# working_ACB_Jr_4.net
KiCad netlist of a schematic drawn in EAGLE
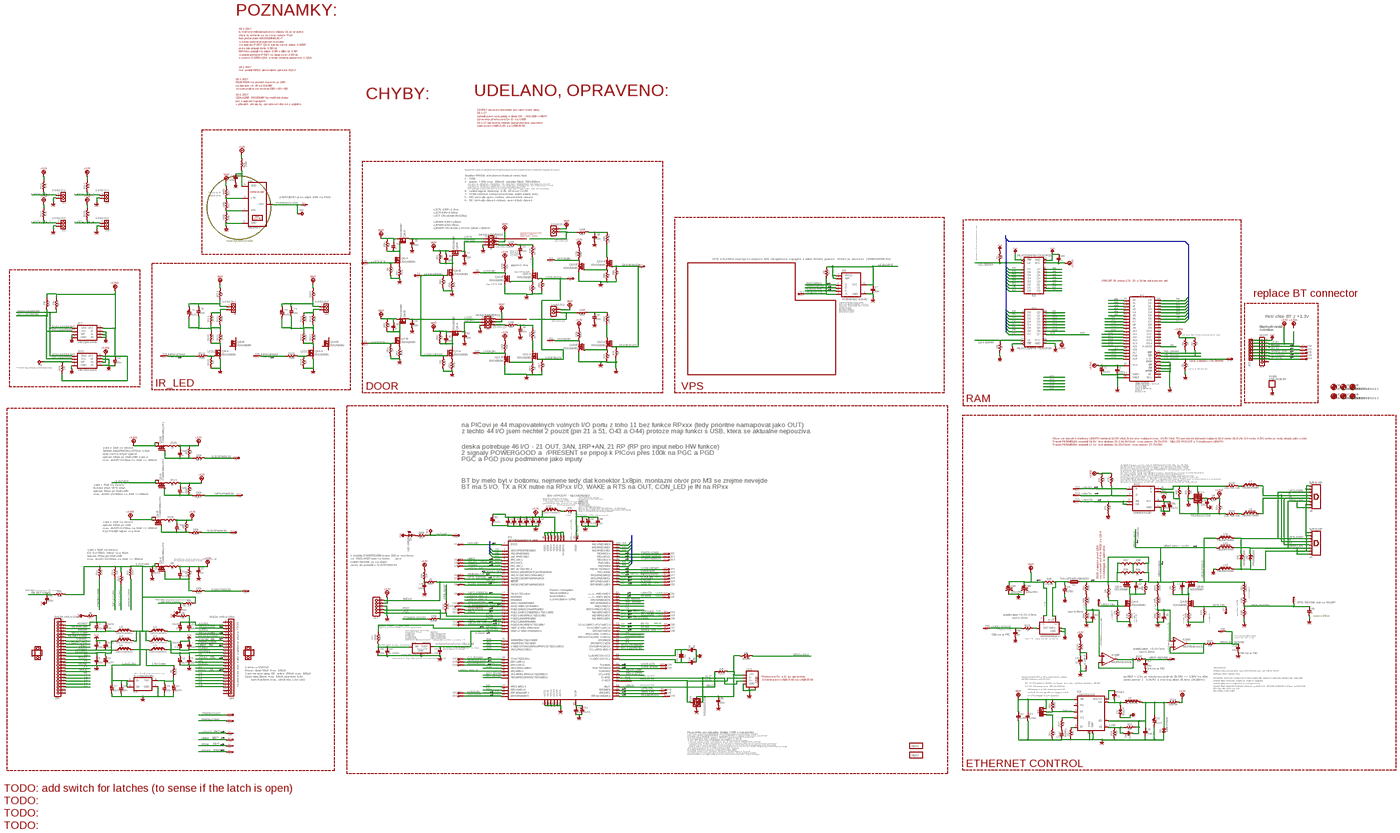
[diagram p0: schematic, sheet 1, overview]
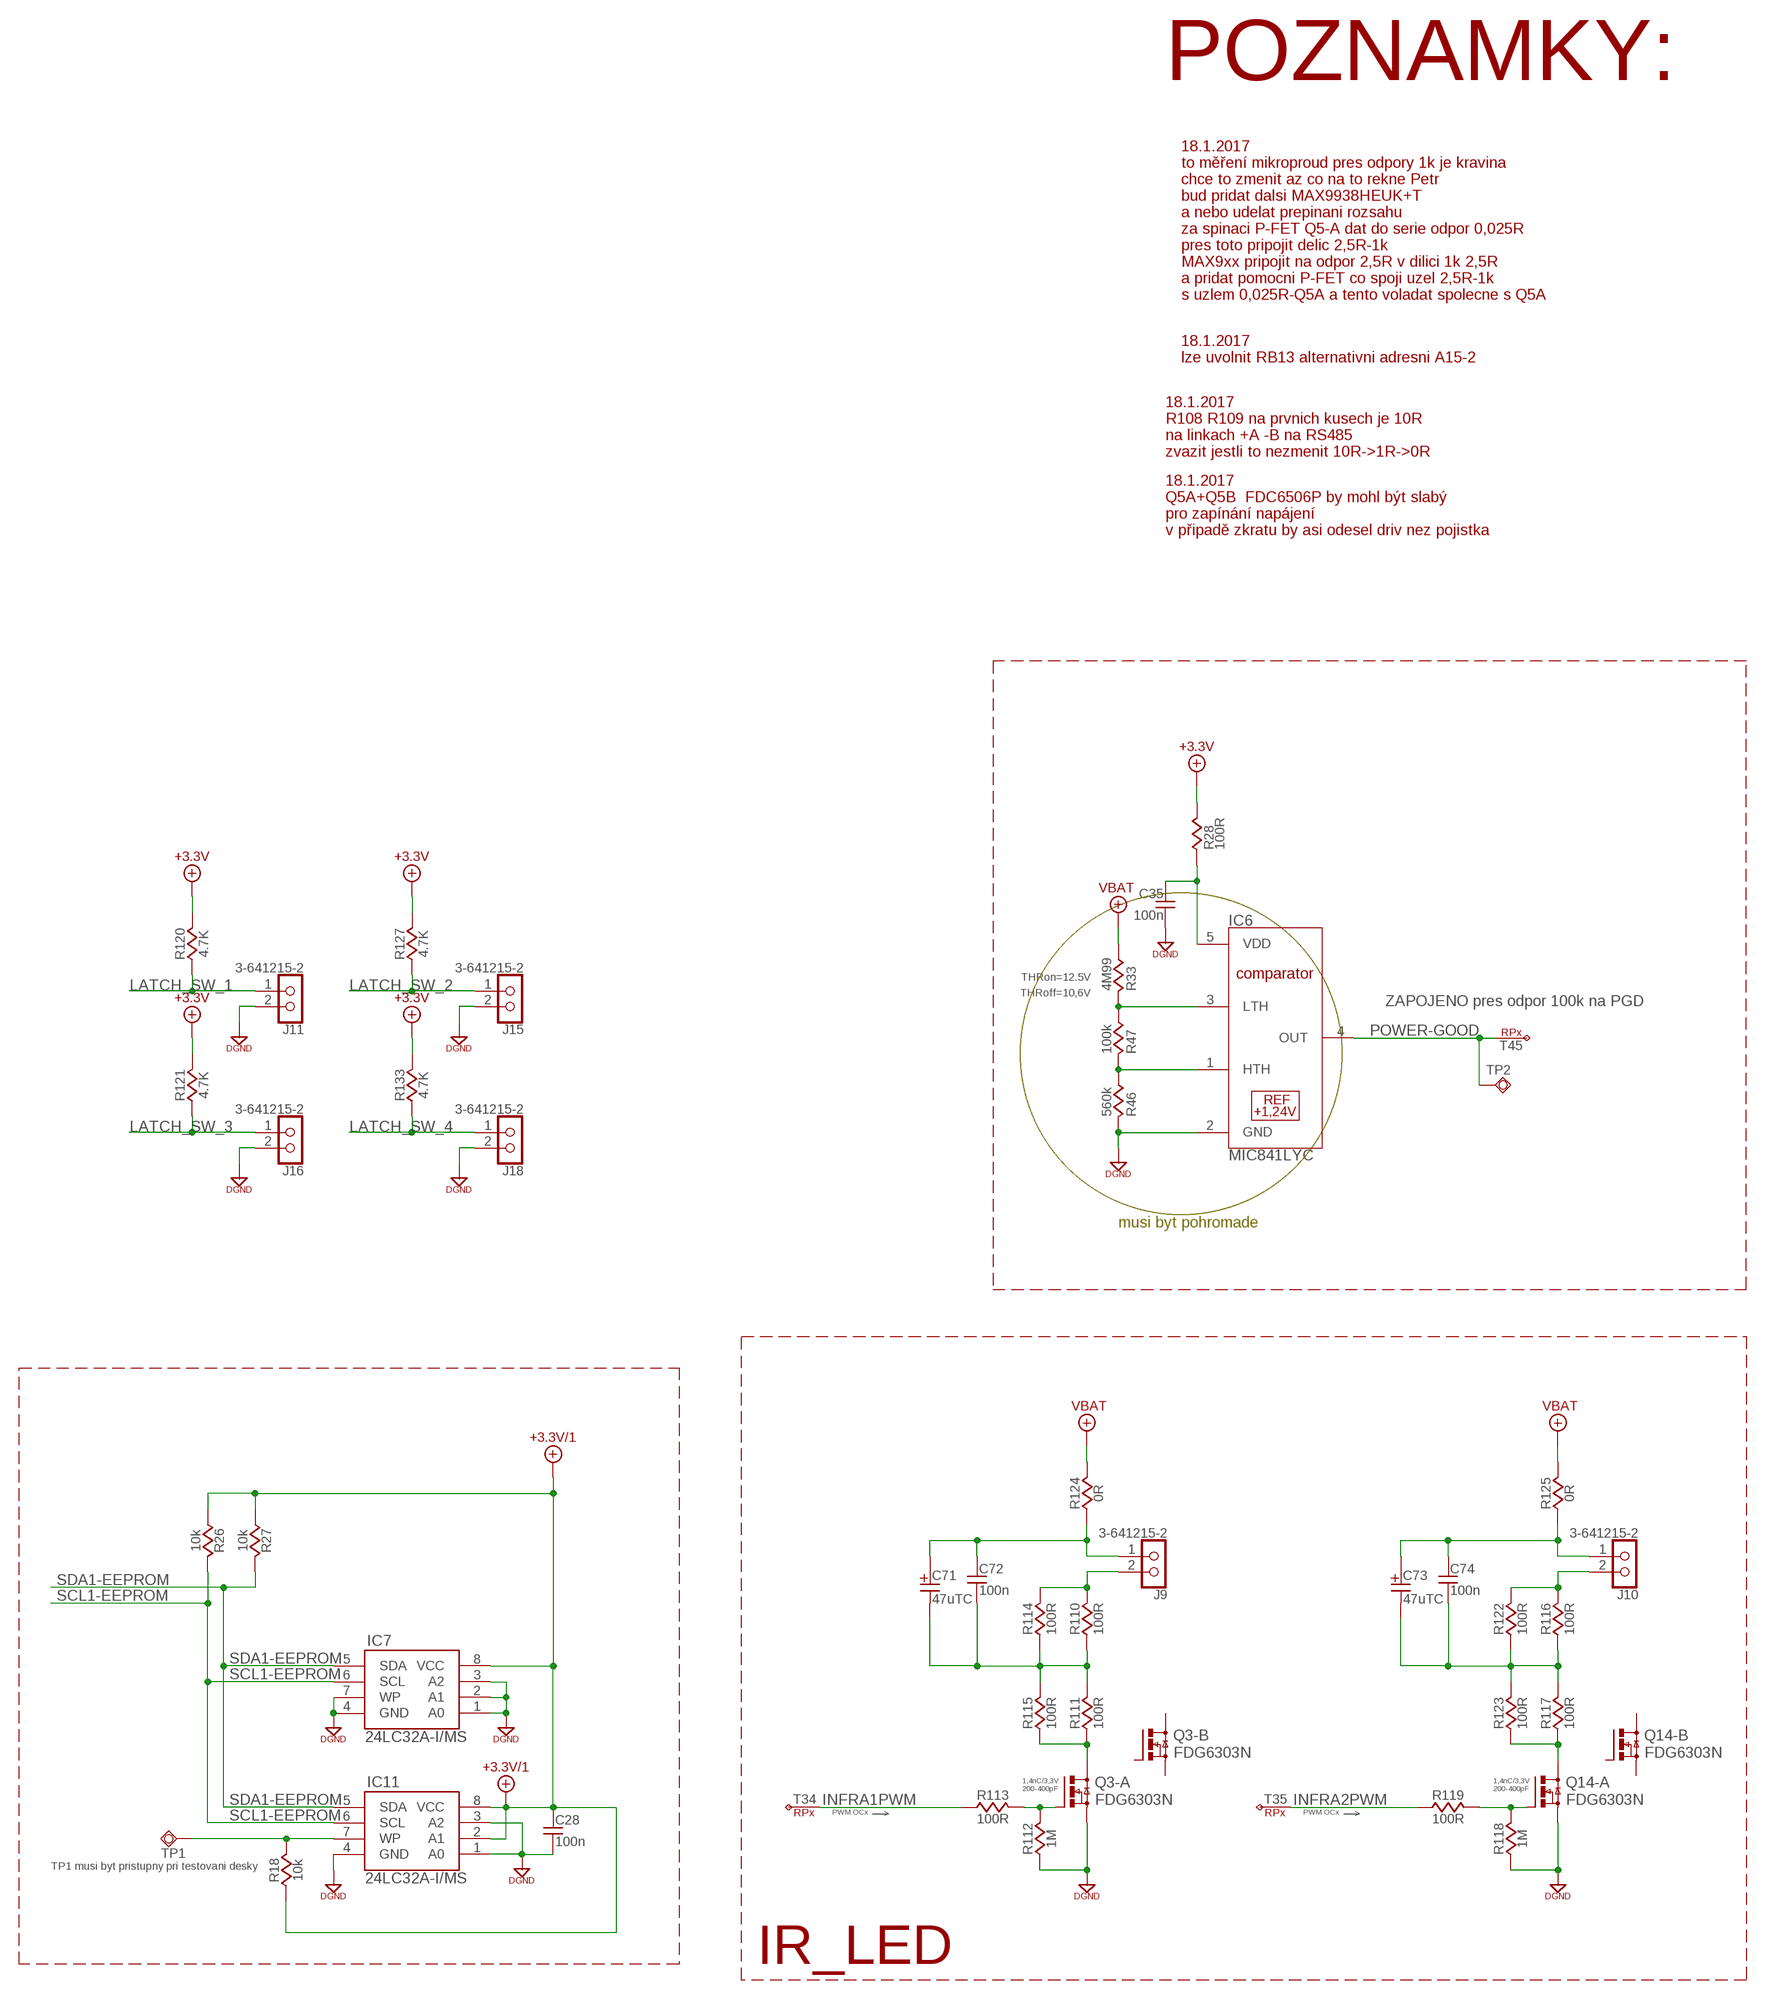
[diagram p1: schematic, sheet 1, part 1 of 5]
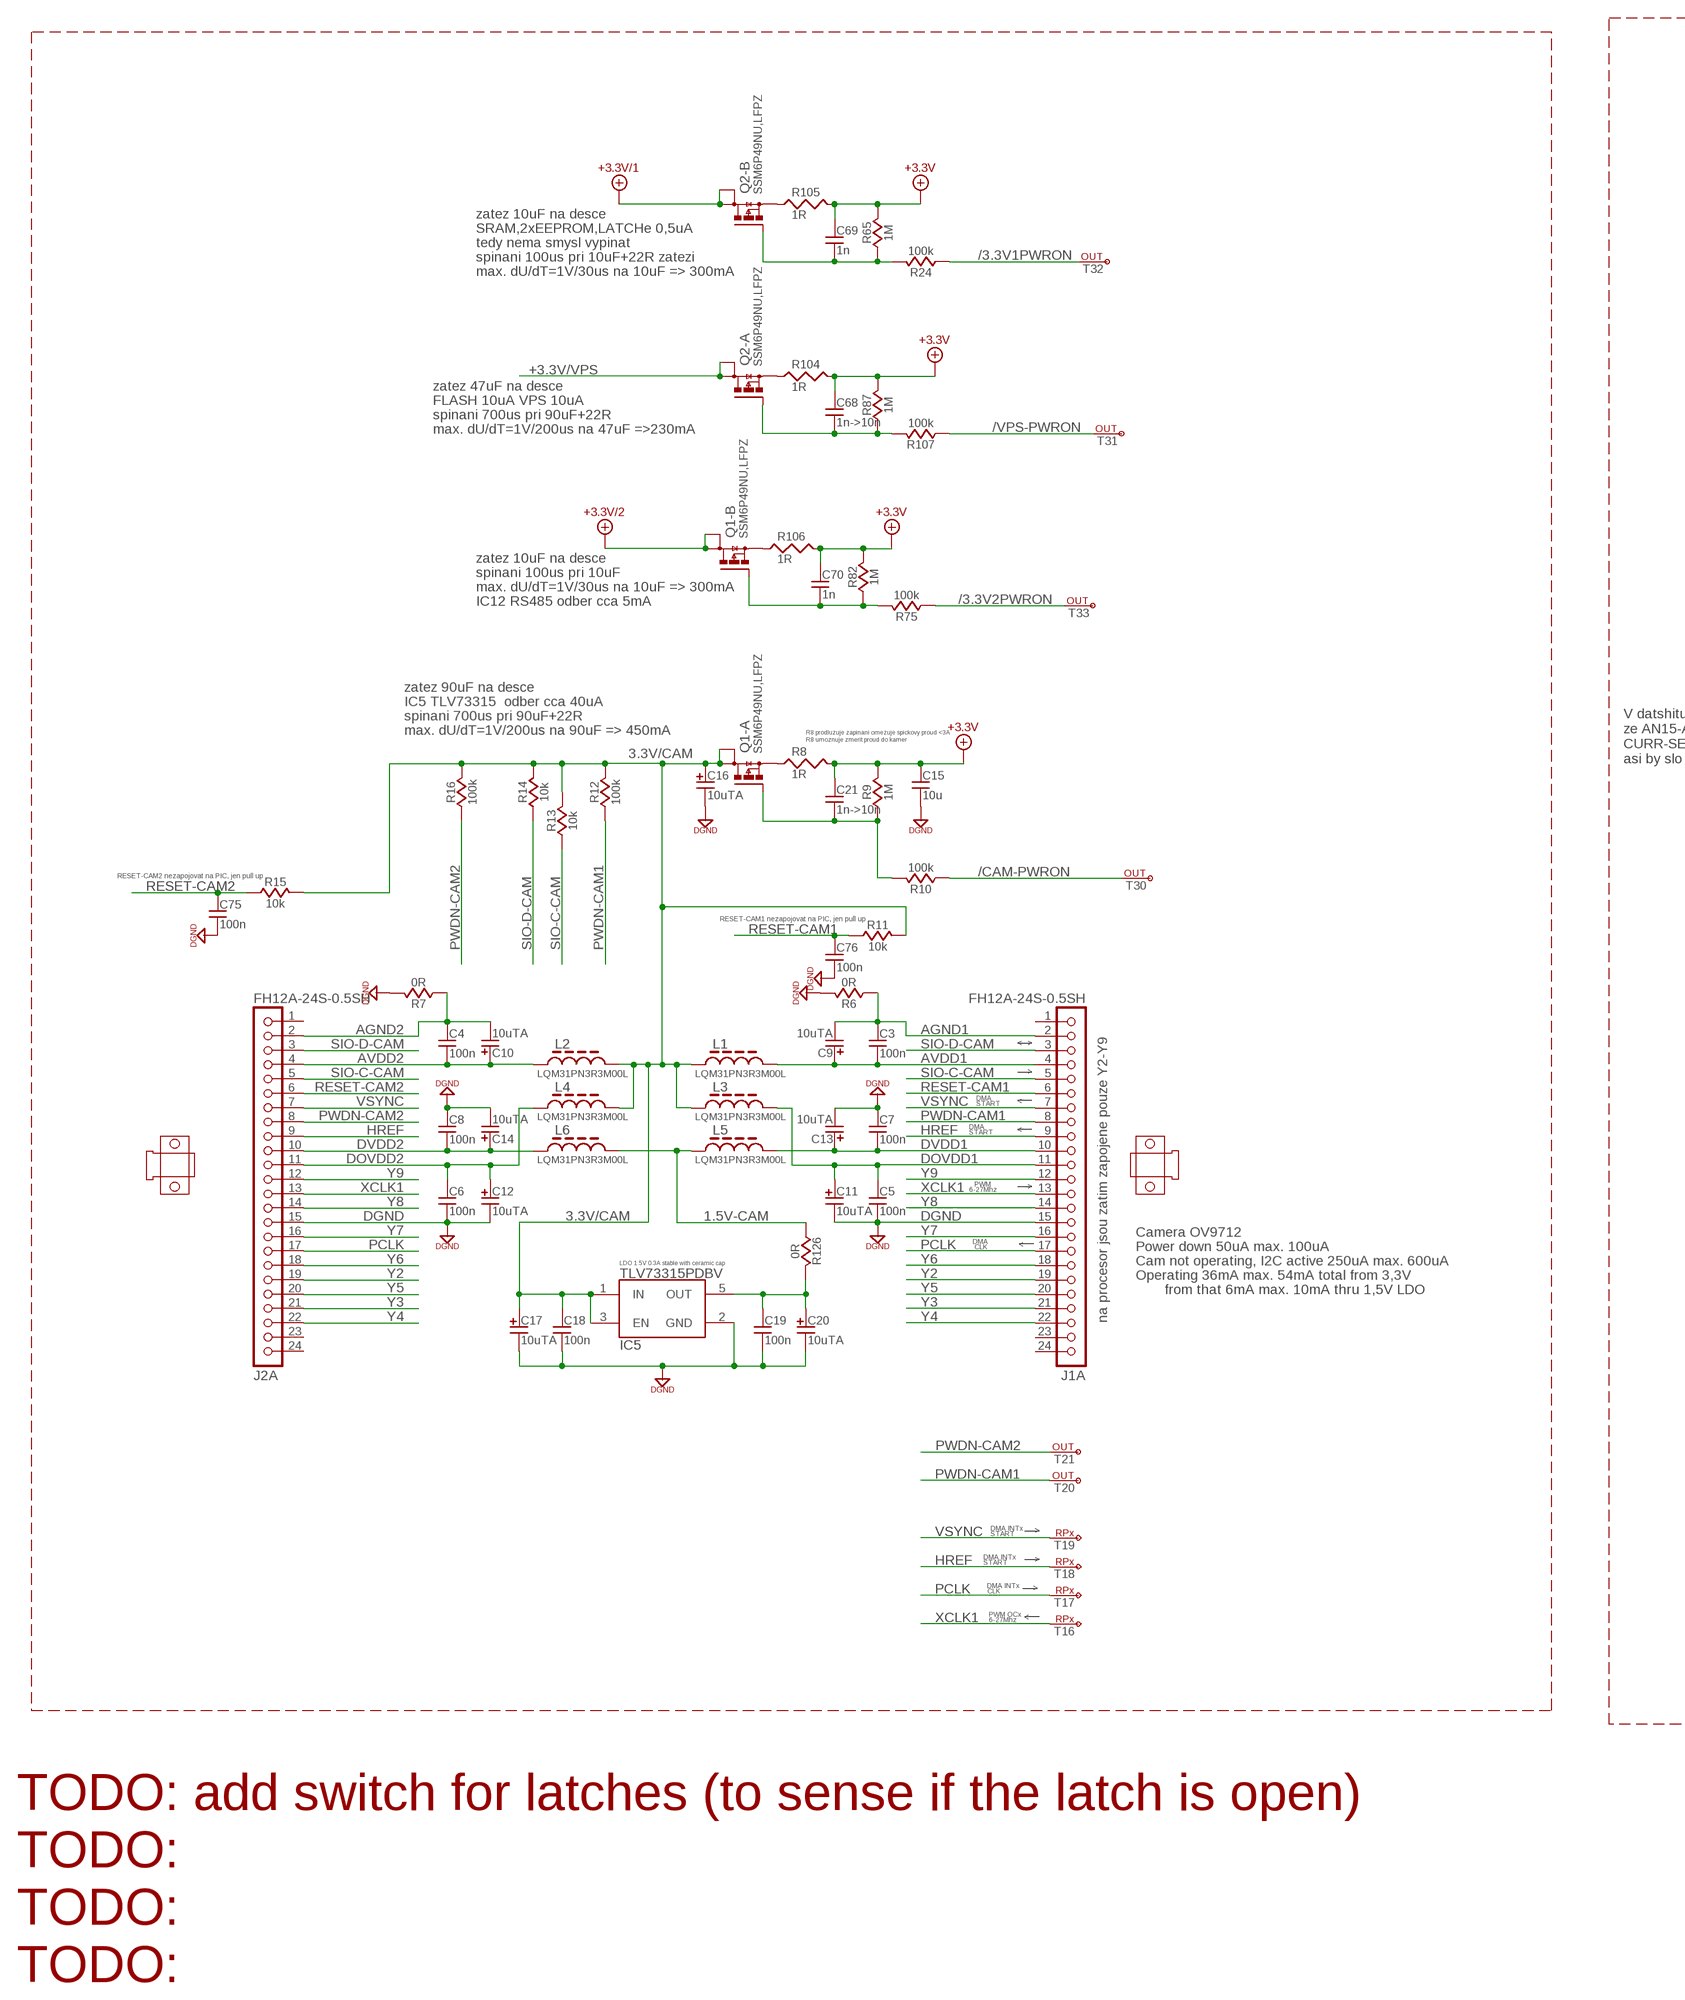
[diagram p2: schematic, sheet 1, part 2 of 5]
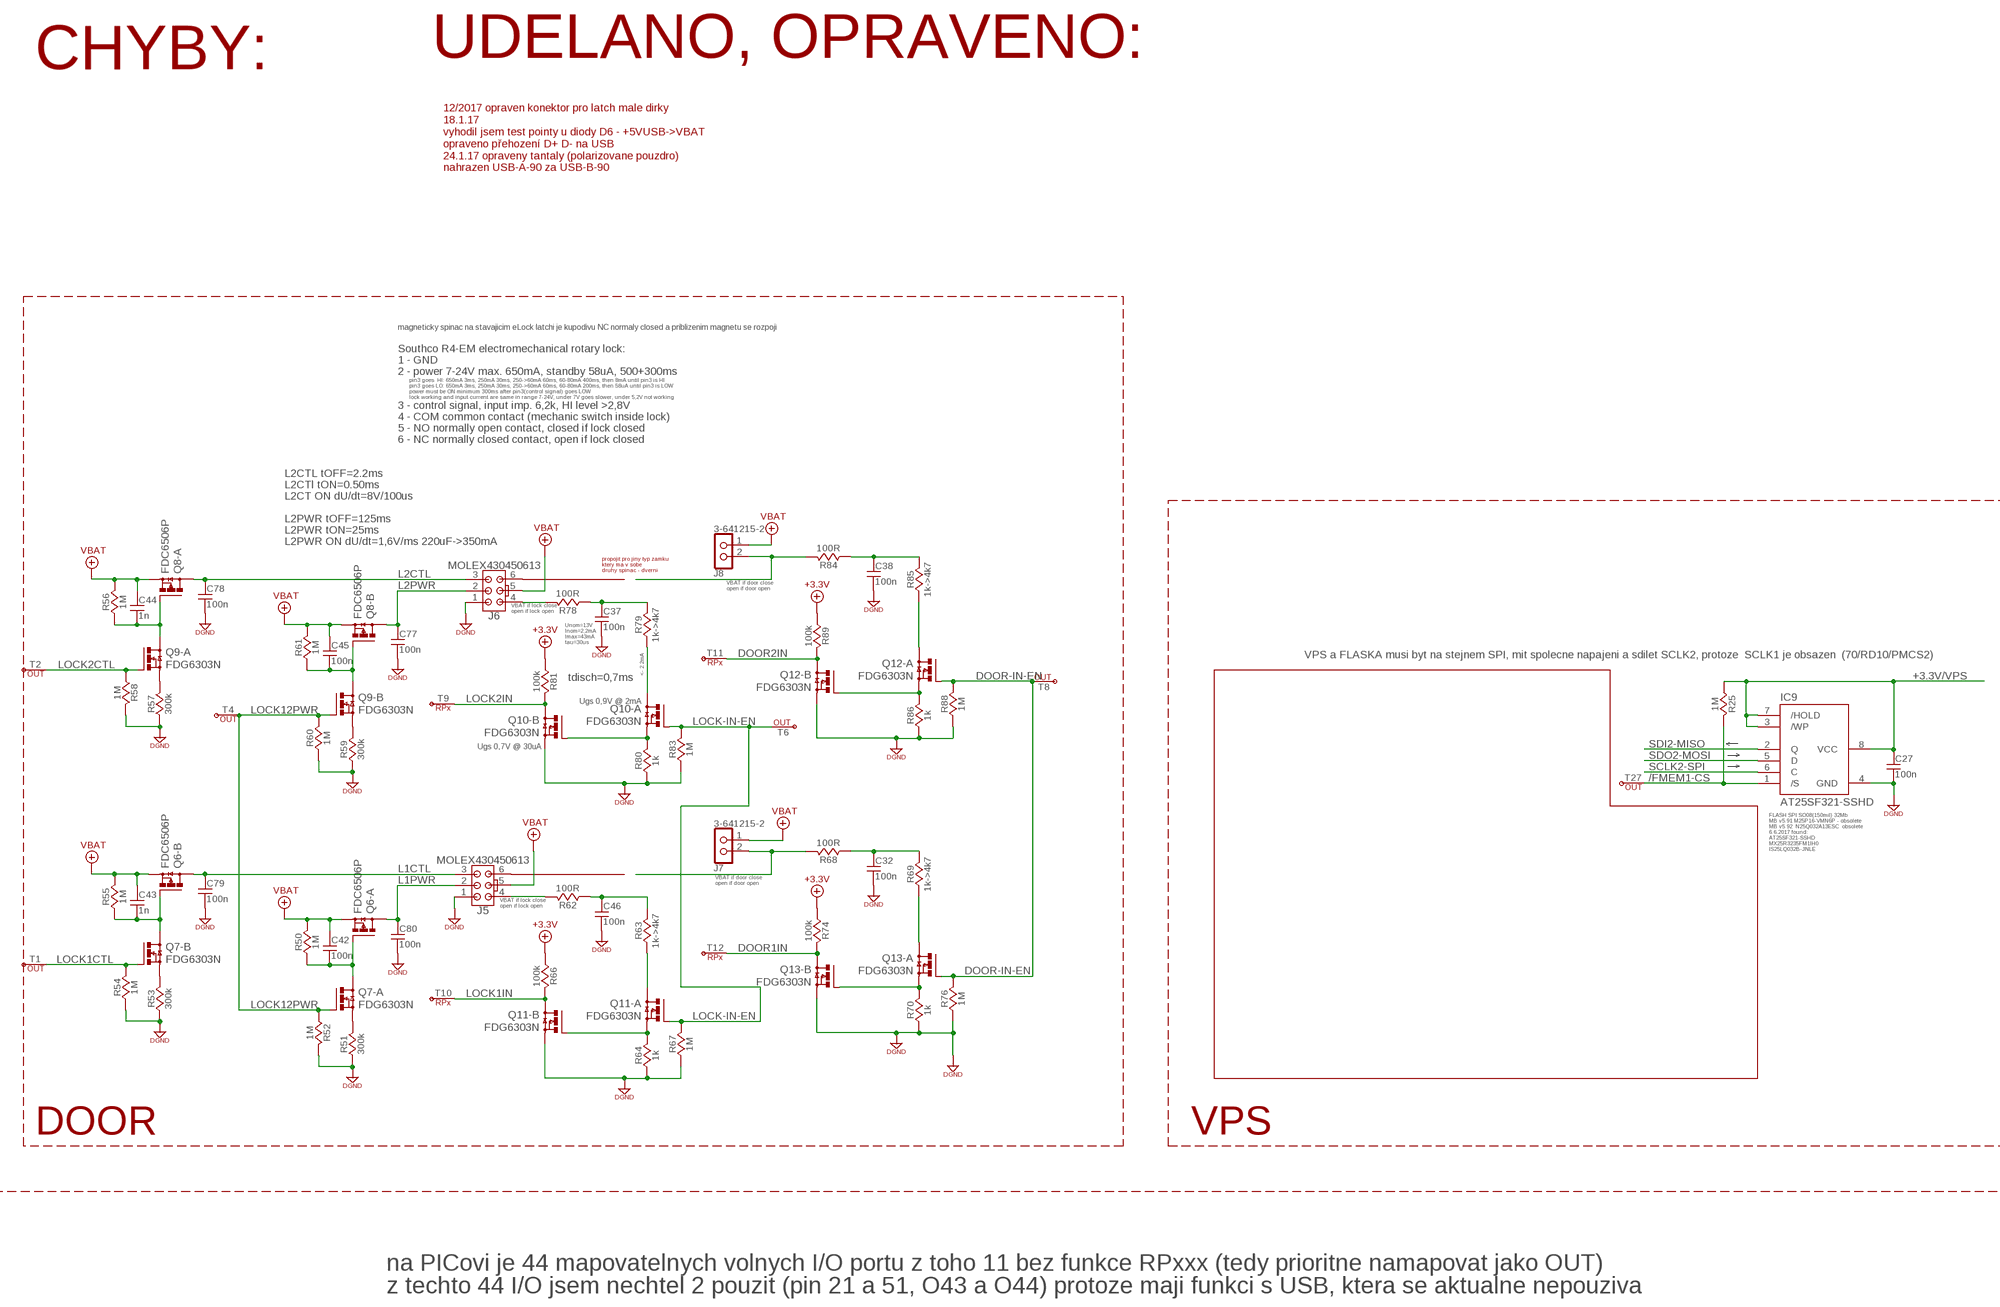
[diagram p3: schematic, sheet 1, part 3 of 5]
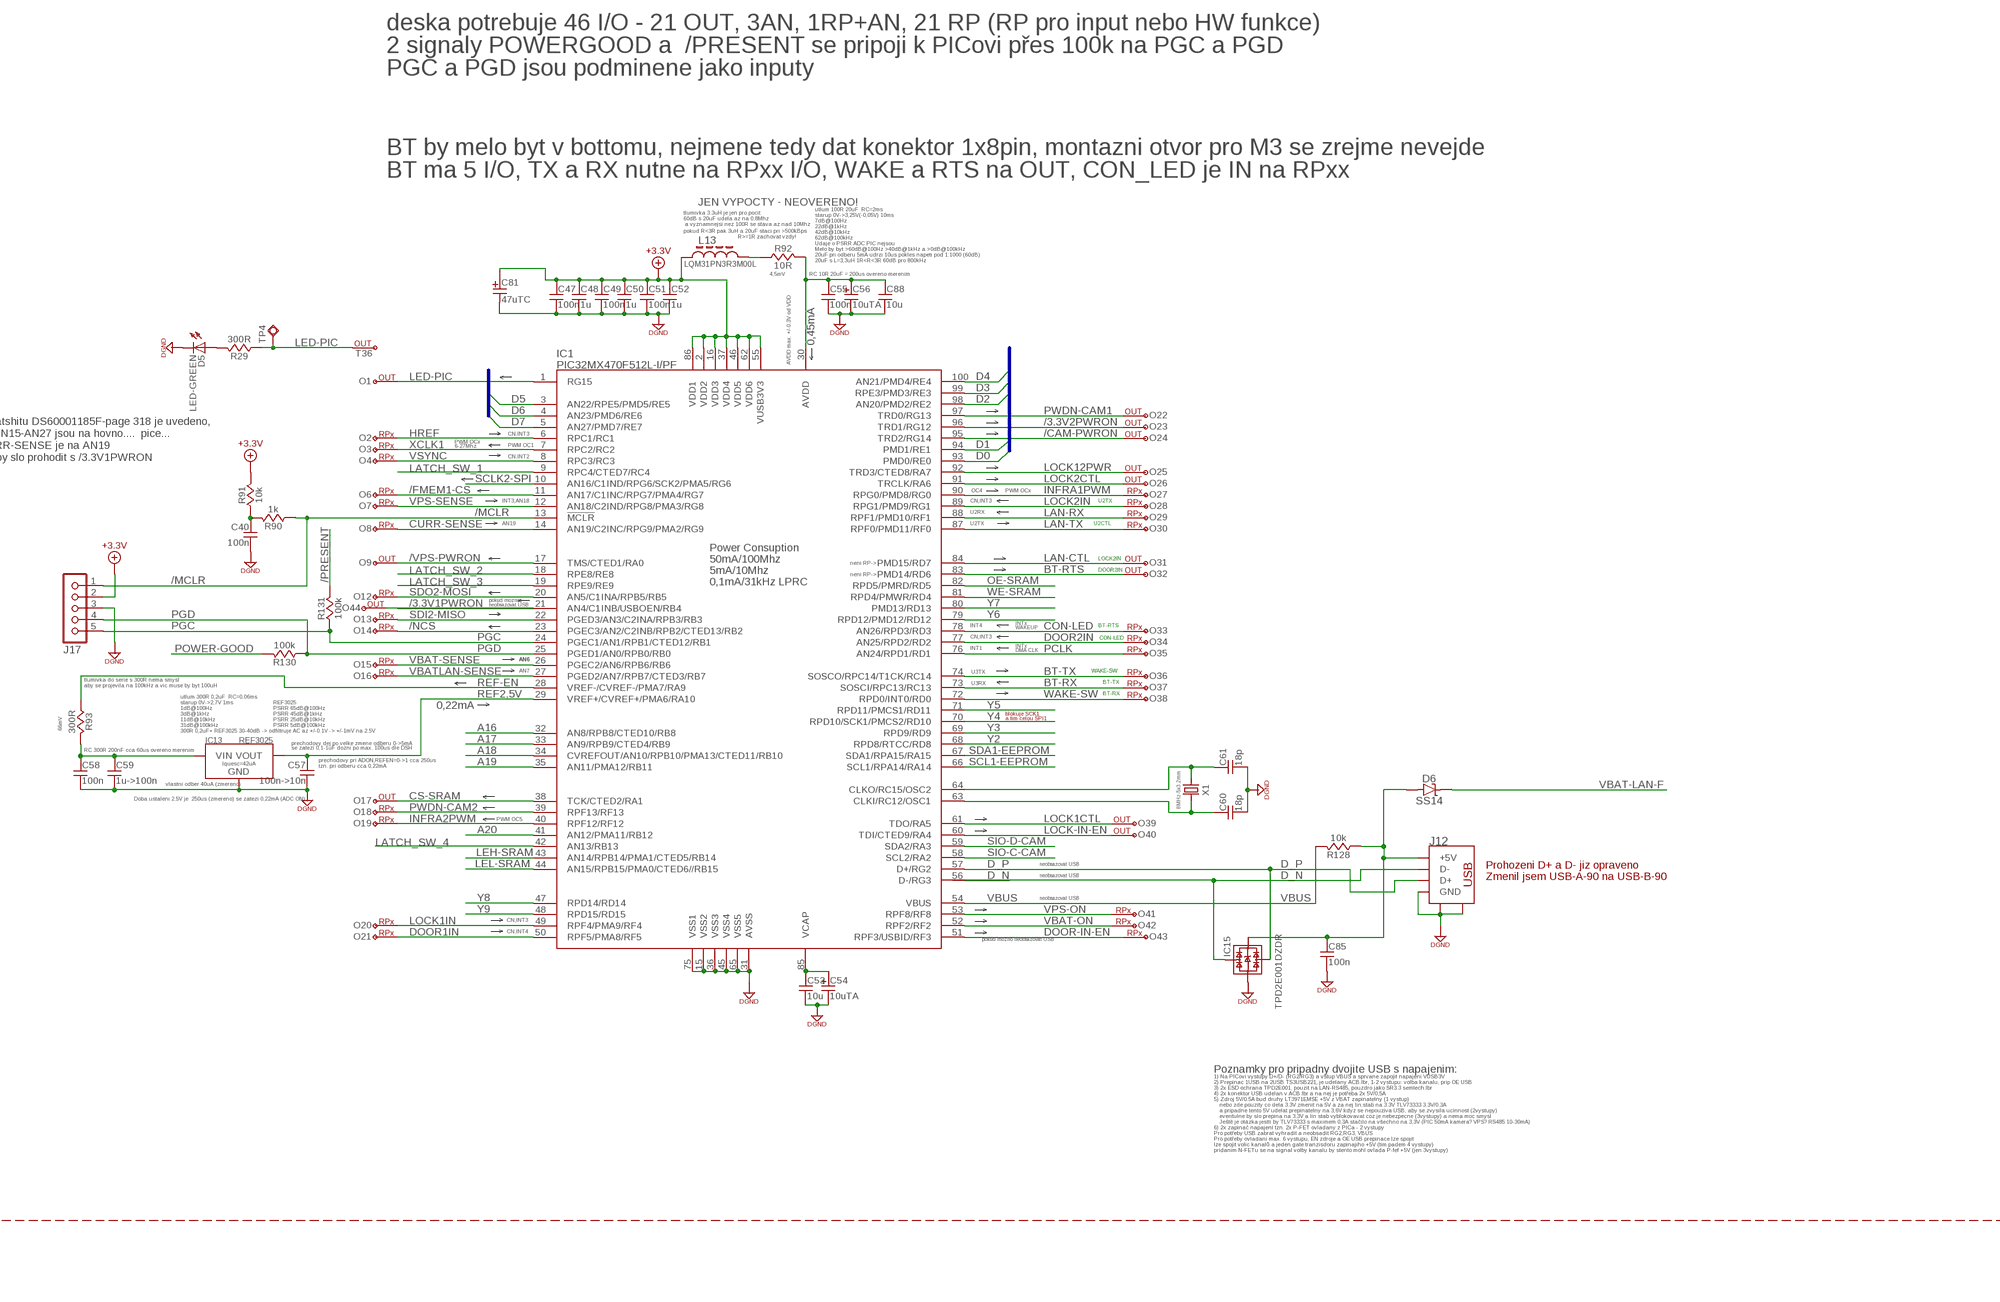
[diagram p4: schematic, sheet 1, part 4 of 5]
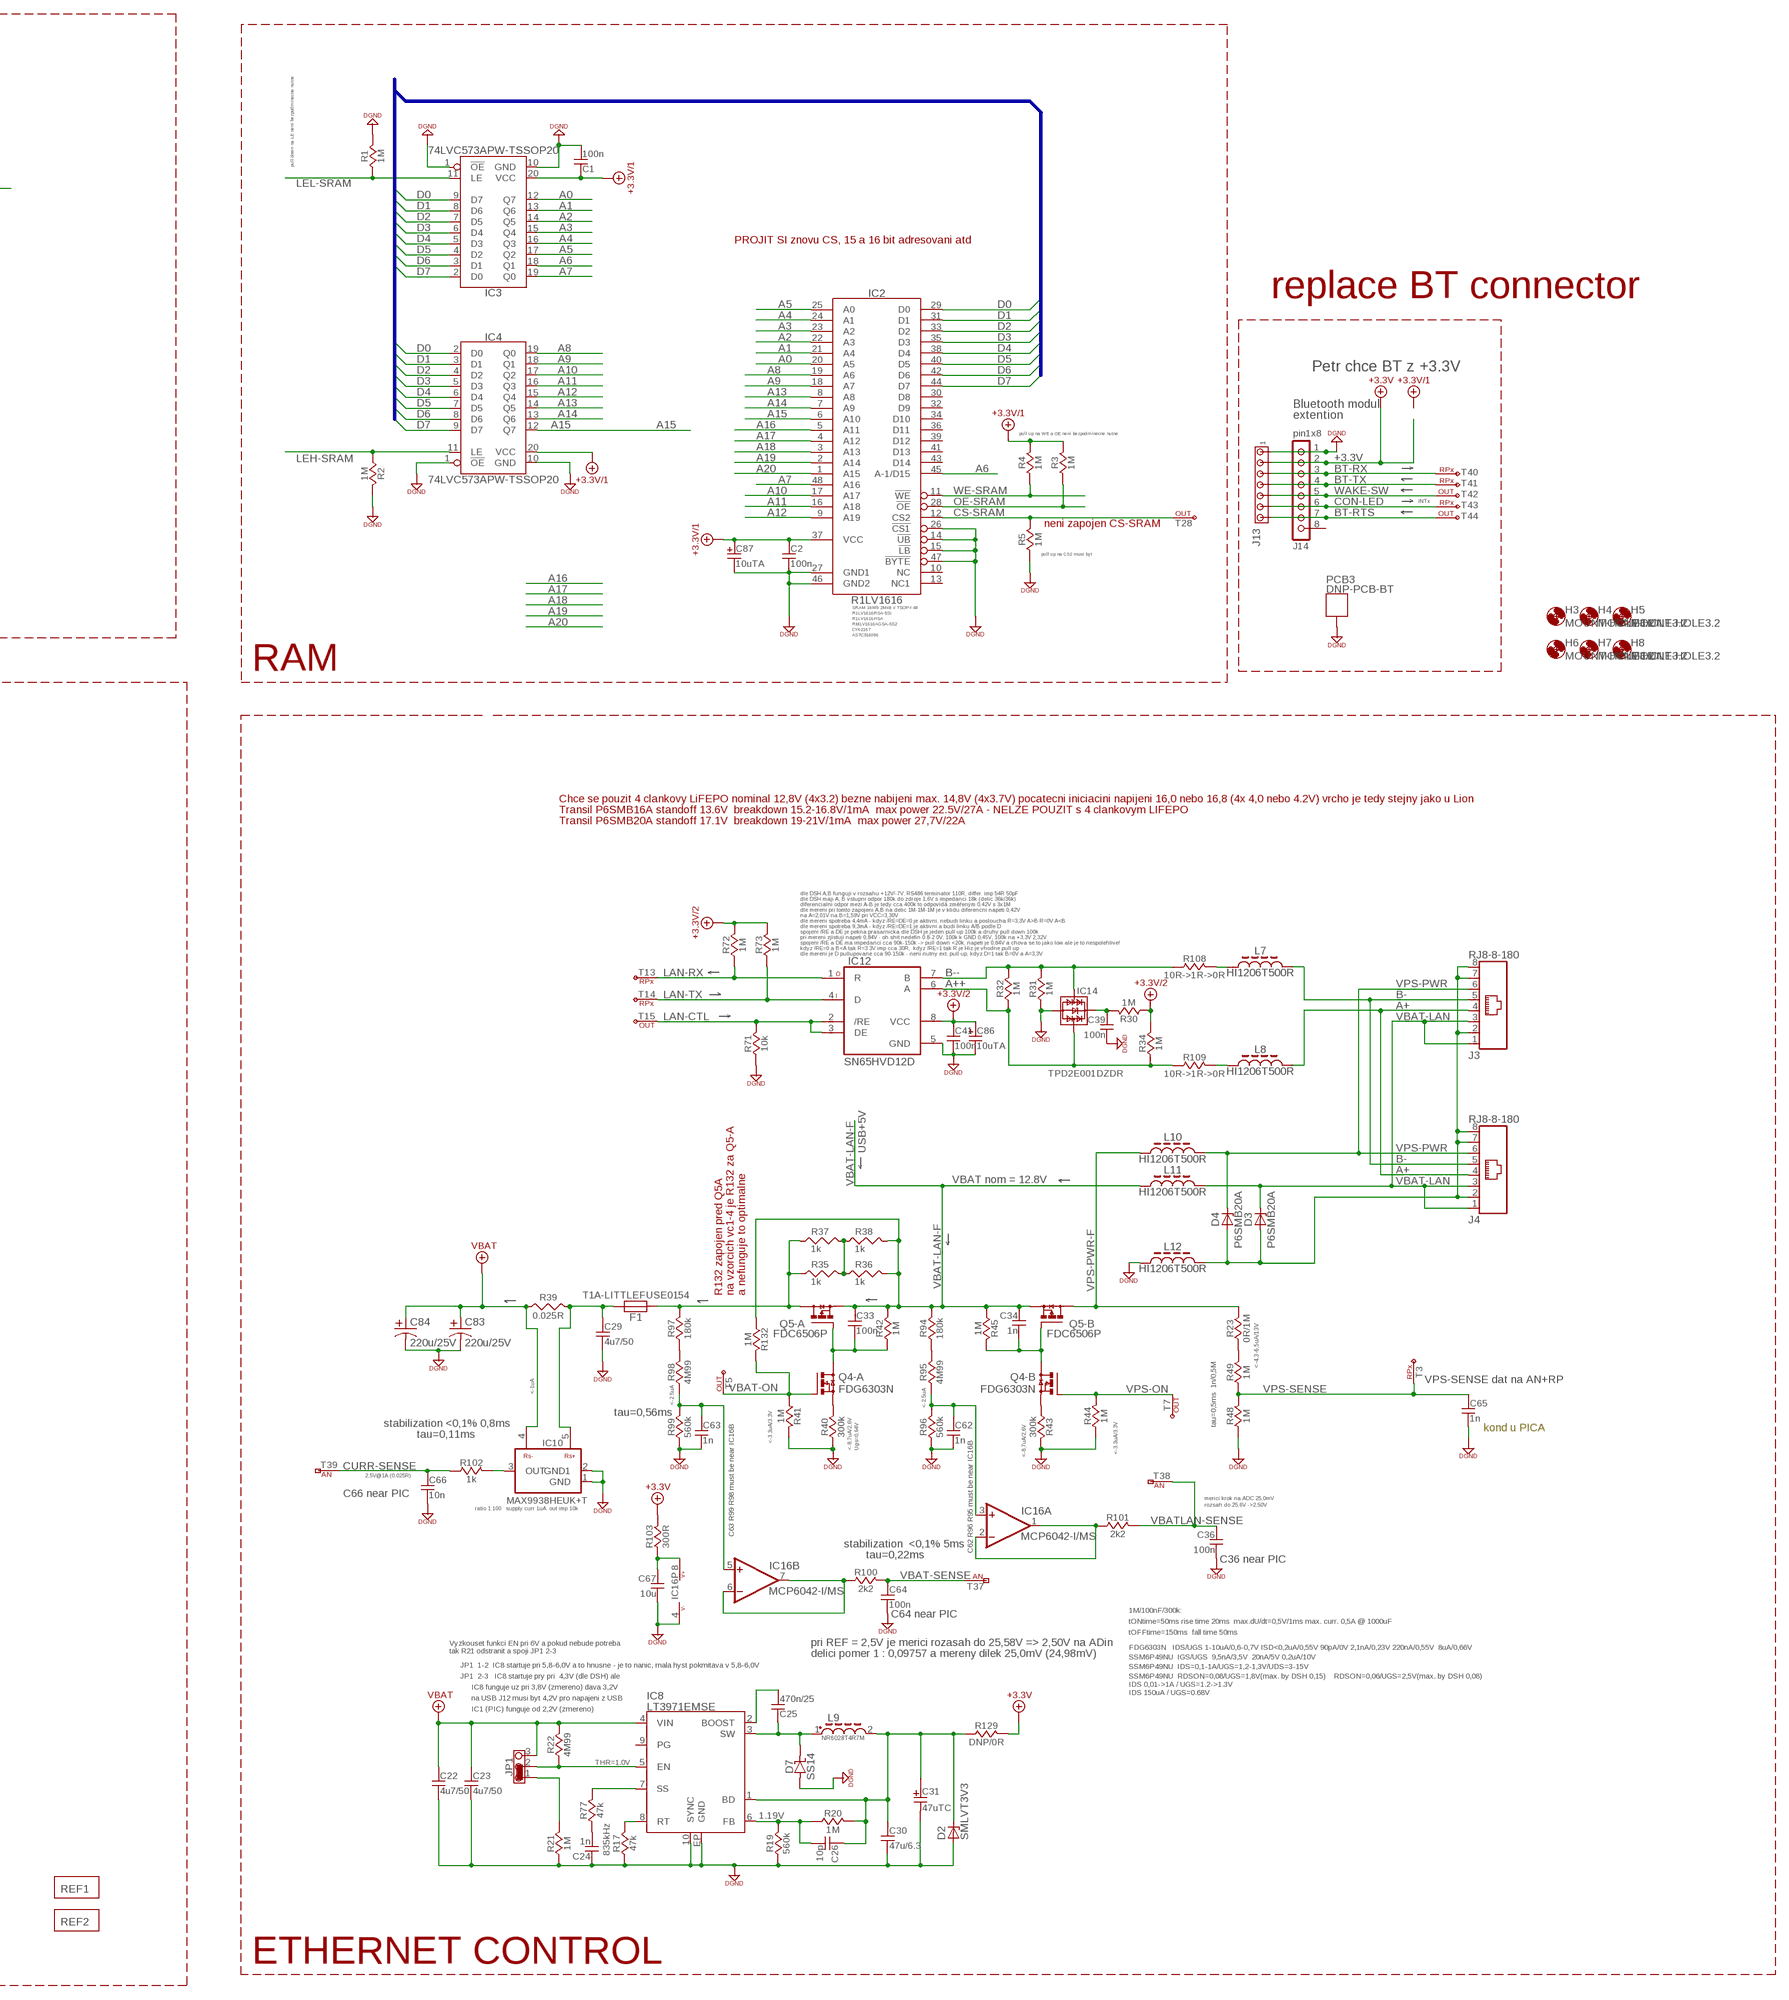
[diagram p5: schematic, sheet 1, part 5 of 5]

(export (version "E")
  (design (tool "Eeschema 10.0.6"))
  (components
    (comp (ref "C1")
      (value "100n")
      (footprint "eagle-import:0603")
      (libsource (lib "eagle-import") (part "C-0603"))
    )
    (comp (ref "C2")
      (value "100n")
      (footprint "eagle-import:0603")
      (libsource (lib "eagle-import") (part "C-0603"))
    )
    (comp (ref "C3")
      (value "100n")
      (footprint "eagle-import:0603")
      (libsource (lib "eagle-import") (part "C-0603"))
    )
    (comp (ref "C4")
      (value "100n")
      (footprint "eagle-import:0603")
      (libsource (lib "eagle-import") (part "C-0603"))
    )
    (comp (ref "C5")
      (value "100n")
      (footprint "eagle-import:0603")
      (libsource (lib "eagle-import") (part "C-0603"))
    )
    (comp (ref "C6")
      (value "100n")
      (footprint "eagle-import:0603")
      (libsource (lib "eagle-import") (part "C-0603"))
    )
    (comp (ref "C7")
      (value "100n")
      (footprint "eagle-import:0603")
      (libsource (lib "eagle-import") (part "C-0603"))
    )
    (comp (ref "C8")
      (value "100n")
      (footprint "eagle-import:0603")
      (libsource (lib "eagle-import") (part "C-0603"))
    )
    (comp (ref "C9")
      (value "10uTA")
      (footprint "eagle-import:1206-POL-C")
      (libsource (lib "eagle-import") (part "CT-1206"))
    )
    (comp (ref "C10")
      (value "10uTA")
      (footprint "eagle-import:1206-POL-C")
      (libsource (lib "eagle-import") (part "CT-1206"))
    )
    (comp (ref "C11")
      (value "10uTA")
      (footprint "eagle-import:1206-POL-C")
      (libsource (lib "eagle-import") (part "CT-1206"))
    )
    (comp (ref "C12")
      (value "10uTA")
      (footprint "eagle-import:1206-POL-C")
      (libsource (lib "eagle-import") (part "CT-1206"))
    )
    (comp (ref "C13")
      (value "10uTA")
      (footprint "eagle-import:1206-POL-C")
      (libsource (lib "eagle-import") (part "CT-1206"))
    )
    (comp (ref "C14")
      (value "10uTA")
      (footprint "eagle-import:1206-POL-C")
      (libsource (lib "eagle-import") (part "CT-1206"))
    )
    (comp (ref "C15")
      (value "10u")
      (footprint "eagle-import:0603")
      (libsource (lib "eagle-import") (part "C-0603"))
    )
    (comp (ref "C16")
      (value "10uTA")
      (footprint "eagle-import:1206-POL-C")
      (libsource (lib "eagle-import") (part "CT-1206"))
    )
    (comp (ref "C17")
      (value "10uTA")
      (footprint "eagle-import:1206-POL-C")
      (libsource (lib "eagle-import") (part "CT-1206"))
    )
    (comp (ref "C18")
      (value "100n")
      (footprint "eagle-import:0603")
      (libsource (lib "eagle-import") (part "C-0603"))
    )
    (comp (ref "C19")
      (value "100n")
      (footprint "eagle-import:0603")
      (libsource (lib "eagle-import") (part "C-0603"))
    )
    (comp (ref "C20")
      (value "10uTA")
      (footprint "eagle-import:1206-POL-C")
      (libsource (lib "eagle-import") (part "CT-1206"))
    )
    (comp (ref "C21")
      (value "1n->10n")
      (footprint "eagle-import:0603")
      (libsource (lib "eagle-import") (part "C-0603"))
    )
    (comp (ref "C22")
      (value "4u7/50")
      (footprint "eagle-import:1206")
      (libsource (lib "eagle-import") (part "C-1206"))
    )
    (comp (ref "C23")
      (value "4u7/50")
      (footprint "eagle-import:1206")
      (libsource (lib "eagle-import") (part "C-1206"))
    )
    (comp (ref "C24")
      (value "1n")
      (footprint "eagle-import:0603")
      (libsource (lib "eagle-import") (part "C-0603"))
    )
    (comp (ref "C25")
      (value "470n/25")
      (footprint "eagle-import:0603")
      (libsource (lib "eagle-import") (part "C-0603"))
    )
    (comp (ref "C26")
      (value "10p")
      (footprint "eagle-import:0603")
      (libsource (lib "eagle-import") (part "C-0603"))
    )
    (comp (ref "C27")
      (value "100n")
      (footprint "eagle-import:0603")
      (libsource (lib "eagle-import") (part "C-0603"))
    )
    (comp (ref "C28")
      (value "100n")
      (footprint "eagle-import:0603")
      (libsource (lib "eagle-import") (part "C-0603"))
    )
    (comp (ref "C29")
      (value "4u7/50")
      (footprint "eagle-import:1206")
      (libsource (lib "eagle-import") (part "C-1206"))
    )
    (comp (ref "C30")
      (value "47u/6.3")
      (footprint "eagle-import:1206")
      (libsource (lib "eagle-import") (part "C-1206"))
    )
    (comp (ref "C31")
      (value "47uTC")
      (footprint "eagle-import:CT-C")
      (libsource (lib "eagle-import") (part "CT-C"))
    )
    (comp (ref "C32")
      (value "100n")
      (footprint "eagle-import:0603")
      (libsource (lib "eagle-import") (part "C-0603"))
    )
    (comp (ref "C33")
      (value "100n")
      (footprint "eagle-import:0603")
      (libsource (lib "eagle-import") (part "C-0603"))
    )
    (comp (ref "C34")
      (value "1n")
      (footprint "eagle-import:0603")
      (libsource (lib "eagle-import") (part "C-0603"))
    )
    (comp (ref "C35")
      (value "100n")
      (footprint "eagle-import:0603")
      (libsource (lib "eagle-import") (part "C-0603"))
    )
    (comp (ref "C36")
      (value "100n")
      (footprint "eagle-import:0603")
      (libsource (lib "eagle-import") (part "C-0603"))
    )
    (comp (ref "C37")
      (value "100n")
      (footprint "eagle-import:0603")
      (libsource (lib "eagle-import") (part "C-0603"))
    )
    (comp (ref "C38")
      (value "100n")
      (footprint "eagle-import:0603")
      (libsource (lib "eagle-import") (part "C-0603"))
    )
    (comp (ref "C39")
      (value "100n")
      (footprint "eagle-import:0603")
      (libsource (lib "eagle-import") (part "C-0603"))
    )
    (comp (ref "C40")
      (value "100n")
      (footprint "eagle-import:0603")
      (libsource (lib "eagle-import") (part "C-0603"))
    )
    (comp (ref "C41")
      (value "100n")
      (footprint "eagle-import:0603")
      (libsource (lib "eagle-import") (part "C-0603"))
    )
    (comp (ref "C42")
      (value "100n")
      (footprint "eagle-import:0603")
      (libsource (lib "eagle-import") (part "C-0603"))
    )
    (comp (ref "C43")
      (value "1n")
      (footprint "eagle-import:0603")
      (libsource (lib "eagle-import") (part "C-0603"))
    )
    (comp (ref "C44")
      (value "1n")
      (footprint "eagle-import:0603")
      (libsource (lib "eagle-import") (part "C-0603"))
    )
    (comp (ref "C45")
      (value "100n")
      (footprint "eagle-import:0603")
      (libsource (lib "eagle-import") (part "C-0603"))
    )
    (comp (ref "C46")
      (value "100n")
      (footprint "eagle-import:0603")
      (libsource (lib "eagle-import") (part "C-0603"))
    )
    (comp (ref "C47")
      (value "100n")
      (footprint "eagle-import:0603")
      (libsource (lib "eagle-import") (part "C-0603"))
    )
    (comp (ref "C48")
      (value "1u")
      (footprint "eagle-import:0603")
      (libsource (lib "eagle-import") (part "C-0603"))
    )
    (comp (ref "C49")
      (value "100n")
      (footprint "eagle-import:0603")
      (libsource (lib "eagle-import") (part "C-0603"))
    )
    (comp (ref "C50")
      (value "1u")
      (footprint "eagle-import:0603")
      (libsource (lib "eagle-import") (part "C-0603"))
    )
    (comp (ref "C51")
      (value "100n")
      (footprint "eagle-import:0603")
      (libsource (lib "eagle-import") (part "C-0603"))
    )
    (comp (ref "C52")
      (value "1u")
      (footprint "eagle-import:0603")
      (libsource (lib "eagle-import") (part "C-0603"))
    )
    (comp (ref "C53")
      (value "10u")
      (footprint "eagle-import:0603")
      (libsource (lib "eagle-import") (part "C-0603"))
    )
    (comp (ref "C54")
      (value "10uTA")
      (footprint "eagle-import:1206-POL-C")
      (libsource (lib "eagle-import") (part "CT-1206"))
    )
    (comp (ref "C55")
      (value "100n")
      (footprint "eagle-import:0603")
      (libsource (lib "eagle-import") (part "C-0603"))
    )
    (comp (ref "C56")
      (value "10uTA")
      (footprint "eagle-import:1206-POL-C")
      (libsource (lib "eagle-import") (part "CT-1206"))
    )
    (comp (ref "C57")
      (value "100n->10n")
      (footprint "eagle-import:0603")
      (libsource (lib "eagle-import") (part "C-0603"))
    )
    (comp (ref "C58")
      (value "100n")
      (footprint "eagle-import:0603")
      (libsource (lib "eagle-import") (part "C-0603"))
    )
    (comp (ref "C59")
      (value "1u->100n")
      (footprint "eagle-import:0603")
      (libsource (lib "eagle-import") (part "C-0603"))
    )
    (comp (ref "C60")
      (value "18p")
      (footprint "eagle-import:0603")
      (libsource (lib "eagle-import") (part "C-0603"))
    )
    (comp (ref "C61")
      (value "18p")
      (footprint "eagle-import:0603")
      (libsource (lib "eagle-import") (part "C-0603"))
    )
    (comp (ref "C62")
      (value "1n")
      (footprint "eagle-import:0603")
      (libsource (lib "eagle-import") (part "C-0603"))
    )
    (comp (ref "C63")
      (value "1n")
      (footprint "eagle-import:0603")
      (libsource (lib "eagle-import") (part "C-0603"))
    )
    (comp (ref "C64")
      (value "100n")
      (footprint "eagle-import:0603")
      (libsource (lib "eagle-import") (part "C-0603"))
    )
    (comp (ref "C65")
      (value "1n")
      (footprint "eagle-import:0603")
      (libsource (lib "eagle-import") (part "C-0603"))
    )
    (comp (ref "C66")
      (value "10n")
      (footprint "eagle-import:0603")
      (libsource (lib "eagle-import") (part "C-0603"))
    )
    (comp (ref "C67")
      (value "10u")
      (footprint "eagle-import:0603")
      (libsource (lib "eagle-import") (part "C-0603"))
    )
    (comp (ref "C68")
      (value "1n->10n")
      (footprint "eagle-import:0603")
      (libsource (lib "eagle-import") (part "C-0603"))
    )
    (comp (ref "C69")
      (value "1n")
      (footprint "eagle-import:0603")
      (libsource (lib "eagle-import") (part "C-0603"))
    )
    (comp (ref "C70")
      (value "1n")
      (footprint "eagle-import:0603")
      (libsource (lib "eagle-import") (part "C-0603"))
    )
    (comp (ref "C71")
      (value "47uTC")
      (footprint "eagle-import:CT-C")
      (libsource (lib "eagle-import") (part "CT-C"))
    )
    (comp (ref "C72")
      (value "100n")
      (footprint "eagle-import:0603")
      (libsource (lib "eagle-import") (part "C-0603"))
    )
    (comp (ref "C73")
      (value "47uTC")
      (footprint "eagle-import:CT-C")
      (libsource (lib "eagle-import") (part "CT-C"))
    )
    (comp (ref "C74")
      (value "100n")
      (footprint "eagle-import:0603")
      (libsource (lib "eagle-import") (part "C-0603"))
    )
    (comp (ref "C75")
      (value "100n")
      (footprint "eagle-import:0603")
      (libsource (lib "eagle-import") (part "C-0603"))
    )
    (comp (ref "C76")
      (value "100n")
      (footprint "eagle-import:0603")
      (libsource (lib "eagle-import") (part "C-0603"))
    )
    (comp (ref "C77")
      (value "100n")
      (footprint "eagle-import:0603")
      (libsource (lib "eagle-import") (part "C-0603"))
    )
    (comp (ref "C78")
      (value "100n")
      (footprint "eagle-import:0603")
      (libsource (lib "eagle-import") (part "C-0603"))
    )
    (comp (ref "C79")
      (value "100n")
      (footprint "eagle-import:0603")
      (libsource (lib "eagle-import") (part "C-0603"))
    )
    (comp (ref "C80")
      (value "100n")
      (footprint "eagle-import:0603")
      (libsource (lib "eagle-import") (part "C-0603"))
    )
    (comp (ref "C81")
      (value "47uTC")
      (footprint "eagle-import:CT-C")
      (libsource (lib "eagle-import") (part "CT-C"))
    )
    (comp (ref "C83")
      (value "220u/25V")
      (footprint "eagle-import:CAP_8MM_DIA_SMT")
      (libsource (lib "eagle-import") (part "CAP-ELEC-SMD-8MM"))
    )
    (comp (ref "C84")
      (value "220u/25V")
      (footprint "eagle-import:CAP_8MM_DIA_SMT")
      (libsource (lib "eagle-import") (part "CAP-ELEC-SMD-8MM"))
    )
    (comp (ref "C85")
      (value "100n")
      (footprint "eagle-import:0603")
      (libsource (lib "eagle-import") (part "C-0603"))
    )
    (comp (ref "C86")
      (value "10uTA")
      (footprint "eagle-import:1206-POL-C")
      (libsource (lib "eagle-import") (part "CT-1206"))
    )
    (comp (ref "C87")
      (value "10uTA")
      (footprint "eagle-import:1206-POL-C")
      (libsource (lib "eagle-import") (part "CT-1206"))
    )
    (comp (ref "C88")
      (value "10u")
      (footprint "eagle-import:0603")
      (libsource (lib "eagle-import") (part "C-0603"))
    )
    (comp (ref "D2")
      (value "SMLVT3V3")
      (footprint "eagle-import:SMA")
      (libsource (lib "eagle-import") (part "SMLVT3V3"))
    )
    (comp (ref "D3")
      (value "P6SMB20A")
      (footprint "eagle-import:SMB@1")
      (libsource (lib "eagle-import") (part "P6SMB"))
    )
    (comp (ref "D4")
      (value "P6SMB20A")
      (footprint "eagle-import:SMB@1")
      (libsource (lib "eagle-import") (part "P6SMB"))
    )
    (comp (ref "D5")
      (value "LED-GREEN")
      (footprint "eagle-import:0805-POL-D")
      (libsource (lib "eagle-import") (part "LED-0805"))
    )
    (comp (ref "D6")
      (value "SS14")
      (footprint "eagle-import:SMA")
      (libsource (lib "eagle-import") (part "DS-SMA"))
    )
    (comp (ref "D7")
      (value "SS14")
      (footprint "eagle-import:SMA")
      (libsource (lib "eagle-import") (part "DS-SMA"))
    )
    (comp (ref "F1")
      (value "T1A-LITTLEFUSE0154")
      (footprint "eagle-import:LITTLEFUSE0154")
      (libsource (lib "eagle-import") (part "POJISTKA-LITTLEFUSE0154"))
    )
    (comp (ref "H1")
      (value "CAM-HOLDER")
      (footprint "eagle-import:CAM-HOLDER")
      (libsource (lib "eagle-import") (part "CAM-HOLDER"))
    )
    (comp (ref "H2")
      (value "CAM-HOLDER")
      (footprint "eagle-import:CAM-HOLDER")
      (libsource (lib "eagle-import") (part "CAM-HOLDER"))
    )
    (comp (ref "H3")
      (value "MOUNT-HOLE3.2")
      (footprint "eagle-import:3,2")
      (libsource (lib "eagle-import") (part "MOUNT-HOLE3.2"))
    )
    (comp (ref "H4")
      (value "MOUNT-HOLE3.2")
      (footprint "eagle-import:3,2")
      (libsource (lib "eagle-import") (part "MOUNT-HOLE3.2"))
    )
    (comp (ref "H5")
      (value "MOUNT-HOLE3.2")
      (footprint "eagle-import:3,2")
      (libsource (lib "eagle-import") (part "MOUNT-HOLE3.2"))
    )
    (comp (ref "H6")
      (value "MOUNT-HOLE3.2")
      (footprint "eagle-import:3,2")
      (libsource (lib "eagle-import") (part "MOUNT-HOLE3.2"))
    )
    (comp (ref "H7")
      (value "MOUNT-HOLE3.2")
      (footprint "eagle-import:3,2")
      (libsource (lib "eagle-import") (part "MOUNT-HOLE3.2"))
    )
    (comp (ref "H8")
      (value "MOUNT-HOLE3.2")
      (footprint "eagle-import:3,2")
      (libsource (lib "eagle-import") (part "MOUNT-HOLE3.2"))
    )
    (comp (ref "IC1")
      (value "PIC32MX470F512L-I/PF")
      (footprint "eagle-import:TQFP100_14X14_0,5MM")
      (libsource (lib "eagle-import") (part "PIC32MX470F512L-I/PF"))
    )
    (comp (ref "IC2")
      (value "R1LV1616")
      (footprint "eagle-import:48-TSOP-I")
      (libsource (lib "eagle-import") (part "R1LV1616HSA"))
    )
    (comp (ref "IC3")
      (value "74LVC573APW-TSSOP20")
      (footprint "eagle-import:TSSOP20")
      (libsource (lib "eagle-import") (part "74LVC573APW-TSSOP20"))
    )
    (comp (ref "IC4")
      (value "74LVC573APW-TSSOP20")
      (footprint "eagle-import:TSSOP20")
      (libsource (lib "eagle-import") (part "74LVC573APW-TSSOP20"))
    )
    (comp (ref "IC5")
      (value "TLV73315PDBV")
      (footprint "eagle-import:SOT23-5")
      (libsource (lib "eagle-import") (part "TLV73315PDBV"))
    )
    (comp (ref "IC6")
      (value "MIC841LYC")
      (footprint "eagle-import:SC-70-5")
      (libsource (lib "eagle-import") (part "MIC841LYC"))
    )
    (comp (ref "IC7")
      (value "24LC32A-I/MS")
      (footprint "eagle-import:MSOP-08")
      (libsource (lib "eagle-import") (part "24-I/MS"))
    )
    (comp (ref "IC8")
      (value "LT3971EMSE")
      (footprint "eagle-import:MSOP10EXP")
      (libsource (lib "eagle-import") (part "LT3971EMSE"))
    )
    (comp (ref "IC9")
      (value "AT25SF321-SSHD")
      (footprint "eagle-import:SO-08")
      (libsource (lib "eagle-import") (part "M25P16-VMN6P"))
    )
    (comp (ref "IC10")
      (value "MAX9938HEUK+T")
      (footprint "eagle-import:SOT23-5")
      (libsource (lib "eagle-import") (part "TSM9938HEUK+T"))
    )
    (comp (ref "IC11")
      (value "24LC32A-I/MS")
      (footprint "eagle-import:MSOP-08")
      (libsource (lib "eagle-import") (part "24-I/MS"))
    )
    (comp (ref "IC12")
      (value "SN65HVD12D")
      (footprint "eagle-import:SO08")
      (libsource (lib "eagle-import") (part "SN65HVD3082ED"))
    )
    (comp (ref "IC13")
      (value "REF3025")
      (footprint "eagle-import:SOT23")
      (libsource (lib "eagle-import") (part "REF3025"))
    )
    (comp (ref "IC14")
      (value "TPD2E001DZDR")
      (footprint "eagle-import:SOT-143")
      (libsource (lib "eagle-import") (part "SR05.TCT"))
    )
    (comp (ref "IC15")
      (value "TPD2E001DZDR")
      (footprint "eagle-import:SOT-143")
      (libsource (lib "eagle-import") (part "SR05.TCT"))
    )
    (comp (ref "IC16")
      (value "MCP6042-I/MS")
      (footprint "eagle-import:MSOP-08")
      (libsource (lib "eagle-import") (part "MCP6042-I/MS"))
    )
    (comp (ref "J1")
      (value "FH12A-24S-0.5SH")
      (footprint "eagle-import:FH12A-24S-05SH")
      (libsource (lib "eagle-import") (part "FH12A-24S-0.5SH"))
    )
    (comp (ref "J2")
      (value "FH12A-24S-0.5SH")
      (footprint "eagle-import:FH12A-24S-05SH")
      (libsource (lib "eagle-import") (part "FH12A-24S-0.5SH"))
    )
    (comp (ref "J3")
      (value "RJ8-8-180")
      (footprint "eagle-import:RJ8-8-180")
      (libsource (lib "eagle-import") (part "RJ8-8-180"))
    )
    (comp (ref "J4")
      (value "RJ8-8-180")
      (footprint "eagle-import:RJ8-8-180")
      (libsource (lib "eagle-import") (part "RJ8-8-180"))
    )
    (comp (ref "J5")
      (value "MOLEX430450613")
      (footprint "eagle-import:MOLEX430450613")
      (libsource (lib "eagle-import") (part "MOLEX430450613"))
    )
    (comp (ref "J6")
      (value "MOLEX430450613")
      (footprint "eagle-import:MOLEX430450613")
      (libsource (lib "eagle-import") (part "MOLEX430450613"))
    )
    (comp (ref "J7")
      (value "3-641215-2")
      (footprint "eagle-import:3-641215-2")
      (libsource (lib "eagle-import") (part "3-641215-2"))
    )
    (comp (ref "J8")
      (value "3-641215-2")
      (footprint "eagle-import:3-641215-2")
      (libsource (lib "eagle-import") (part "3-641215-2"))
    )
    (comp (ref "J9")
      (value "3-641215-2")
      (footprint "eagle-import:3-641215-2")
      (libsource (lib "eagle-import") (part "3-641215-2"))
    )
    (comp (ref "J10")
      (value "3-641215-2")
      (footprint "eagle-import:3-641215-2")
      (libsource (lib "eagle-import") (part "3-641215-2"))
    )
    (comp (ref "J11")
      (value "3-641215-2")
      (footprint "eagle-import:3-641215-2")
      (libsource (lib "eagle-import") (part "3-641215-2"))
    )
    (comp (ref "J12")
      (value "USB_A_180")
      (footprint "eagle-import:USB_B_180")
      (libsource (lib "eagle-import") (part "USB_B_180"))
    )
    (comp (ref "J13")
      (value "MTA07-156")
      (footprint "eagle-import:1X7MTA")
      (libsource (lib "eagle-import") (part "MTA07-156"))
    )
    (comp (ref "J14")
      (value "pin1x8")
      (footprint "eagle-import:MA08-1-MALE")
      (libsource (lib "eagle-import") (part "MA08-1-M"))
    )
    (comp (ref "J15")
      (value "3-641215-2")
      (footprint "eagle-import:3-641215-2")
      (libsource (lib "eagle-import") (part "3-641215-2"))
    )
    (comp (ref "J16")
      (value "3-641215-2")
      (footprint "eagle-import:3-641215-2")
      (libsource (lib "eagle-import") (part "3-641215-2"))
    )
    (comp (ref "J17")
      (value "DNP-open-hole")
      (footprint "eagle-import:MA05-1")
      (libsource (lib "eagle-import") (part "MA05-1"))
    )
    (comp (ref "J18")
      (value "3-641215-2")
      (footprint "eagle-import:3-641215-2")
      (libsource (lib "eagle-import") (part "3-641215-2"))
    )
    (comp (ref "JP1")
      (value "JP3CLOSE12")
      (footprint "eagle-import:JP3CLOSE12")
      (libsource (lib "eagle-import") (part "JP3CLOSE12"))
    )
    (comp (ref "L1")
      (value "LQM31PN3R3M00L")
      (footprint "eagle-import:1206@1")
      (libsource (lib "eagle-import") (part "L-1206"))
    )
    (comp (ref "L2")
      (value "LQM31PN3R3M00L")
      (footprint "eagle-import:1206@1")
      (libsource (lib "eagle-import") (part "L-1206"))
    )
    (comp (ref "L3")
      (value "LQM31PN3R3M00L")
      (footprint "eagle-import:1206@1")
      (libsource (lib "eagle-import") (part "L-1206"))
    )
    (comp (ref "L4")
      (value "LQM31PN3R3M00L")
      (footprint "eagle-import:1206@1")
      (libsource (lib "eagle-import") (part "L-1206"))
    )
    (comp (ref "L5")
      (value "LQM31PN3R3M00L")
      (footprint "eagle-import:1206@1")
      (libsource (lib "eagle-import") (part "L-1206"))
    )
    (comp (ref "L6")
      (value "LQM31PN3R3M00L")
      (footprint "eagle-import:1206@1")
      (libsource (lib "eagle-import") (part "L-1206"))
    )
    (comp (ref "L7")
      (value "HI1206T500R")
      (footprint "eagle-import:1206@1")
      (libsource (lib "eagle-import") (part "L-1206"))
    )
    (comp (ref "L8")
      (value "HI1206T500R")
      (footprint "eagle-import:1206@1")
      (libsource (lib "eagle-import") (part "L-1206"))
    )
    (comp (ref "L9")
      (value "NR6028T4R7M")
      (footprint "eagle-import:NR6028")
      (libsource (lib "eagle-import") (part "NR6028"))
    )
    (comp (ref "L10")
      (value "HI1206T500R")
      (footprint "eagle-import:1206@1")
      (libsource (lib "eagle-import") (part "L-1206"))
    )
    (comp (ref "L11")
      (value "HI1206T500R")
      (footprint "eagle-import:1206@1")
      (libsource (lib "eagle-import") (part "L-1206"))
    )
    (comp (ref "L12")
      (value "HI1206T500R")
      (footprint "eagle-import:1206@1")
      (libsource (lib "eagle-import") (part "L-1206"))
    )
    (comp (ref "L13")
      (value "LQM31PN3R3M00L")
      (footprint "eagle-import:1206@1")
      (libsource (lib "eagle-import") (part "L-1206"))
    )
    (comp (ref "O1")
      (value "PIC-OUT")
      (footprint "eagle-import:TEMP-PAD")
      (libsource (lib "eagle-import") (part "PIC-OUT"))
    )
    (comp (ref "O2")
      (value "PIC-RPX")
      (footprint "eagle-import:TEMP-PAD")
      (libsource (lib "eagle-import") (part "PIC-RPX"))
    )
    (comp (ref "O3")
      (value "PIC-RPX")
      (footprint "eagle-import:TEMP-PAD")
      (libsource (lib "eagle-import") (part "PIC-RPX"))
    )
    (comp (ref "O4")
      (value "PIC-RPX")
      (footprint "eagle-import:TEMP-PAD")
      (libsource (lib "eagle-import") (part "PIC-RPX"))
    )
    (comp (ref "O6")
      (value "PIC-RPX")
      (footprint "eagle-import:TEMP-PAD")
      (libsource (lib "eagle-import") (part "PIC-RPX"))
    )
    (comp (ref "O7")
      (value "PIC-RPX")
      (footprint "eagle-import:TEMP-PAD")
      (libsource (lib "eagle-import") (part "PIC-RPX"))
    )
    (comp (ref "O8")
      (value "PIC-RPX")
      (footprint "eagle-import:TEMP-PAD")
      (libsource (lib "eagle-import") (part "PIC-RPX"))
    )
    (comp (ref "O9")
      (value "PIC-OUT")
      (footprint "eagle-import:TEMP-PAD")
      (libsource (lib "eagle-import") (part "PIC-OUT"))
    )
    (comp (ref "O12")
      (value "PIC-RPX")
      (footprint "eagle-import:TEMP-PAD")
      (libsource (lib "eagle-import") (part "PIC-RPX"))
    )
    (comp (ref "O13")
      (value "PIC-RPX")
      (footprint "eagle-import:TEMP-PAD")
      (libsource (lib "eagle-import") (part "PIC-RPX"))
    )
    (comp (ref "O14")
      (value "PIC-RPX")
      (footprint "eagle-import:TEMP-PAD")
      (libsource (lib "eagle-import") (part "PIC-RPX"))
    )
    (comp (ref "O15")
      (value "PIC-RPX")
      (footprint "eagle-import:TEMP-PAD")
      (libsource (lib "eagle-import") (part "PIC-RPX"))
    )
    (comp (ref "O16")
      (value "PIC-RPX")
      (footprint "eagle-import:TEMP-PAD")
      (libsource (lib "eagle-import") (part "PIC-RPX"))
    )
    (comp (ref "O17")
      (value "PIC-OUT")
      (footprint "eagle-import:TEMP-PAD")
      (libsource (lib "eagle-import") (part "PIC-OUT"))
    )
    (comp (ref "O18")
      (value "PIC-RPX")
      (footprint "eagle-import:TEMP-PAD")
      (libsource (lib "eagle-import") (part "PIC-RPX"))
    )
    (comp (ref "O19")
      (value "PIC-RPX")
      (footprint "eagle-import:TEMP-PAD")
      (libsource (lib "eagle-import") (part "PIC-RPX"))
    )
    (comp (ref "O20")
      (value "PIC-RPX")
      (footprint "eagle-import:TEMP-PAD")
      (libsource (lib "eagle-import") (part "PIC-RPX"))
    )
    (comp (ref "O21")
      (value "PIC-RPX")
      (footprint "eagle-import:TEMP-PAD")
      (libsource (lib "eagle-import") (part "PIC-RPX"))
    )
    (comp (ref "O22")
      (value "PIC-OUT")
      (footprint "eagle-import:TEMP-PAD")
      (libsource (lib "eagle-import") (part "PIC-OUT"))
    )
    (comp (ref "O23")
      (value "PIC-OUT")
      (footprint "eagle-import:TEMP-PAD")
      (libsource (lib "eagle-import") (part "PIC-OUT"))
    )
    (comp (ref "O24")
      (value "PIC-OUT")
      (footprint "eagle-import:TEMP-PAD")
      (libsource (lib "eagle-import") (part "PIC-OUT"))
    )
    (comp (ref "O25")
      (value "PIC-OUT")
      (footprint "eagle-import:TEMP-PAD")
      (libsource (lib "eagle-import") (part "PIC-OUT"))
    )
    (comp (ref "O26")
      (value "PIC-OUT")
      (footprint "eagle-import:TEMP-PAD")
      (libsource (lib "eagle-import") (part "PIC-OUT"))
    )
    (comp (ref "O27")
      (value "PIC-RPX")
      (footprint "eagle-import:TEMP-PAD")
      (libsource (lib "eagle-import") (part "PIC-RPX"))
    )
    (comp (ref "O28")
      (value "PIC-RPX")
      (footprint "eagle-import:TEMP-PAD")
      (libsource (lib "eagle-import") (part "PIC-RPX"))
    )
    (comp (ref "O29")
      (value "PIC-RPX")
      (footprint "eagle-import:TEMP-PAD")
      (libsource (lib "eagle-import") (part "PIC-RPX"))
    )
    (comp (ref "O30")
      (value "PIC-RPX")
      (footprint "eagle-import:TEMP-PAD")
      (libsource (lib "eagle-import") (part "PIC-RPX"))
    )
    (comp (ref "O31")
      (value "PIC-OUT")
      (footprint "eagle-import:TEMP-PAD")
      (libsource (lib "eagle-import") (part "PIC-OUT"))
    )
    (comp (ref "O32")
      (value "PIC-OUT")
      (footprint "eagle-import:TEMP-PAD")
      (libsource (lib "eagle-import") (part "PIC-OUT"))
    )
    (comp (ref "O33")
      (value "PIC-RPX")
      (footprint "eagle-import:TEMP-PAD")
      (libsource (lib "eagle-import") (part "PIC-RPX"))
    )
    (comp (ref "O34")
      (value "PIC-RPX")
      (footprint "eagle-import:TEMP-PAD")
      (libsource (lib "eagle-import") (part "PIC-RPX"))
    )
    (comp (ref "O35")
      (value "PIC-RPX")
      (footprint "eagle-import:TEMP-PAD")
      (libsource (lib "eagle-import") (part "PIC-RPX"))
    )
    (comp (ref "O36")
      (value "PIC-RPX")
      (footprint "eagle-import:TEMP-PAD")
      (libsource (lib "eagle-import") (part "PIC-RPX"))
    )
    (comp (ref "O37")
      (value "PIC-RPX")
      (footprint "eagle-import:TEMP-PAD")
      (libsource (lib "eagle-import") (part "PIC-RPX"))
    )
    (comp (ref "O38")
      (value "PIC-RPX")
      (footprint "eagle-import:TEMP-PAD")
      (libsource (lib "eagle-import") (part "PIC-RPX"))
    )
    (comp (ref "O39")
      (value "PIC-OUT")
      (footprint "eagle-import:TEMP-PAD")
      (libsource (lib "eagle-import") (part "PIC-OUT"))
    )
    (comp (ref "O40")
      (value "PIC-OUT")
      (footprint "eagle-import:TEMP-PAD")
      (libsource (lib "eagle-import") (part "PIC-OUT"))
    )
    (comp (ref "O41")
      (value "PIC-RPX")
      (footprint "eagle-import:TEMP-PAD")
      (libsource (lib "eagle-import") (part "PIC-RPX"))
    )
    (comp (ref "O42")
      (value "PIC-RPX")
      (footprint "eagle-import:TEMP-PAD")
      (libsource (lib "eagle-import") (part "PIC-RPX"))
    )
    (comp (ref "O43")
      (value "PIC-RPX")
      (footprint "eagle-import:TEMP-PAD")
      (libsource (lib "eagle-import") (part "PIC-RPX"))
    )
    (comp (ref "O44")
      (value "PIC-OUT")
      (footprint "eagle-import:TEMP-PAD")
      (libsource (lib "eagle-import") (part "PIC-OUT"))
    )
    (comp (ref "PCB3")
      (value "DNP-PCB-BT")
      (footprint "eagle-import:BT_MODULE_BRD")
      (libsource (lib "eagle-import") (part "BT_PCBBRD"))
    )
    (comp (ref "Q1")
      (value "SSM6P49NU,LFPZ")
      (footprint "eagle-import:MICRO_FET")
      (libsource (lib "eagle-import") (part "SSM6P49PZNU,LF"))
    )
    (comp (ref "Q2")
      (value "SSM6P49NU,LFPZ")
      (footprint "eagle-import:MICRO_FET")
      (libsource (lib "eagle-import") (part "SSM6P49PZNU,LF"))
    )
    (comp (ref "Q3")
      (value "FDG6303N")
      (footprint "eagle-import:SC70-6")
      (libsource (lib "eagle-import") (part "FDG6303N"))
    )
    (comp (ref "Q4")
      (value "FDG6303N")
      (footprint "eagle-import:SC70-6")
      (libsource (lib "eagle-import") (part "FDG6303N"))
    )
    (comp (ref "Q5")
      (value "FDC6506P")
      (footprint "eagle-import:SSOT-6")
      (libsource (lib "eagle-import") (part "FDC6506D"))
    )
    (comp (ref "Q6")
      (value "FDC6506P")
      (footprint "eagle-import:SSOT-6")
      (libsource (lib "eagle-import") (part "FDC6506D"))
    )
    (comp (ref "Q7")
      (value "FDG6303N")
      (footprint "eagle-import:SC70-6")
      (libsource (lib "eagle-import") (part "FDG6303N"))
    )
    (comp (ref "Q8")
      (value "FDC6506P")
      (footprint "eagle-import:SSOT-6")
      (libsource (lib "eagle-import") (part "FDC6506D"))
    )
    (comp (ref "Q9")
      (value "FDG6303N")
      (footprint "eagle-import:SC70-6")
      (libsource (lib "eagle-import") (part "FDG6303N"))
    )
    (comp (ref "Q10")
      (value "FDG6303N")
      (footprint "eagle-import:SC70-6")
      (libsource (lib "eagle-import") (part "FDG6303N"))
    )
    (comp (ref "Q11")
      (value "FDG6303N")
      (footprint "eagle-import:SC70-6")
      (libsource (lib "eagle-import") (part "FDG6303N"))
    )
    (comp (ref "Q12")
      (value "FDG6303N")
      (footprint "eagle-import:SC70-6")
      (libsource (lib "eagle-import") (part "FDG6303N"))
    )
    (comp (ref "Q13")
      (value "FDG6303N")
      (footprint "eagle-import:SC70-6")
      (libsource (lib "eagle-import") (part "FDG6303N"))
    )
    (comp (ref "Q14")
      (value "FDG6303N")
      (footprint "eagle-import:SC70-6")
      (libsource (lib "eagle-import") (part "FDG6303N"))
    )
    (comp (ref "R1")
      (value "1M")
      (footprint "eagle-import:0603@1")
      (libsource (lib "eagle-import") (part "R-0603"))
    )
    (comp (ref "R2")
      (value "1M")
      (footprint "eagle-import:0603@1")
      (libsource (lib "eagle-import") (part "R-0603"))
    )
    (comp (ref "R3")
      (value "1M")
      (footprint "eagle-import:0603@1")
      (libsource (lib "eagle-import") (part "R-0603"))
    )
    (comp (ref "R4")
      (value "1M")
      (footprint "eagle-import:0603@1")
      (libsource (lib "eagle-import") (part "R-0603"))
    )
    (comp (ref "R5")
      (value "1M")
      (footprint "eagle-import:0603@1")
      (libsource (lib "eagle-import") (part "R-0603"))
    )
    (comp (ref "R6")
      (value "0R")
      (footprint "eagle-import:0603@1")
      (libsource (lib "eagle-import") (part "R-0603"))
    )
    (comp (ref "R7")
      (value "0R")
      (footprint "eagle-import:0603@1")
      (libsource (lib "eagle-import") (part "R-0603"))
    )
    (comp (ref "R8")
      (value "1R")
      (footprint "eagle-import:0805")
      (libsource (lib "eagle-import") (part "R-0805"))
    )
    (comp (ref "R9")
      (value "1M")
      (footprint "eagle-import:0603@1")
      (libsource (lib "eagle-import") (part "R-0603"))
    )
    (comp (ref "R10")
      (value "100k")
      (footprint "eagle-import:0603@1")
      (libsource (lib "eagle-import") (part "R-0603"))
    )
    (comp (ref "R11")
      (value "10k")
      (footprint "eagle-import:0603@1")
      (libsource (lib "eagle-import") (part "R-0603"))
    )
    (comp (ref "R12")
      (value "100k")
      (footprint "eagle-import:0603@1")
      (libsource (lib "eagle-import") (part "R-0603"))
    )
    (comp (ref "R13")
      (value "10k")
      (footprint "eagle-import:0603@1")
      (libsource (lib "eagle-import") (part "R-0603"))
    )
    (comp (ref "R14")
      (value "10k")
      (footprint "eagle-import:0603@1")
      (libsource (lib "eagle-import") (part "R-0603"))
    )
    (comp (ref "R15")
      (value "10k")
      (footprint "eagle-import:0603@1")
      (libsource (lib "eagle-import") (part "R-0603"))
    )
    (comp (ref "R16")
      (value "100k")
      (footprint "eagle-import:0603@1")
      (libsource (lib "eagle-import") (part "R-0603"))
    )
    (comp (ref "R17")
      (value "47k")
      (footprint "eagle-import:0603@1")
      (libsource (lib "eagle-import") (part "R-0603"))
    )
    (comp (ref "R18")
      (value "10k")
      (footprint "eagle-import:0603@1")
      (libsource (lib "eagle-import") (part "R-0603"))
    )
    (comp (ref "R19")
      (value "560k")
      (footprint "eagle-import:0603@1")
      (libsource (lib "eagle-import") (part "R-0603"))
    )
    (comp (ref "R20")
      (value "1M")
      (footprint "eagle-import:0603@1")
      (libsource (lib "eagle-import") (part "R-0603"))
    )
    (comp (ref "R21")
      (value "1M")
      (footprint "eagle-import:0603@1")
      (libsource (lib "eagle-import") (part "R-0603"))
    )
    (comp (ref "R22")
      (value "4M99")
      (footprint "eagle-import:0603@1")
      (libsource (lib "eagle-import") (part "R-0603"))
    )
    (comp (ref "R23")
      (value "0R/1M")
      (footprint "eagle-import:0603@1")
      (libsource (lib "eagle-import") (part "R-0603"))
    )
    (comp (ref "R24")
      (value "100k")
      (footprint "eagle-import:0603@1")
      (libsource (lib "eagle-import") (part "R-0603"))
    )
    (comp (ref "R25")
      (value "1M")
      (footprint "eagle-import:0603@1")
      (libsource (lib "eagle-import") (part "R-0603"))
    )
    (comp (ref "R26")
      (value "10k")
      (footprint "eagle-import:0603@1")
      (libsource (lib "eagle-import") (part "R-0603"))
    )
    (comp (ref "R27")
      (value "10k")
      (footprint "eagle-import:0603@1")
      (libsource (lib "eagle-import") (part "R-0603"))
    )
    (comp (ref "R28")
      (value "100R")
      (footprint "eagle-import:0603@1")
      (libsource (lib "eagle-import") (part "R-0603"))
    )
    (comp (ref "R29")
      (value "300R")
      (footprint "eagle-import:0603@1")
      (libsource (lib "eagle-import") (part "R-0603"))
    )
    (comp (ref "R30")
      (value "1M")
      (footprint "eagle-import:0603@1")
      (libsource (lib "eagle-import") (part "R-0603"))
    )
    (comp (ref "R31")
      (value "1M")
      (footprint "eagle-import:0603@1")
      (libsource (lib "eagle-import") (part "R-0603"))
    )
    (comp (ref "R32")
      (value "1M")
      (footprint "eagle-import:0603@1")
      (libsource (lib "eagle-import") (part "R-0603"))
    )
    (comp (ref "R33")
      (value "4M99")
      (footprint "eagle-import:0603@1")
      (libsource (lib "eagle-import") (part "R-0603"))
    )
    (comp (ref "R34")
      (value "1M")
      (footprint "eagle-import:0603@1")
      (libsource (lib "eagle-import") (part "R-0603"))
    )
    (comp (ref "R35")
      (value "1k")
      (footprint "eagle-import:0805")
      (libsource (lib "eagle-import") (part "R-0805"))
    )
    (comp (ref "R36")
      (value "1k")
      (footprint "eagle-import:0805")
      (libsource (lib "eagle-import") (part "R-0805"))
    )
    (comp (ref "R37")
      (value "1k")
      (footprint "eagle-import:0805")
      (libsource (lib "eagle-import") (part "R-0805"))
    )
    (comp (ref "R38")
      (value "1k")
      (footprint "eagle-import:0805")
      (libsource (lib "eagle-import") (part "R-0805"))
    )
    (comp (ref "R39")
      (value "0.025R")
      (footprint "eagle-import:0805")
      (libsource (lib "eagle-import") (part "R-0805"))
    )
    (comp (ref "R40")
      (value "300k")
      (footprint "eagle-import:0603@1")
      (libsource (lib "eagle-import") (part "R-0603"))
    )
    (comp (ref "R41")
      (value "1M")
      (footprint "eagle-import:0603@1")
      (libsource (lib "eagle-import") (part "R-0603"))
    )
    (comp (ref "R42")
      (value "1M")
      (footprint "eagle-import:0603@1")
      (libsource (lib "eagle-import") (part "R-0603"))
    )
    (comp (ref "R43")
      (value "300k")
      (footprint "eagle-import:0603@1")
      (libsource (lib "eagle-import") (part "R-0603"))
    )
    (comp (ref "R44")
      (value "1M")
      (footprint "eagle-import:0603@1")
      (libsource (lib "eagle-import") (part "R-0603"))
    )
    (comp (ref "R45")
      (value "1M")
      (footprint "eagle-import:0603@1")
      (libsource (lib "eagle-import") (part "R-0603"))
    )
    (comp (ref "R46")
      (value "560k")
      (footprint "eagle-import:0603@1")
      (libsource (lib "eagle-import") (part "R-0603"))
    )
    (comp (ref "R47")
      (value "100k")
      (footprint "eagle-import:0603@1")
      (libsource (lib "eagle-import") (part "R-0603"))
    )
    (comp (ref "R48")
      (value "1M")
      (footprint "eagle-import:0603@1")
      (libsource (lib "eagle-import") (part "R-0603"))
    )
    (comp (ref "R49")
      (value "1M")
      (footprint "eagle-import:0603@1")
      (libsource (lib "eagle-import") (part "R-0603"))
    )
    (comp (ref "R50")
      (value "1M")
      (footprint "eagle-import:0603@1")
      (libsource (lib "eagle-import") (part "R-0603"))
    )
    (comp (ref "R51")
      (value "300k")
      (footprint "eagle-import:0603@1")
      (libsource (lib "eagle-import") (part "R-0603"))
    )
    (comp (ref "R52")
      (value "1M")
      (footprint "eagle-import:0603@1")
      (libsource (lib "eagle-import") (part "R-0603"))
    )
    (comp (ref "R53")
      (value "300k")
      (footprint "eagle-import:0603@1")
      (libsource (lib "eagle-import") (part "R-0603"))
    )
    (comp (ref "R54")
      (value "1M")
      (footprint "eagle-import:0603@1")
      (libsource (lib "eagle-import") (part "R-0603"))
    )
    (comp (ref "R55")
      (value "1M")
      (footprint "eagle-import:0603@1")
      (libsource (lib "eagle-import") (part "R-0603"))
    )
    (comp (ref "R56")
      (value "1M")
      (footprint "eagle-import:0603@1")
      (libsource (lib "eagle-import") (part "R-0603"))
    )
    (comp (ref "R57")
      (value "300k")
      (footprint "eagle-import:0603@1")
      (libsource (lib "eagle-import") (part "R-0603"))
    )
    (comp (ref "R58")
      (value "1M")
      (footprint "eagle-import:0603@1")
      (libsource (lib "eagle-import") (part "R-0603"))
    )
    (comp (ref "R59")
      (value "300k")
      (footprint "eagle-import:0603@1")
      (libsource (lib "eagle-import") (part "R-0603"))
    )
    (comp (ref "R60")
      (value "1M")
      (footprint "eagle-import:0603@1")
      (libsource (lib "eagle-import") (part "R-0603"))
    )
    (comp (ref "R61")
      (value "1M")
      (footprint "eagle-import:0603@1")
      (libsource (lib "eagle-import") (part "R-0603"))
    )
    (comp (ref "R62")
      (value "100R")
      (footprint "eagle-import:0603@1")
      (libsource (lib "eagle-import") (part "R-0603"))
    )
    (comp (ref "R63")
      (value "1k->4k7")
      (footprint "eagle-import:0603@1")
      (libsource (lib "eagle-import") (part "R-0603"))
    )
    (comp (ref "R64")
      (value "1k")
      (footprint "eagle-import:0603@1")
      (libsource (lib "eagle-import") (part "R-0603"))
    )
    (comp (ref "R65")
      (value "1M")
      (footprint "eagle-import:0603@1")
      (libsource (lib "eagle-import") (part "R-0603"))
    )
    (comp (ref "R66")
      (value "100k")
      (footprint "eagle-import:0603@1")
      (libsource (lib "eagle-import") (part "R-0603"))
    )
    (comp (ref "R67")
      (value "1M")
      (footprint "eagle-import:0603@1")
      (libsource (lib "eagle-import") (part "R-0603"))
    )
    (comp (ref "R68")
      (value "100R")
      (footprint "eagle-import:0603@1")
      (libsource (lib "eagle-import") (part "R-0603"))
    )
    (comp (ref "R69")
      (value "1k->4k7")
      (footprint "eagle-import:0603@1")
      (libsource (lib "eagle-import") (part "R-0603"))
    )
    (comp (ref "R70")
      (value "1k")
      (footprint "eagle-import:0603@1")
      (libsource (lib "eagle-import") (part "R-0603"))
    )
    (comp (ref "R71")
      (value "10k")
      (footprint "eagle-import:0603@1")
      (libsource (lib "eagle-import") (part "R-0603"))
    )
    (comp (ref "R72")
      (value "1M")
      (footprint "eagle-import:0603@1")
      (libsource (lib "eagle-import") (part "R-0603"))
    )
    (comp (ref "R73")
      (value "1M")
      (footprint "eagle-import:0603@1")
      (libsource (lib "eagle-import") (part "R-0603"))
    )
    (comp (ref "R74")
      (value "100k")
      (footprint "eagle-import:0603@1")
      (libsource (lib "eagle-import") (part "R-0603"))
    )
    (comp (ref "R75")
      (value "100k")
      (footprint "eagle-import:0603@1")
      (libsource (lib "eagle-import") (part "R-0603"))
    )
    (comp (ref "R76")
      (value "1M")
      (footprint "eagle-import:0603@1")
      (libsource (lib "eagle-import") (part "R-0603"))
    )
    (comp (ref "R77")
      (value "47k")
      (footprint "eagle-import:0603@1")
      (libsource (lib "eagle-import") (part "R-0603"))
    )
    (comp (ref "R78")
      (value "100R")
      (footprint "eagle-import:0603@1")
      (libsource (lib "eagle-import") (part "R-0603"))
    )
    (comp (ref "R79")
      (value "1k->4k7")
      (footprint "eagle-import:0603@1")
      (libsource (lib "eagle-import") (part "R-0603"))
    )
    (comp (ref "R80")
      (value "1k")
      (footprint "eagle-import:0603@1")
      (libsource (lib "eagle-import") (part "R-0603"))
    )
    (comp (ref "R81")
      (value "100k")
      (footprint "eagle-import:0603@1")
      (libsource (lib "eagle-import") (part "R-0603"))
    )
    (comp (ref "R82")
      (value "1M")
      (footprint "eagle-import:0603@1")
      (libsource (lib "eagle-import") (part "R-0603"))
    )
    (comp (ref "R83")
      (value "1M")
      (footprint "eagle-import:0603@1")
      (libsource (lib "eagle-import") (part "R-0603"))
    )
    (comp (ref "R84")
      (value "100R")
      (footprint "eagle-import:0603@1")
      (libsource (lib "eagle-import") (part "R-0603"))
    )
    (comp (ref "R85")
      (value "1k->4k7")
      (footprint "eagle-import:0603@1")
      (libsource (lib "eagle-import") (part "R-0603"))
    )
    (comp (ref "R86")
      (value "1k")
      (footprint "eagle-import:0603@1")
      (libsource (lib "eagle-import") (part "R-0603"))
    )
    (comp (ref "R87")
      (value "1M")
      (footprint "eagle-import:0603@1")
      (libsource (lib "eagle-import") (part "R-0603"))
    )
    (comp (ref "R88")
      (value "1M")
      (footprint "eagle-import:0603@1")
      (libsource (lib "eagle-import") (part "R-0603"))
    )
    (comp (ref "R89")
      (value "100k")
      (footprint "eagle-import:0603@1")
      (libsource (lib "eagle-import") (part "R-0603"))
    )
    (comp (ref "R90")
      (value "1k")
      (footprint "eagle-import:0603@1")
      (libsource (lib "eagle-import") (part "R-0603"))
    )
    (comp (ref "R91")
      (value "10k")
      (footprint "eagle-import:0603@1")
      (libsource (lib "eagle-import") (part "R-0603"))
    )
    (comp (ref "R92")
      (value "10R")
      (footprint "eagle-import:0603@1")
      (libsource (lib "eagle-import") (part "R-0603"))
    )
    (comp (ref "R93")
      (value "300R")
      (footprint "eagle-import:0603@1")
      (libsource (lib "eagle-import") (part "R-0603"))
    )
    (comp (ref "R94")
      (value "180k")
      (footprint "eagle-import:0603@1")
      (libsource (lib "eagle-import") (part "R-0603"))
    )
    (comp (ref "R95")
      (value "4M99")
      (footprint "eagle-import:0603@1")
      (libsource (lib "eagle-import") (part "R-0603"))
    )
    (comp (ref "R96")
      (value "560k")
      (footprint "eagle-import:0603@1")
      (libsource (lib "eagle-import") (part "R-0603"))
    )
    (comp (ref "R97")
      (value "180k")
      (footprint "eagle-import:0603@1")
      (libsource (lib "eagle-import") (part "R-0603"))
    )
    (comp (ref "R98")
      (value "4M99")
      (footprint "eagle-import:0603@1")
      (libsource (lib "eagle-import") (part "R-0603"))
    )
    (comp (ref "R99")
      (value "560k")
      (footprint "eagle-import:0603@1")
      (libsource (lib "eagle-import") (part "R-0603"))
    )
    (comp (ref "R100")
      (value "2k2")
      (footprint "eagle-import:0603@1")
      (libsource (lib "eagle-import") (part "R-0603"))
    )
    (comp (ref "R101")
      (value "2k2")
      (footprint "eagle-import:0603@1")
      (libsource (lib "eagle-import") (part "R-0603"))
    )
    (comp (ref "R102")
      (value "1k")
      (footprint "eagle-import:0603@1")
      (libsource (lib "eagle-import") (part "R-0603"))
    )
    (comp (ref "R103")
      (value "300R")
      (footprint "eagle-import:0603@1")
      (libsource (lib "eagle-import") (part "R-0603"))
    )
    (comp (ref "R104")
      (value "1R")
      (footprint "eagle-import:0805")
      (libsource (lib "eagle-import") (part "R-0805"))
    )
    (comp (ref "R105")
      (value "1R")
      (footprint "eagle-import:0805")
      (libsource (lib "eagle-import") (part "R-0805"))
    )
    (comp (ref "R106")
      (value "1R")
      (footprint "eagle-import:0805")
      (libsource (lib "eagle-import") (part "R-0805"))
    )
    (comp (ref "R107")
      (value "100k")
      (footprint "eagle-import:0603@1")
      (libsource (lib "eagle-import") (part "R-0603"))
    )
    (comp (ref "R108")
      (value "10R->1R->0R")
      (footprint "eagle-import:0603@1")
      (libsource (lib "eagle-import") (part "R-0603"))
    )
    (comp (ref "R109")
      (value "10R->1R->0R")
      (footprint "eagle-import:0603@1")
      (libsource (lib "eagle-import") (part "R-0603"))
    )
    (comp (ref "R110")
      (value "100R")
      (footprint "eagle-import:0603@1")
      (libsource (lib "eagle-import") (part "R-0603"))
    )
    (comp (ref "R111")
      (value "100R")
      (footprint "eagle-import:0603@1")
      (libsource (lib "eagle-import") (part "R-0603"))
    )
    (comp (ref "R112")
      (value "1M")
      (footprint "eagle-import:0603@1")
      (libsource (lib "eagle-import") (part "R-0603"))
    )
    (comp (ref "R113")
      (value "100R")
      (footprint "eagle-import:0603@1")
      (libsource (lib "eagle-import") (part "R-0603"))
    )
    (comp (ref "R114")
      (value "100R")
      (footprint "eagle-import:0603@1")
      (libsource (lib "eagle-import") (part "R-0603"))
    )
    (comp (ref "R115")
      (value "100R")
      (footprint "eagle-import:0603@1")
      (libsource (lib "eagle-import") (part "R-0603"))
    )
    (comp (ref "R116")
      (value "100R")
      (footprint "eagle-import:0603@1")
      (libsource (lib "eagle-import") (part "R-0603"))
    )
    (comp (ref "R117")
      (value "100R")
      (footprint "eagle-import:0603@1")
      (libsource (lib "eagle-import") (part "R-0603"))
    )
    (comp (ref "R118")
      (value "1M")
      (footprint "eagle-import:0603@1")
      (libsource (lib "eagle-import") (part "R-0603"))
    )
    (comp (ref "R119")
      (value "100R")
      (footprint "eagle-import:0603@1")
      (libsource (lib "eagle-import") (part "R-0603"))
    )
    (comp (ref "R120")
      (value "4.7K")
      (footprint "eagle-import:0603@1")
      (libsource (lib "eagle-import") (part "R-0603"))
    )
    (comp (ref "R121")
      (value "4.7K")
      (footprint "eagle-import:0603@1")
      (libsource (lib "eagle-import") (part "R-0603"))
    )
    (comp (ref "R122")
      (value "100R")
      (footprint "eagle-import:0603@1")
      (libsource (lib "eagle-import") (part "R-0603"))
    )
    (comp (ref "R123")
      (value "100R")
      (footprint "eagle-import:0603@1")
      (libsource (lib "eagle-import") (part "R-0603"))
    )
    (comp (ref "R124")
      (value "0R")
      (footprint "eagle-import:0603@1")
      (libsource (lib "eagle-import") (part "R-0603"))
    )
    (comp (ref "R125")
      (value "0R")
      (footprint "eagle-import:0603@1")
      (libsource (lib "eagle-import") (part "R-0603"))
    )
    (comp (ref "R126")
      (value "0R")
      (footprint "eagle-import:0603@1")
      (libsource (lib "eagle-import") (part "R-0603"))
    )
    (comp (ref "R127")
      (value "4.7K")
      (footprint "eagle-import:0603@1")
      (libsource (lib "eagle-import") (part "R-0603"))
    )
    (comp (ref "R128")
      (value "10k")
      (footprint "eagle-import:0603@1")
      (libsource (lib "eagle-import") (part "R-0603"))
    )
    (comp (ref "R129")
      (value "DNP/0R")
      (footprint "eagle-import:0603@1")
      (libsource (lib "eagle-import") (part "R-0603"))
    )
    (comp (ref "R130")
      (value "100k")
      (footprint "eagle-import:0603@1")
      (libsource (lib "eagle-import") (part "R-0603"))
    )
    (comp (ref "R131")
      (value "100k")
      (footprint "eagle-import:0603@1")
      (libsource (lib "eagle-import") (part "R-0603"))
    )
    (comp (ref "R132")
      (value "1M")
      (footprint "eagle-import:0603@1")
      (libsource (lib "eagle-import") (part "R-0603"))
    )
    (comp (ref "R133")
      (value "4.7K")
      (footprint "eagle-import:0603@1")
      (libsource (lib "eagle-import") (part "R-0603"))
    )
    (comp (ref "REF1")
      (value "REF")
      (footprint "eagle-import:REF")
      (libsource (lib "eagle-import") (part "REF"))
    )
    (comp (ref "REF2")
      (value "REF")
      (footprint "eagle-import:REF")
      (libsource (lib "eagle-import") (part "REF"))
    )
    (comp (ref "T1")
      (value "PIC-OUT")
      (footprint "eagle-import:TEMP-PAD")
      (libsource (lib "eagle-import") (part "PIC-OUT"))
    )
    (comp (ref "T2")
      (value "PIC-OUT")
      (footprint "eagle-import:TEMP-PAD")
      (libsource (lib "eagle-import") (part "PIC-OUT"))
    )
    (comp (ref "T3")
      (value "PIC-RPX")
      (footprint "eagle-import:TEMP-PAD")
      (libsource (lib "eagle-import") (part "PIC-RPX"))
    )
    (comp (ref "T4")
      (value "PIC-OUT")
      (footprint "eagle-import:TEMP-PAD")
      (libsource (lib "eagle-import") (part "PIC-OUT"))
    )
    (comp (ref "T5")
      (value "PIC-OUT")
      (footprint "eagle-import:TEMP-PAD")
      (libsource (lib "eagle-import") (part "PIC-OUT"))
    )
    (comp (ref "T6")
      (value "PIC-OUT")
      (footprint "eagle-import:TEMP-PAD")
      (libsource (lib "eagle-import") (part "PIC-OUT"))
    )
    (comp (ref "T7")
      (value "PIC-OUT")
      (footprint "eagle-import:TEMP-PAD")
      (libsource (lib "eagle-import") (part "PIC-OUT"))
    )
    (comp (ref "T8")
      (value "PIC-OUT")
      (footprint "eagle-import:TEMP-PAD")
      (libsource (lib "eagle-import") (part "PIC-OUT"))
    )
    (comp (ref "T9")
      (value "PIC-RPX")
      (footprint "eagle-import:TEMP-PAD")
      (libsource (lib "eagle-import") (part "PIC-RPX"))
    )
    (comp (ref "T10")
      (value "PIC-RPX")
      (footprint "eagle-import:TEMP-PAD")
      (libsource (lib "eagle-import") (part "PIC-RPX"))
    )
    (comp (ref "T11")
      (value "PIC-RPX")
      (footprint "eagle-import:TEMP-PAD")
      (libsource (lib "eagle-import") (part "PIC-RPX"))
    )
    (comp (ref "T12")
      (value "PIC-RPX")
      (footprint "eagle-import:TEMP-PAD")
      (libsource (lib "eagle-import") (part "PIC-RPX"))
    )
    (comp (ref "T13")
      (value "PIC-RPX")
      (footprint "eagle-import:TEMP-PAD")
      (libsource (lib "eagle-import") (part "PIC-RPX"))
    )
    (comp (ref "T14")
      (value "PIC-RPX")
      (footprint "eagle-import:TEMP-PAD")
      (libsource (lib "eagle-import") (part "PIC-RPX"))
    )
    (comp (ref "T15")
      (value "PIC-OUT")
      (footprint "eagle-import:TEMP-PAD")
      (libsource (lib "eagle-import") (part "PIC-OUT"))
    )
    (comp (ref "T16")
      (value "PIC-RPX")
      (footprint "eagle-import:TEMP-PAD")
      (libsource (lib "eagle-import") (part "PIC-RPX"))
    )
    (comp (ref "T17")
      (value "PIC-RPX")
      (footprint "eagle-import:TEMP-PAD")
      (libsource (lib "eagle-import") (part "PIC-RPX"))
    )
    (comp (ref "T18")
      (value "PIC-RPX")
      (footprint "eagle-import:TEMP-PAD")
      (libsource (lib "eagle-import") (part "PIC-RPX"))
    )
    (comp (ref "T19")
      (value "PIC-RPX")
      (footprint "eagle-import:TEMP-PAD")
      (libsource (lib "eagle-import") (part "PIC-RPX"))
    )
    (comp (ref "T20")
      (value "PIC-OUT")
      (footprint "eagle-import:TEMP-PAD")
      (libsource (lib "eagle-import") (part "PIC-OUT"))
    )
    (comp (ref "T21")
      (value "PIC-OUT")
      (footprint "eagle-import:TEMP-PAD")
      (libsource (lib "eagle-import") (part "PIC-OUT"))
    )
    (comp (ref "T27")
      (value "PIC-OUT")
      (footprint "eagle-import:TEMP-PAD")
      (libsource (lib "eagle-import") (part "PIC-OUT"))
    )
    (comp (ref "T28")
      (value "PIC-OUT")
      (footprint "eagle-import:TEMP-PAD")
      (libsource (lib "eagle-import") (part "PIC-OUT"))
    )
    (comp (ref "T30")
      (value "PIC-OUT")
      (footprint "eagle-import:TEMP-PAD")
      (libsource (lib "eagle-import") (part "PIC-OUT"))
    )
    (comp (ref "T31")
      (value "PIC-OUT")
      (footprint "eagle-import:TEMP-PAD")
      (libsource (lib "eagle-import") (part "PIC-OUT"))
    )
    (comp (ref "T32")
      (value "PIC-OUT")
      (footprint "eagle-import:TEMP-PAD")
      (libsource (lib "eagle-import") (part "PIC-OUT"))
    )
    (comp (ref "T33")
      (value "PIC-OUT")
      (footprint "eagle-import:TEMP-PAD")
      (libsource (lib "eagle-import") (part "PIC-OUT"))
    )
    (comp (ref "T34")
      (value "PIC-RPX")
      (footprint "eagle-import:TEMP-PAD")
      (libsource (lib "eagle-import") (part "PIC-RPX"))
    )
    (comp (ref "T35")
      (value "PIC-RPX")
      (footprint "eagle-import:TEMP-PAD")
      (libsource (lib "eagle-import") (part "PIC-RPX"))
    )
    (comp (ref "T36")
      (value "PIC-OUT")
      (footprint "eagle-import:TEMP-PAD")
      (libsource (lib "eagle-import") (part "PIC-OUT"))
    )
    (comp (ref "T37")
      (value "PIN-AN")
      (footprint "eagle-import:TEMP-PAD")
      (libsource (lib "eagle-import") (part "PIN-AN"))
    )
    (comp (ref "T38")
      (value "PIN-AN")
      (footprint "eagle-import:TEMP-PAD")
      (libsource (lib "eagle-import") (part "PIN-AN"))
    )
    (comp (ref "T39")
      (value "PIN-AN")
      (footprint "eagle-import:TEMP-PAD")
      (libsource (lib "eagle-import") (part "PIN-AN"))
    )
    (comp (ref "T40")
      (value "PIC-RPX")
      (footprint "eagle-import:TEMP-PAD")
      (libsource (lib "eagle-import") (part "PIC-RPX"))
    )
    (comp (ref "T41")
      (value "PIC-RPX")
      (footprint "eagle-import:TEMP-PAD")
      (libsource (lib "eagle-import") (part "PIC-RPX"))
    )
    (comp (ref "T42")
      (value "PIC-OUT")
      (footprint "eagle-import:TEMP-PAD")
      (libsource (lib "eagle-import") (part "PIC-OUT"))
    )
    (comp (ref "T43")
      (value "PIC-RPX")
      (footprint "eagle-import:TEMP-PAD")
      (libsource (lib "eagle-import") (part "PIC-RPX"))
    )
    (comp (ref "T44")
      (value "PIC-OUT")
      (footprint "eagle-import:TEMP-PAD")
      (libsource (lib "eagle-import") (part "PIC-OUT"))
    )
    (comp (ref "T45")
      (value "PIC-RPX")
      (footprint "eagle-import:TEMP-PAD")
      (libsource (lib "eagle-import") (part "PIC-RPX"))
    )
    (comp (ref "TP1")
      (value "DNP-TestPoint")
      (footprint "eagle-import:SMD_ROUND_1MM")
      (libsource (lib "eagle-import") (part "ROUND_SMD1MM"))
    )
    (comp (ref "TP2")
      (value "DNP-TestPoint")
      (footprint "eagle-import:TH_ROUND_14MM08MM")
      (libsource (lib "eagle-import") (part "ROUND_SMDTH1.4MM"))
    )
    (comp (ref "TP4")
      (value "DNP-TestPoint")
      (footprint "eagle-import:TH_ROUND_14MM08MM")
      (libsource (lib "eagle-import") (part "ROUND_SMDTH1.4MM"))
    )
    (comp (ref "X1")
      (value "8MHz-5x3.2mm")
      (footprint "eagle-import:7B")
      (libsource (lib "eagle-import") (part "XTAL-7B"))
    )
  )
  (nets
    (net (code "1") (name "+3.3V") (class "Default")
      (node (ref "C15") (pin "1") (pinfunction "1_1") (pintype "passive"))
      (node (ref "C21") (pin "1") (pinfunction "1_1") (pintype "passive"))
      (node (ref "C47") (pin "1") (pinfunction "1_1") (pintype "passive"))
      (node (ref "C48") (pin "1") (pinfunction "1_1") (pintype "passive"))
      (node (ref "C49") (pin "1") (pinfunction "1_1") (pintype "passive"))
      (node (ref "C50") (pin "1") (pinfunction "1_1") (pintype "passive"))
      (node (ref "C51") (pin "1") (pinfunction "1_1") (pintype "passive"))
      (node (ref "C52") (pin "1") (pinfunction "1_1") (pintype "passive"))
      (node (ref "C68") (pin "1") (pinfunction "1_1") (pintype "passive"))
      (node (ref "C69") (pin "1") (pinfunction "1_1") (pintype "passive"))
      (node (ref "C70") (pin "1") (pinfunction "1_1") (pintype "passive"))
      (node (ref "C81") (pin "+") (pinfunction "+_+") (pintype "passive"))
      (node (ref "IC1") (pin "16") (pinfunction "VDD3_16") (pintype "input"))
      (node (ref "IC1") (pin "2") (pinfunction "VDD2_2") (pintype "input"))
      (node (ref "IC1") (pin "37") (pinfunction "VDD4_37") (pintype "input"))
      (node (ref "IC1") (pin "46") (pinfunction "VDD5_46") (pintype "input"))
      (node (ref "IC1") (pin "55") (pinfunction "VUSB3V3_55") (pintype "input"))
      (node (ref "IC1") (pin "62") (pinfunction "VDD6_62") (pintype "input"))
      (node (ref "IC1") (pin "86") (pinfunction "VDD1_86") (pintype "input"))
      (node (ref "J13") (pin "2") (pinfunction "2_2") (pintype "passive"))
      (node (ref "J14") (pin "2") (pinfunction "2_2") (pintype "passive"))
      (node (ref "J17") (pin "2") (pinfunction "2_2") (pintype "passive"))
      (node (ref "L13") (pin "1") (pinfunction "1_1") (pintype "passive"))
      (node (ref "R103") (pin "2") (pinfunction "2_2") (pintype "passive"))
      (node (ref "R104") (pin "2") (pinfunction "2_2") (pintype "passive"))
      (node (ref "R105") (pin "2") (pinfunction "2_2") (pintype "passive"))
      (node (ref "R106") (pin "2") (pinfunction "2_2") (pintype "passive"))
      (node (ref "R120") (pin "1") (pinfunction "1_1") (pintype "passive"))
      (node (ref "R121") (pin "1") (pinfunction "1_1") (pintype "passive"))
      (node (ref "R127") (pin "1") (pinfunction "1_1") (pintype "passive"))
      (node (ref "R129") (pin "1") (pinfunction "1_1") (pintype "passive"))
      (node (ref "R133") (pin "1") (pinfunction "1_1") (pintype "passive"))
      (node (ref "R28") (pin "2") (pinfunction "2_2") (pintype "passive"))
      (node (ref "R65") (pin "1") (pinfunction "1_1") (pintype "passive"))
      (node (ref "R66") (pin "2") (pinfunction "2_2") (pintype "passive"))
      (node (ref "R74") (pin "2") (pinfunction "2_2") (pintype "passive"))
      (node (ref "R8") (pin "2") (pinfunction "2_2") (pintype "passive"))
      (node (ref "R81") (pin "2") (pinfunction "2_2") (pintype "passive"))
      (node (ref "R82") (pin "1") (pinfunction "1_1") (pintype "passive"))
      (node (ref "R87") (pin "1") (pinfunction "1_1") (pintype "passive"))
      (node (ref "R89") (pin "2") (pinfunction "2_2") (pintype "passive"))
      (node (ref "R9") (pin "2") (pinfunction "2_2") (pintype "passive"))
      (node (ref "R91") (pin "2") (pinfunction "2_2") (pintype "passive"))
    )
    (net (code "2") (name "+3.3V{slash}1") (class "Default")
      (node (ref "C1") (pin "1") (pinfunction "1_1") (pintype "passive"))
      (node (ref "C2") (pin "1") (pinfunction "1_1") (pintype "passive"))
      (node (ref "C28") (pin "1") (pinfunction "1_1") (pintype "passive"))
      (node (ref "C87") (pin "+") (pinfunction "+_+") (pintype "passive"))
      (node (ref "IC11") (pin "2") (pinfunction "A1_2") (pintype "input"))
      (node (ref "IC11") (pin "8") (pinfunction "VCC_8") (pintype "input"))
      (node (ref "IC2") (pin "37") (pinfunction "VCC_37") (pintype "input"))
      (node (ref "IC3") (pin "20") (pinfunction "VCC_20") (pintype "bidirectional"))
      (node (ref "IC4") (pin "20") (pinfunction "VCC_20") (pintype "bidirectional"))
      (node (ref "IC7") (pin "8") (pinfunction "VCC_8") (pintype "input"))
      (node (ref "Q2") (pin "3") (pinfunction "D_3") (pintype "passive"))
      (node (ref "Q2") (pin "P2") (pinfunction "D1_P2") (pintype "passive"))
      (node (ref "R18") (pin "1") (pinfunction "1_1") (pintype "passive"))
      (node (ref "R26") (pin "1") (pinfunction "1_1") (pintype "passive"))
      (node (ref "R27") (pin "1") (pinfunction "1_1") (pintype "passive"))
      (node (ref "R3") (pin "2") (pinfunction "2_2") (pintype "passive"))
      (node (ref "R4") (pin "2") (pinfunction "2_2") (pintype "passive"))
    )
    (net (code "3") (name "+3.3V{slash}2") (class "Default")
      (node (ref "C41") (pin "1") (pinfunction "1_1") (pintype "passive"))
      (node (ref "C86") (pin "+") (pinfunction "+_+") (pintype "passive"))
      (node (ref "IC12") (pin "8") (pinfunction "VCC_8") (pintype "input"))
      (node (ref "Q1") (pin "3") (pinfunction "D_3") (pintype "passive"))
      (node (ref "Q1") (pin "P2") (pinfunction "D1_P2") (pintype "passive"))
      (node (ref "R30") (pin "2") (pinfunction "2_2") (pintype "passive"))
      (node (ref "R34") (pin "1") (pinfunction "1_1") (pintype "passive"))
      (node (ref "R72") (pin "1") (pinfunction "1_1") (pintype "passive"))
      (node (ref "R73") (pin "2") (pinfunction "2_2") (pintype "passive"))
    )
    (net (code "4") (name "/+3.3V{slash}VPS") (class "Default")
      (node (ref "C27") (pin "1") (pinfunction "1_1") (pintype "passive"))
      (node (ref "IC9") (pin "3") (pinfunction "/WP_3") (pintype "input"))
      (node (ref "IC9") (pin "7") (pinfunction "/HOLD_7") (pintype "input"))
      (node (ref "IC9") (pin "8") (pinfunction "VCC_8") (pintype "input"))
      (node (ref "Q2") (pin "6") (pinfunction "D_6") (pintype "passive"))
      (node (ref "Q2") (pin "P1") (pinfunction "D1_P1") (pintype "passive"))
      (node (ref "R25") (pin "2") (pinfunction "2_2") (pintype "passive"))
    )
    (net (code "5") (name "/1.5V-CAM") (class "Default")
      (node (ref "L5") (pin "1") (pinfunction "1_1") (pintype "passive"))
      (node (ref "L6") (pin "2") (pinfunction "2_2") (pintype "passive"))
      (node (ref "R126") (pin "1") (pinfunction "1_1") (pintype "passive"))
    )
    (net (code "6") (name "/3.3V{slash}CAM") (class "Default")
      (node (ref "C16") (pin "+") (pinfunction "+_+") (pintype "passive"))
      (node (ref "C17") (pin "+") (pinfunction "+_+") (pintype "passive"))
      (node (ref "C18") (pin "1") (pinfunction "1_1") (pintype "passive"))
      (node (ref "IC5") (pin "1") (pinfunction "IN_1") (pintype "input"))
      (node (ref "IC5") (pin "3") (pinfunction "EN_3") (pintype "input"))
      (node (ref "L1") (pin "1") (pinfunction "1_1") (pintype "passive"))
      (node (ref "L2") (pin "2") (pinfunction "2_2") (pintype "passive"))
      (node (ref "L3") (pin "1") (pinfunction "1_1") (pintype "passive"))
      (node (ref "L4") (pin "2") (pinfunction "2_2") (pintype "passive"))
      (node (ref "Q1") (pin "6") (pinfunction "D_6") (pintype "passive"))
      (node (ref "Q1") (pin "P1") (pinfunction "D1_P1") (pintype "passive"))
      (node (ref "R11") (pin "2") (pinfunction "2_2") (pintype "passive"))
      (node (ref "R12") (pin "2") (pinfunction "2_2") (pintype "passive"))
      (node (ref "R13") (pin "2") (pinfunction "2_2") (pintype "passive"))
      (node (ref "R14") (pin "2") (pinfunction "2_2") (pintype "passive"))
      (node (ref "R15") (pin "2") (pinfunction "2_2") (pintype "passive"))
      (node (ref "R16") (pin "2") (pinfunction "2_2") (pintype "passive"))
    )
    (net (code "7") (name "/A+") (class "Default")
      (node (ref "J3") (pin "4") (pinfunction "4_4") (pintype "passive"))
      (node (ref "J4") (pin "4") (pinfunction "4_4") (pintype "passive"))
      (node (ref "L8") (pin "2") (pinfunction "2_2") (pintype "passive"))
    )
    (net (code "8") (name "/A++") (class "Default")
      (node (ref "IC12") (pin "6") (pinfunction "A_6") (pintype "bidirectional"))
      (node (ref "IC14") (pin "3") (pinfunction "3_3") (pintype "passive"))
      (node (ref "R109") (pin "2") (pinfunction "2_2") (pintype "passive"))
      (node (ref "R32") (pin "2") (pinfunction "2_2") (pintype "passive"))
      (node (ref "R34") (pin "2") (pinfunction "2_2") (pintype "passive"))
    )
    (net (code "9") (name "/A0") (class "Default")
      (node (ref "IC2") (pin "20") (pinfunction "A5_20") (pintype "input"))
      (node (ref "IC3") (pin "12") (pinfunction "Q7_12") (pintype "tri_state"))
    )
    (net (code "10") (name "/A1") (class "Default")
      (node (ref "IC2") (pin "21") (pinfunction "A4_21") (pintype "input"))
      (node (ref "IC3") (pin "13") (pinfunction "Q6_13") (pintype "tri_state"))
    )
    (net (code "11") (name "/A2") (class "Default")
      (node (ref "IC2") (pin "22") (pinfunction "A3_22") (pintype "input"))
      (node (ref "IC3") (pin "14") (pinfunction "Q5_14") (pintype "tri_state"))
    )
    (net (code "12") (name "/A3") (class "Default")
      (node (ref "IC2") (pin "23") (pinfunction "A2_23") (pintype "input"))
      (node (ref "IC3") (pin "15") (pinfunction "Q4_15") (pintype "tri_state"))
    )
    (net (code "13") (name "/A4") (class "Default")
      (node (ref "IC2") (pin "24") (pinfunction "A1_24") (pintype "input"))
      (node (ref "IC3") (pin "16") (pinfunction "Q3_16") (pintype "tri_state"))
    )
    (net (code "14") (name "/A5") (class "Default")
      (node (ref "IC2") (pin "25") (pinfunction "A0_25") (pintype "input"))
      (node (ref "IC3") (pin "17") (pinfunction "Q2_17") (pintype "tri_state"))
    )
    (net (code "15") (name "/A6") (class "Default")
      (node (ref "IC2") (pin "45") (pinfunction "A-1/D15_45") (pintype "tri_state"))
      (node (ref "IC3") (pin "18") (pinfunction "Q1_18") (pintype "tri_state"))
    )
    (net (code "16") (name "/A7") (class "Default")
      (node (ref "IC2") (pin "48") (pinfunction "A16_48") (pintype "input"))
      (node (ref "IC3") (pin "19") (pinfunction "Q0_19") (pintype "tri_state"))
    )
    (net (code "17") (name "/A8") (class "Default")
      (node (ref "IC2") (pin "19") (pinfunction "A6_19") (pintype "input"))
      (node (ref "IC4") (pin "19") (pinfunction "Q0_19") (pintype "tri_state"))
    )
    (net (code "18") (name "/A9") (class "Default")
      (node (ref "IC2") (pin "18") (pinfunction "A7_18") (pintype "input"))
      (node (ref "IC4") (pin "18") (pinfunction "Q1_18") (pintype "tri_state"))
    )
    (net (code "19") (name "/A10") (class "Default")
      (node (ref "IC2") (pin "17") (pinfunction "A17_17") (pintype "input"))
      (node (ref "IC4") (pin "17") (pinfunction "Q2_17") (pintype "tri_state"))
    )
    (net (code "20") (name "/A11") (class "Default")
      (node (ref "IC2") (pin "16") (pinfunction "A18_16") (pintype "input"))
      (node (ref "IC4") (pin "16") (pinfunction "Q3_16") (pintype "tri_state"))
    )
    (net (code "21") (name "/A12") (class "Default")
      (node (ref "IC2") (pin "9") (pinfunction "A19_9") (pintype "input"))
      (node (ref "IC4") (pin "15") (pinfunction "Q4_15") (pintype "tri_state"))
    )
    (net (code "22") (name "/A13") (class "Default")
      (node (ref "IC2") (pin "8") (pinfunction "A8_8") (pintype "input"))
      (node (ref "IC4") (pin "14") (pinfunction "Q5_14") (pintype "tri_state"))
    )
    (net (code "23") (name "/A14") (class "Default")
      (node (ref "IC2") (pin "7") (pinfunction "A9_7") (pintype "input"))
      (node (ref "IC4") (pin "13") (pinfunction "Q6_13") (pintype "tri_state"))
    )
    (net (code "24") (name "/A15") (class "Default")
      (node (ref "IC2") (pin "6") (pinfunction "A10_6") (pintype "input"))
      (node (ref "IC4") (pin "12") (pinfunction "Q7_12") (pintype "tri_state"))
    )
    (net (code "25") (name "/A16") (class "Default")
      (node (ref "IC1") (pin "32") (pinfunction "AN8/RPB8/CTED10/RB8_32") (pintype "bidirectional"))
      (node (ref "IC2") (pin "5") (pinfunction "A11_5") (pintype "input"))
    )
    (net (code "26") (name "/A17") (class "Default")
      (node (ref "IC1") (pin "33") (pinfunction "AN9/RPB9/CTED4/RB9_33") (pintype "bidirectional"))
      (node (ref "IC2") (pin "4") (pinfunction "A12_4") (pintype "input"))
    )
    (net (code "27") (name "/A18") (class "Default")
      (node (ref "IC1") (pin "34") (pinfunction "CVREFOUT/AN10/RPB10/PMA13/CTED11/RB10_34") (pintype "bidirectional"))
      (node (ref "IC2") (pin "3") (pinfunction "A13_3") (pintype "input"))
    )
    (net (code "28") (name "/A19") (class "Default")
      (node (ref "IC1") (pin "35") (pinfunction "AN11/PMA12/RB11_35") (pintype "bidirectional"))
      (node (ref "IC2") (pin "2") (pinfunction "A14_2") (pintype "input"))
    )
    (net (code "29") (name "/A20") (class "Default")
      (node (ref "IC1") (pin "41") (pinfunction "AN12/PMA11/RB12_41") (pintype "bidirectional"))
      (node (ref "IC2") (pin "1") (pinfunction "A15_1") (pintype "input"))
    )
    (net (code "30") (name "/AGND1") (class "Default")
      (node (ref "C3") (pin "1") (pinfunction "1_1") (pintype "passive"))
      (node (ref "C9") (pin "-") (pinfunction "-_-") (pintype "passive"))
      (node (ref "J1") (pin "2") (pinfunction "2_2") (pintype "passive"))
      (node (ref "R6") (pin "1") (pinfunction "1_1") (pintype "passive"))
    )
    (net (code "31") (name "/AGND2") (class "Default")
      (node (ref "C10") (pin "-") (pinfunction "-_-") (pintype "passive"))
      (node (ref "C4") (pin "1") (pinfunction "1_1") (pintype "passive"))
      (node (ref "J2") (pin "2") (pinfunction "2_2") (pintype "passive"))
      (node (ref "R7") (pin "1") (pinfunction "1_1") (pintype "passive"))
    )
    (net (code "32") (name "/AVDD1") (class "Default")
      (node (ref "C3") (pin "2") (pinfunction "2_2") (pintype "passive"))
      (node (ref "C9") (pin "+") (pinfunction "+_+") (pintype "passive"))
      (node (ref "J1") (pin "4") (pinfunction "4_4") (pintype "passive"))
      (node (ref "L1") (pin "2") (pinfunction "2_2") (pintype "passive"))
    )
    (net (code "33") (name "/AVDD2") (class "Default")
      (node (ref "C10") (pin "+") (pinfunction "+_+") (pintype "passive"))
      (node (ref "C4") (pin "2") (pinfunction "2_2") (pintype "passive"))
      (node (ref "J2") (pin "4") (pinfunction "4_4") (pintype "passive"))
      (node (ref "L2") (pin "1") (pinfunction "1_1") (pintype "passive"))
    )
    (net (code "34") (name "/B-") (class "Default")
      (node (ref "J3") (pin "5") (pinfunction "5_5") (pintype "passive"))
      (node (ref "J4") (pin "5") (pinfunction "5_5") (pintype "passive"))
      (node (ref "L7") (pin "2") (pinfunction "2_2") (pintype "passive"))
    )
    (net (code "35") (name "/B--") (class "Default")
      (node (ref "IC12") (pin "7") (pinfunction "B_7") (pintype "bidirectional"))
      (node (ref "IC14") (pin "2") (pinfunction "2_2") (pintype "passive"))
      (node (ref "R108") (pin "2") (pinfunction "2_2") (pintype "passive"))
      (node (ref "R31") (pin "1") (pinfunction "1_1") (pintype "passive"))
      (node (ref "R32") (pin "1") (pinfunction "1_1") (pintype "passive"))
    )
    (net (code "36") (name "/BT-RTS") (class "Default")
      (node (ref "IC1") (pin "83") (pinfunction "PMD14/RD6_83") (pintype "bidirectional"))
      (node (ref "J13") (pin "7") (pinfunction "7_7") (pintype "passive"))
      (node (ref "J14") (pin "7") (pinfunction "7_7") (pintype "passive"))
      (node (ref "O32") (pin "P$1") (pinfunction "TP_P$1") (pintype "passive"))
      (node (ref "T44") (pin "P$1") (pinfunction "TP_P$1") (pintype "passive"))
    )
    (net (code "37") (name "/BT-RX") (class "Default")
      (node (ref "IC1") (pin "73") (pinfunction "SOSCI/RPC13/RC13_73") (pintype "bidirectional"))
      (node (ref "J13") (pin "3") (pinfunction "3_3") (pintype "passive"))
      (node (ref "J14") (pin "3") (pinfunction "3_3") (pintype "passive"))
      (node (ref "O37") (pin "P$1") (pinfunction "TP_P$1") (pintype "passive"))
      (node (ref "T40") (pin "P$1") (pinfunction "TP_P$1") (pintype "passive"))
    )
    (net (code "38") (name "/BT-TX") (class "Default")
      (node (ref "IC1") (pin "74") (pinfunction "SOSCO/RPC14/T1CK/RC14_74") (pintype "bidirectional"))
      (node (ref "J13") (pin "4") (pinfunction "4_4") (pintype "passive"))
      (node (ref "J14") (pin "4") (pinfunction "4_4") (pintype "passive"))
      (node (ref "O36") (pin "P$1") (pinfunction "TP_P$1") (pintype "passive"))
      (node (ref "T41") (pin "P$1") (pinfunction "TP_P$1") (pintype "passive"))
    )
    (net (code "39") (name "/CON-LED") (class "Default")
      (node (ref "IC1") (pin "78") (pinfunction "AN26/RPD3/RD3_78") (pintype "bidirectional"))
      (node (ref "J13") (pin "6") (pinfunction "6_6") (pintype "passive"))
      (node (ref "J14") (pin "6") (pinfunction "6_6") (pintype "passive"))
      (node (ref "O33") (pin "P$1") (pinfunction "TP_P$1") (pintype "passive"))
      (node (ref "T43") (pin "P$1") (pinfunction "TP_P$1") (pintype "passive"))
    )
    (net (code "40") (name "/CS-SRAM") (class "Default")
      (node (ref "IC1") (pin "38") (pinfunction "TCK/CTED2/RA1_38") (pintype "bidirectional"))
      (node (ref "IC2") (pin "12") (pinfunction "CS2_12") (pintype "input"))
      (node (ref "O17") (pin "P$1") (pinfunction "TP_P$1") (pintype "passive"))
      (node (ref "R5") (pin "2") (pinfunction "2_2") (pintype "passive"))
      (node (ref "T28") (pin "P$1") (pinfunction "TP_P$1") (pintype "passive"))
    )
    (net (code "41") (name "/CURR-SENSE") (class "Default")
      (node (ref "C66") (pin "1") (pinfunction "1_1") (pintype "passive"))
      (node (ref "IC1") (pin "14") (pinfunction "AN19/C2INC/RPG9/PMA2/RG9_14") (pintype "bidirectional"))
      (node (ref "O8") (pin "P$1") (pinfunction "TP_P$1") (pintype "passive"))
      (node (ref "R102") (pin "2") (pinfunction "2_2") (pintype "passive"))
      (node (ref "T39") (pin "P$1") (pinfunction "TP_P$1") (pintype "passive"))
    )
    (net (code "42") (name "/D0") (class "Default")
      (node (ref "IC1") (pin "93") (pinfunction "PMD0/RE0_93") (pintype "bidirectional"))
      (node (ref "IC2") (pin "29") (pinfunction "D0_29") (pintype "tri_state"))
      (node (ref "IC3") (pin "9") (pinfunction "D7_9") (pintype "input"))
      (node (ref "IC4") (pin "2") (pinfunction "D0_2") (pintype "input"))
    )
    (net (code "43") (name "/D1") (class "Default")
      (node (ref "IC1") (pin "94") (pinfunction "PMD1/RE1_94") (pintype "bidirectional"))
      (node (ref "IC2") (pin "31") (pinfunction "D1_31") (pintype "tri_state"))
      (node (ref "IC3") (pin "8") (pinfunction "D6_8") (pintype "input"))
      (node (ref "IC4") (pin "3") (pinfunction "D1_3") (pintype "input"))
    )
    (net (code "44") (name "/D2") (class "Default")
      (node (ref "IC1") (pin "98") (pinfunction "AN20/PMD2/RE2_98") (pintype "bidirectional"))
      (node (ref "IC2") (pin "33") (pinfunction "D2_33") (pintype "tri_state"))
      (node (ref "IC3") (pin "7") (pinfunction "D5_7") (pintype "input"))
      (node (ref "IC4") (pin "4") (pinfunction "D2_4") (pintype "input"))
    )
    (net (code "45") (name "/D3") (class "Default")
      (node (ref "IC1") (pin "99") (pinfunction "RPE3/PMD3/RE3_99") (pintype "bidirectional"))
      (node (ref "IC2") (pin "35") (pinfunction "D3_35") (pintype "tri_state"))
      (node (ref "IC3") (pin "6") (pinfunction "D4_6") (pintype "input"))
      (node (ref "IC4") (pin "5") (pinfunction "D3_5") (pintype "input"))
    )
    (net (code "46") (name "/D4") (class "Default")
      (node (ref "IC1") (pin "100") (pinfunction "AN21/PMD4/RE4_100") (pintype "bidirectional"))
      (node (ref "IC2") (pin "38") (pinfunction "D4_38") (pintype "tri_state"))
      (node (ref "IC3") (pin "5") (pinfunction "D3_5") (pintype "input"))
      (node (ref "IC4") (pin "6") (pinfunction "D4_6") (pintype "input"))
    )
    (net (code "47") (name "/D5") (class "Default")
      (node (ref "IC1") (pin "3") (pinfunction "AN22/RPE5/PMD5/RE5_3") (pintype "bidirectional"))
      (node (ref "IC2") (pin "40") (pinfunction "D5_40") (pintype "tri_state"))
      (node (ref "IC3") (pin "4") (pinfunction "D2_4") (pintype "input"))
      (node (ref "IC4") (pin "7") (pinfunction "D5_7") (pintype "input"))
    )
    (net (code "48") (name "/D6") (class "Default")
      (node (ref "IC1") (pin "4") (pinfunction "AN23/PMD6/RE6_4") (pintype "bidirectional"))
      (node (ref "IC2") (pin "42") (pinfunction "D6_42") (pintype "tri_state"))
      (node (ref "IC3") (pin "3") (pinfunction "D1_3") (pintype "input"))
      (node (ref "IC4") (pin "8") (pinfunction "D6_8") (pintype "input"))
    )
    (net (code "49") (name "/D7") (class "Default")
      (node (ref "IC1") (pin "5") (pinfunction "AN27/PMD7/RE7_5") (pintype "bidirectional"))
      (node (ref "IC2") (pin "44") (pinfunction "D7_44") (pintype "tri_state"))
      (node (ref "IC3") (pin "2") (pinfunction "D0_2") (pintype "input"))
      (node (ref "IC4") (pin "9") (pinfunction "D7_9") (pintype "input"))
    )
    (net (code "50") (name "/DOOR-IN-EN") (class "Default")
      (node (ref "IC1") (pin "51") (pinfunction "RPF3/USBID/RF3_51") (pintype "bidirectional"))
      (node (ref "O43") (pin "P$1") (pinfunction "TP_P$1") (pintype "passive"))
      (node (ref "Q12") (pin "2") (pinfunction "G_2") (pintype "passive"))
      (node (ref "Q13") (pin "2") (pinfunction "G_2") (pintype "passive"))
      (node (ref "R76") (pin "1") (pinfunction "1_1") (pintype "passive"))
      (node (ref "R88") (pin "1") (pinfunction "1_1") (pintype "passive"))
      (node (ref "T8") (pin "P$1") (pinfunction "TP_P$1") (pintype "passive"))
    )
    (net (code "51") (name "/DOOR1IN") (class "Default")
      (node (ref "IC1") (pin "50") (pinfunction "RPF5/PMA8/RF5_50") (pintype "bidirectional"))
      (node (ref "O21") (pin "P$1") (pinfunction "TP_P$1") (pintype "passive"))
      (node (ref "Q13") (pin "3") (pinfunction "D_3") (pintype "passive"))
      (node (ref "R74") (pin "1") (pinfunction "1_1") (pintype "passive"))
      (node (ref "T12") (pin "P$1") (pinfunction "TP_P$1") (pintype "passive"))
    )
    (net (code "52") (name "/DOOR2IN") (class "Default")
      (node (ref "IC1") (pin "77") (pinfunction "AN25/RPD2/RD2_77") (pintype "bidirectional"))
      (node (ref "O34") (pin "P$1") (pinfunction "TP_P$1") (pintype "passive"))
      (node (ref "Q12") (pin "3") (pinfunction "D_3") (pintype "passive"))
      (node (ref "R89") (pin "1") (pinfunction "1_1") (pintype "passive"))
      (node (ref "T11") (pin "P$1") (pinfunction "TP_P$1") (pintype "passive"))
    )
    (net (code "53") (name "/DOVDD1") (class "Default")
      (node (ref "C11") (pin "+") (pinfunction "+_+") (pintype "passive"))
      (node (ref "C5") (pin "1") (pinfunction "1_1") (pintype "passive"))
      (node (ref "J1") (pin "11") (pinfunction "11_11") (pintype "passive"))
      (node (ref "L3") (pin "2") (pinfunction "2_2") (pintype "passive"))
    )
    (net (code "54") (name "/DOVDD2") (class "Default")
      (node (ref "C12") (pin "+") (pinfunction "+_+") (pintype "passive"))
      (node (ref "C6") (pin "1") (pinfunction "1_1") (pintype "passive"))
      (node (ref "J2") (pin "11") (pinfunction "11_11") (pintype "passive"))
      (node (ref "L4") (pin "1") (pinfunction "1_1") (pintype "passive"))
    )
    (net (code "55") (name "/DVDD1") (class "Default")
      (node (ref "C13") (pin "+") (pinfunction "+_+") (pintype "passive"))
      (node (ref "C7") (pin "2") (pinfunction "2_2") (pintype "passive"))
      (node (ref "J1") (pin "10") (pinfunction "10_10") (pintype "passive"))
      (node (ref "L5") (pin "2") (pinfunction "2_2") (pintype "passive"))
    )
    (net (code "56") (name "/DVDD2") (class "Default")
      (node (ref "C14") (pin "+") (pinfunction "+_+") (pintype "passive"))
      (node (ref "C8") (pin "2") (pinfunction "2_2") (pintype "passive"))
      (node (ref "J2") (pin "10") (pinfunction "10_10") (pintype "passive"))
      (node (ref "L6") (pin "1") (pinfunction "1_1") (pintype "passive"))
    )
    (net (code "57") (name "/D_N") (class "Default")
      (node (ref "IC1") (pin "56") (pinfunction "D-/RG3_56") (pintype "bidirectional"))
      (node (ref "IC15") (pin "2") (pinfunction "2_2") (pintype "passive"))
      (node (ref "J12") (pin "2_D-") (pinfunction "D-_2_D-") (pintype "bidirectional"))
    )
    (net (code "58") (name "/D_P") (class "Default")
      (node (ref "IC1") (pin "57") (pinfunction "D+/RG2_57") (pintype "bidirectional"))
      (node (ref "IC15") (pin "3") (pinfunction "3_3") (pintype "passive"))
      (node (ref "J12") (pin "3_D+") (pinfunction "D+_3_D+") (pintype "bidirectional"))
    )
    (net (code "59") (name "/HREF") (class "Default")
      (node (ref "IC1") (pin "6") (pinfunction "RPC1/RC1_6") (pintype "bidirectional"))
      (node (ref "J1") (pin "9") (pinfunction "9_9") (pintype "passive"))
      (node (ref "J2") (pin "9") (pinfunction "9_9") (pintype "passive"))
      (node (ref "O2") (pin "P$1") (pinfunction "TP_P$1") (pintype "passive"))
      (node (ref "T18") (pin "P$1") (pinfunction "TP_P$1") (pintype "passive"))
    )
    (net (code "60") (name "/INFRA1PWM") (class "Default")
      (node (ref "IC1") (pin "90") (pinfunction "RPG0/PMD8/RG0_90") (pintype "bidirectional"))
      (node (ref "O27") (pin "P$1") (pinfunction "TP_P$1") (pintype "passive"))
      (node (ref "R113") (pin "2") (pinfunction "2_2") (pintype "passive"))
      (node (ref "T34") (pin "P$1") (pinfunction "TP_P$1") (pintype "passive"))
    )
    (net (code "61") (name "/INFRA2PWM") (class "Default")
      (node (ref "IC1") (pin "40") (pinfunction "RPF12/RF12_40") (pintype "bidirectional"))
      (node (ref "O19") (pin "P$1") (pinfunction "TP_P$1") (pintype "passive"))
      (node (ref "R119") (pin "2") (pinfunction "2_2") (pintype "passive"))
      (node (ref "T35") (pin "P$1") (pinfunction "TP_P$1") (pintype "passive"))
    )
    (net (code "62") (name "/L1CTL") (class "Default")
      (node (ref "C79") (pin "1") (pinfunction "1_1") (pintype "passive"))
      (node (ref "J5") (pin "3") (pinfunction "3_3") (pintype "bidirectional"))
      (node (ref "Q6") (pin "4") (pinfunction "D_4") (pintype "passive"))
    )
    (net (code "63") (name "/L1PWR") (class "Default")
      (node (ref "C80") (pin "1") (pinfunction "1_1") (pintype "passive"))
      (node (ref "J5") (pin "2") (pinfunction "2_2") (pintype "bidirectional"))
      (node (ref "Q6") (pin "6") (pinfunction "D_6") (pintype "passive"))
    )
    (net (code "64") (name "/L2CTL") (class "Default")
      (node (ref "C78") (pin "1") (pinfunction "1_1") (pintype "passive"))
      (node (ref "J6") (pin "3") (pinfunction "3_3") (pintype "bidirectional"))
      (node (ref "Q8") (pin "6") (pinfunction "D_6") (pintype "passive"))
    )
    (net (code "65") (name "/L2PWR") (class "Default")
      (node (ref "C77") (pin "1") (pinfunction "1_1") (pintype "passive"))
      (node (ref "J6") (pin "2") (pinfunction "2_2") (pintype "bidirectional"))
      (node (ref "Q8") (pin "4") (pinfunction "D_4") (pintype "passive"))
    )
    (net (code "66") (name "/LAN-CTL") (class "Default")
      (node (ref "IC1") (pin "84") (pinfunction "PMD15/RD7_84") (pintype "bidirectional"))
      (node (ref "IC12") (pin "2") (pinfunction "/RE_2") (pintype "input"))
      (node (ref "IC12") (pin "3") (pinfunction "DE_3") (pintype "input"))
      (node (ref "O31") (pin "P$1") (pinfunction "TP_P$1") (pintype "passive"))
      (node (ref "R71") (pin "1") (pinfunction "1_1") (pintype "passive"))
      (node (ref "T15") (pin "P$1") (pinfunction "TP_P$1") (pintype "passive"))
    )
    (net (code "67") (name "/LAN-RX") (class "Default")
      (node (ref "IC1") (pin "88") (pinfunction "RPF1/PMD10/RF1_88") (pintype "bidirectional"))
      (node (ref "IC12") (pin "1") (pinfunction "R_1") (pintype "output"))
      (node (ref "O29") (pin "P$1") (pinfunction "TP_P$1") (pintype "passive"))
      (node (ref "R72") (pin "2") (pinfunction "2_2") (pintype "passive"))
      (node (ref "T13") (pin "P$1") (pinfunction "TP_P$1") (pintype "passive"))
    )
    (net (code "68") (name "/LAN-TX") (class "Default")
      (node (ref "IC1") (pin "87") (pinfunction "RPF0/PMD11/RF0_87") (pintype "bidirectional"))
      (node (ref "IC12") (pin "4") (pinfunction "D_4") (pintype "input"))
      (node (ref "O30") (pin "P$1") (pinfunction "TP_P$1") (pintype "passive"))
      (node (ref "R73") (pin "1") (pinfunction "1_1") (pintype "passive"))
      (node (ref "T14") (pin "P$1") (pinfunction "TP_P$1") (pintype "passive"))
    )
    (net (code "69") (name "/LATCH_SW_1") (class "Default")
      (node (ref "IC1") (pin "9") (pinfunction "RPC4/CTED7/RC4_9") (pintype "bidirectional"))
      (node (ref "J11") (pin "1") (pinfunction "1_1") (pintype "passive"))
      (node (ref "R120") (pin "2") (pinfunction "2_2") (pintype "passive"))
    )
    (net (code "70") (name "/LATCH_SW_2") (class "Default")
      (node (ref "IC1") (pin "18") (pinfunction "RPE8/RE8_18") (pintype "bidirectional"))
      (node (ref "J15") (pin "1") (pinfunction "1_1") (pintype "passive"))
      (node (ref "R127") (pin "2") (pinfunction "2_2") (pintype "passive"))
    )
    (net (code "71") (name "/LATCH_SW_3") (class "Default")
      (node (ref "IC1") (pin "19") (pinfunction "RPE9/RE9_19") (pintype "bidirectional"))
      (node (ref "J16") (pin "1") (pinfunction "1_1") (pintype "passive"))
      (node (ref "R121") (pin "2") (pinfunction "2_2") (pintype "passive"))
    )
    (net (code "72") (name "/LATCH_SW_4") (class "Default")
      (node (ref "IC1") (pin "42") (pinfunction "AN13/RB13_42") (pintype "bidirectional"))
      (node (ref "J18") (pin "1") (pinfunction "1_1") (pintype "passive"))
      (node (ref "R133") (pin "2") (pinfunction "2_2") (pintype "passive"))
    )
    (net (code "73") (name "/LED-PIC") (class "Default")
      (node (ref "IC1") (pin "1") (pinfunction "RG15_1") (pintype "bidirectional"))
      (node (ref "O1") (pin "P$1") (pinfunction "TP_P$1") (pintype "passive"))
      (node (ref "R29") (pin "1") (pinfunction "1_1") (pintype "passive"))
      (node (ref "T36") (pin "P$1") (pinfunction "TP_P$1") (pintype "passive"))
      (node (ref "TP4") (pin "P$1") (pinfunction "TP_P$1") (pintype "passive"))
    )
    (net (code "74") (name "/LEH-SRAM") (class "Default")
      (node (ref "IC1") (pin "43") (pinfunction "AN14/RPB14/PMA1/CTED5/RB14_43") (pintype "bidirectional"))
      (node (ref "IC4") (pin "11") (pinfunction "LE_11") (pintype "input"))
      (node (ref "R2") (pin "2") (pinfunction "2_2") (pintype "passive"))
    )
    (net (code "75") (name "/LEL-SRAM") (class "Default")
      (node (ref "IC1") (pin "44") (pinfunction "AN15/RPB15/PMA0/CTED6//RB15_44") (pintype "bidirectional"))
      (node (ref "IC3") (pin "11") (pinfunction "LE_11") (pintype "input"))
      (node (ref "R1") (pin "2") (pinfunction "2_2") (pintype "passive"))
    )
    (net (code "76") (name "/LOCK-IN-EN") (class "Default")
      (node (ref "IC1") (pin "60") (pinfunction "TDI/CTED9/RA4_60") (pintype "bidirectional"))
      (node (ref "O40") (pin "P$1") (pinfunction "TP_P$1") (pintype "passive"))
      (node (ref "Q10") (pin "2") (pinfunction "G_2") (pintype "passive"))
      (node (ref "Q11") (pin "2") (pinfunction "G_2") (pintype "passive"))
      (node (ref "R67") (pin "1") (pinfunction "1_1") (pintype "passive"))
      (node (ref "R83") (pin "1") (pinfunction "1_1") (pintype "passive"))
      (node (ref "T6") (pin "P$1") (pinfunction "TP_P$1") (pintype "passive"))
    )
    (net (code "77") (name "/LOCK1CTL") (class "Default")
      (node (ref "IC1") (pin "61") (pinfunction "TDO/RA5_61") (pintype "bidirectional"))
      (node (ref "O39") (pin "P$1") (pinfunction "TP_P$1") (pintype "passive"))
      (node (ref "Q7") (pin "5") (pinfunction "G_5") (pintype "passive"))
      (node (ref "R54") (pin "1") (pinfunction "1_1") (pintype "passive"))
      (node (ref "T1") (pin "P$1") (pinfunction "TP_P$1") (pintype "passive"))
    )
    (net (code "78") (name "/LOCK1IN") (class "Default")
      (node (ref "IC1") (pin "49") (pinfunction "RPF4/PMA9/RF4_49") (pintype "bidirectional"))
      (node (ref "O20") (pin "P$1") (pinfunction "TP_P$1") (pintype "passive"))
      (node (ref "Q11") (pin "3") (pinfunction "D_3") (pintype "passive"))
      (node (ref "R66") (pin "1") (pinfunction "1_1") (pintype "passive"))
      (node (ref "T10") (pin "P$1") (pinfunction "TP_P$1") (pintype "passive"))
    )
    (net (code "79") (name "/LOCK2CTL") (class "Default")
      (node (ref "IC1") (pin "91") (pinfunction "TRCLK/RA6_91") (pintype "bidirectional"))
      (node (ref "O26") (pin "P$1") (pinfunction "TP_P$1") (pintype "passive"))
      (node (ref "Q9") (pin "2") (pinfunction "G_2") (pintype "passive"))
      (node (ref "R58") (pin "1") (pinfunction "1_1") (pintype "passive"))
      (node (ref "T2") (pin "P$1") (pinfunction "TP_P$1") (pintype "passive"))
    )
    (net (code "80") (name "/LOCK2IN") (class "Default")
      (node (ref "IC1") (pin "89") (pinfunction "RPG1/PMD9/RG1_89") (pintype "bidirectional"))
      (node (ref "O28") (pin "P$1") (pinfunction "TP_P$1") (pintype "passive"))
      (node (ref "Q10") (pin "3") (pinfunction "D_3") (pintype "passive"))
      (node (ref "R81") (pin "1") (pinfunction "1_1") (pintype "passive"))
      (node (ref "T9") (pin "P$1") (pinfunction "TP_P$1") (pintype "passive"))
    )
    (net (code "81") (name "/LOCK12PWR") (class "Default")
      (node (ref "IC1") (pin "92") (pinfunction "TRD3/CTED8/RA7_92") (pintype "bidirectional"))
      (node (ref "O25") (pin "P$1") (pinfunction "TP_P$1") (pintype "passive"))
      (node (ref "Q7") (pin "2") (pinfunction "G_2") (pintype "passive"))
      (node (ref "Q9") (pin "5") (pinfunction "G_5") (pintype "passive"))
      (node (ref "R52") (pin "1") (pinfunction "1_1") (pintype "passive"))
      (node (ref "R60") (pin "1") (pinfunction "1_1") (pintype "passive"))
      (node (ref "T4") (pin "P$1") (pinfunction "TP_P$1") (pintype "passive"))
    )
    (net (code "82") (name "/OE-SRAM") (class "Default")
      (node (ref "IC1") (pin "82") (pinfunction "RPD5/PMRD/RD5_82") (pintype "bidirectional"))
      (node (ref "IC2") (pin "28") (pinfunction "~{OE}_28") (pintype "input"))
      (node (ref "R3") (pin "1") (pinfunction "1_1") (pintype "passive"))
    )
    (net (code "83") (name "/PCLK") (class "Default")
      (node (ref "IC1") (pin "76") (pinfunction "AN24/RPD1/RD1_76") (pintype "bidirectional"))
      (node (ref "J1") (pin "17") (pinfunction "17_17") (pintype "passive"))
      (node (ref "J2") (pin "17") (pinfunction "17_17") (pintype "passive"))
      (node (ref "O35") (pin "P$1") (pinfunction "TP_P$1") (pintype "passive"))
      (node (ref "T17") (pin "P$1") (pinfunction "TP_P$1") (pintype "passive"))
    )
    (net (code "84") (name "/PGC") (class "Default")
      (node (ref "IC1") (pin "24") (pinfunction "PGEC1/AN1/RPB1/CTED12/RB1_24") (pintype "bidirectional"))
      (node (ref "J17") (pin "5") (pinfunction "5_5") (pintype "passive"))
      (node (ref "R131") (pin "1") (pinfunction "1_1") (pintype "passive"))
    )
    (net (code "85") (name "/PGD") (class "Default")
      (node (ref "IC1") (pin "25") (pinfunction "PGED1/AN0/RPB0/RB0_25") (pintype "bidirectional"))
      (node (ref "J17") (pin "4") (pinfunction "4_4") (pintype "passive"))
      (node (ref "R130") (pin "2") (pinfunction "2_2") (pintype "passive"))
    )
    (net (code "86") (name "/POWER-GOOD") (class "Default")
      (node (ref "IC6") (pin "4") (pinfunction "OUT_4") (pintype "output"))
      (node (ref "R130") (pin "1") (pinfunction "1_1") (pintype "passive"))
      (node (ref "T45") (pin "P$1") (pinfunction "TP_P$1") (pintype "passive"))
      (node (ref "TP2") (pin "P$1") (pinfunction "TP_P$1") (pintype "passive"))
    )
    (net (code "87") (name "/PWDN-CAM1") (class "Default")
      (node (ref "IC1") (pin "97") (pinfunction "TRD0/RG13_97") (pintype "bidirectional"))
      (node (ref "J1") (pin "8") (pinfunction "8_8") (pintype "passive"))
      (node (ref "O22") (pin "P$1") (pinfunction "TP_P$1") (pintype "passive"))
      (node (ref "R12") (pin "1") (pinfunction "1_1") (pintype "passive"))
      (node (ref "T20") (pin "P$1") (pinfunction "TP_P$1") (pintype "passive"))
    )
    (net (code "88") (name "/PWDN-CAM2") (class "Default")
      (node (ref "IC1") (pin "39") (pinfunction "RPF13/RF13_39") (pintype "bidirectional"))
      (node (ref "J2") (pin "8") (pinfunction "8_8") (pintype "passive"))
      (node (ref "O18") (pin "P$1") (pinfunction "TP_P$1") (pintype "passive"))
      (node (ref "R16") (pin "1") (pinfunction "1_1") (pintype "passive"))
      (node (ref "T21") (pin "P$1") (pinfunction "TP_P$1") (pintype "passive"))
    )
    (net (code "89") (name "/REF-EN") (class "Default")
      (node (ref "IC1") (pin "28") (pinfunction "VREF-/CVREF-/PMA7/RA9_28") (pintype "bidirectional"))
      (node (ref "R93") (pin "1") (pinfunction "1_1") (pintype "passive"))
    )
    (net (code "90") (name "/REF2,5V") (class "Default")
      (node (ref "C57") (pin "1") (pinfunction "1_1") (pintype "passive"))
      (node (ref "IC1") (pin "29") (pinfunction "VREF+/CVREF+/PMA6/RA10_29") (pintype "bidirectional"))
      (node (ref "IC13") (pin "2") (pinfunction "VOUT_2") (pintype "bidirectional"))
    )
    (net (code "91") (name "/RESET-CAM1") (class "Default")
      (node (ref "C76") (pin "1") (pinfunction "1_1") (pintype "passive"))
      (node (ref "J1") (pin "6") (pinfunction "6_6") (pintype "passive"))
      (node (ref "R11") (pin "1") (pinfunction "1_1") (pintype "passive"))
    )
    (net (code "92") (name "/RESET-CAM2") (class "Default")
      (node (ref "C75") (pin "1") (pinfunction "1_1") (pintype "passive"))
      (node (ref "J2") (pin "6") (pinfunction "6_6") (pintype "passive"))
      (node (ref "R15") (pin "1") (pinfunction "1_1") (pintype "passive"))
    )
    (net (code "93") (name "/SCL1-EEPROM") (class "Default")
      (node (ref "IC1") (pin "66") (pinfunction "SCL1/RPA14/RA14_66") (pintype "bidirectional"))
      (node (ref "IC11") (pin "6") (pinfunction "SCL_6") (pintype "input"))
      (node (ref "IC7") (pin "6") (pinfunction "SCL_6") (pintype "input"))
      (node (ref "R26") (pin "2") (pinfunction "2_2") (pintype "passive"))
    )
    (net (code "94") (name "/SCLK2-SPI") (class "Default")
      (node (ref "IC1") (pin "10") (pinfunction "AN16/C1IND/RPG6/SCK2/PMA5/RG6_10") (pintype "bidirectional"))
      (node (ref "IC9") (pin "6") (pinfunction "C_6") (pintype "input"))
    )
    (net (code "95") (name "/SDA1-EEPROM") (class "Default")
      (node (ref "IC1") (pin "67") (pinfunction "SDA1/RPA15/RA15_67") (pintype "bidirectional"))
      (node (ref "IC11") (pin "5") (pinfunction "SDA_5") (pintype "bidirectional"))
      (node (ref "IC7") (pin "5") (pinfunction "SDA_5") (pintype "bidirectional"))
      (node (ref "R27") (pin "2") (pinfunction "2_2") (pintype "passive"))
    )
    (net (code "96") (name "/SDI2-MISO") (class "Default")
      (node (ref "IC1") (pin "22") (pinfunction "PGED3/AN3/C2INA/RPB3/RB3_22") (pintype "bidirectional"))
      (node (ref "IC9") (pin "2") (pinfunction "Q_2") (pintype "bidirectional"))
      (node (ref "O13") (pin "P$1") (pinfunction "TP_P$1") (pintype "passive"))
    )
    (net (code "97") (name "/SDO2-MOSI") (class "Default")
      (node (ref "IC1") (pin "20") (pinfunction "AN5/C1INA/RPB5/RB5_20") (pintype "bidirectional"))
      (node (ref "IC9") (pin "5") (pinfunction "D_5") (pintype "input"))
      (node (ref "O12") (pin "P$1") (pinfunction "TP_P$1") (pintype "passive"))
    )
    (net (code "98") (name "/SIO-C-CAM") (class "Default")
      (node (ref "IC1") (pin "58") (pinfunction "SCL2/RA2_58") (pintype "bidirectional"))
      (node (ref "J1") (pin "5") (pinfunction "5_5") (pintype "passive"))
      (node (ref "J2") (pin "5") (pinfunction "5_5") (pintype "passive"))
      (node (ref "R13") (pin "1") (pinfunction "1_1") (pintype "passive"))
    )
    (net (code "99") (name "/SIO-D-CAM") (class "Default")
      (node (ref "IC1") (pin "59") (pinfunction "SDA2/RA3_59") (pintype "bidirectional"))
      (node (ref "J1") (pin "3") (pinfunction "3_3") (pintype "passive"))
      (node (ref "J2") (pin "3") (pinfunction "3_3") (pintype "passive"))
      (node (ref "R14") (pin "1") (pinfunction "1_1") (pintype "passive"))
    )
    (net (code "100") (name "/VBAT-LAN") (class "Default")
      (node (ref "D3") (pin "C") (pinfunction "C_C") (pintype "passive"))
      (node (ref "J3") (pin "1") (pinfunction "1_1") (pintype "passive"))
      (node (ref "J3") (pin "3") (pinfunction "3_3") (pintype "passive"))
      (node (ref "J4") (pin "1") (pinfunction "1_1") (pintype "passive"))
      (node (ref "J4") (pin "3") (pinfunction "3_3") (pintype "passive"))
      (node (ref "L11") (pin "2") (pinfunction "2_2") (pintype "passive"))
    )
    (net (code "101") (name "/VBAT-LAN-F") (class "Default")
      (node (ref "C33") (pin "1") (pinfunction "1_1") (pintype "passive"))
      (node (ref "C34") (pin "1") (pinfunction "1_1") (pintype "passive"))
      (node (ref "D6") (pin "K") (pinfunction "K_K") (pintype "passive"))
      (node (ref "L11") (pin "1") (pinfunction "1_1") (pintype "passive"))
      (node (ref "Q5") (pin "2") (pinfunction "S_2") (pintype "passive"))
      (node (ref "Q5") (pin "5") (pinfunction "S_5") (pintype "passive"))
      (node (ref "R132") (pin "1") (pinfunction "1_1") (pintype "passive"))
      (node (ref "R36") (pin "2") (pinfunction "2_2") (pintype "passive"))
      (node (ref "R38") (pin "2") (pinfunction "2_2") (pintype "passive"))
      (node (ref "R42") (pin "1") (pinfunction "1_1") (pintype "passive"))
      (node (ref "R45") (pin "1") (pinfunction "1_1") (pintype "passive"))
      (node (ref "R94") (pin "1") (pinfunction "1_1") (pintype "passive"))
    )
    (net (code "102") (name "/VBAT-ON") (class "Default")
      (node (ref "IC1") (pin "52") (pinfunction "RPF2/RF2_52") (pintype "bidirectional"))
      (node (ref "O42") (pin "P$1") (pinfunction "TP_P$1") (pintype "passive"))
      (node (ref "Q4") (pin "2") (pinfunction "G_2") (pintype "passive"))
      (node (ref "R132") (pin "2") (pinfunction "2_2") (pintype "passive"))
      (node (ref "R41") (pin "1") (pinfunction "1_1") (pintype "passive"))
      (node (ref "T5") (pin "P$1") (pinfunction "TP_P$1") (pintype "passive"))
    )
    (net (code "103") (name "/VBAT-SENSE") (class "Default")
      (node (ref "C64") (pin "1") (pinfunction "1_1") (pintype "passive"))
      (node (ref "IC1") (pin "26") (pinfunction "PGEC2/AN6/RPB6/RB6_26") (pintype "bidirectional"))
      (node (ref "O15") (pin "P$1") (pinfunction "TP_P$1") (pintype "passive"))
      (node (ref "R100") (pin "1") (pinfunction "1_1") (pintype "passive"))
      (node (ref "T37") (pin "P$1") (pinfunction "TP_P$1") (pintype "passive"))
    )
    (net (code "104") (name "/VBATLAN-SENSE") (class "Default")
      (node (ref "C36") (pin "1") (pinfunction "1_1") (pintype "passive"))
      (node (ref "IC1") (pin "27") (pinfunction "PGED2/AN7/RPB7/CTED3/RB7_27") (pintype "bidirectional"))
      (node (ref "O16") (pin "P$1") (pinfunction "TP_P$1") (pintype "passive"))
      (node (ref "R101") (pin "1") (pinfunction "1_1") (pintype "passive"))
      (node (ref "T38") (pin "P$1") (pinfunction "TP_P$1") (pintype "passive"))
    )
    (net (code "105") (name "/VBUS") (class "Default")
      (node (ref "IC1") (pin "54") (pinfunction "VBUS_54") (pintype "input"))
      (node (ref "R128") (pin "2") (pinfunction "2_2") (pintype "passive"))
    )
    (net (code "106") (name "/VPS-ON") (class "Default")
      (node (ref "IC1") (pin "53") (pinfunction "RPF8/RF8_53") (pintype "bidirectional"))
      (node (ref "O41") (pin "P$1") (pinfunction "TP_P$1") (pintype "passive"))
      (node (ref "Q4") (pin "5") (pinfunction "G_5") (pintype "passive"))
      (node (ref "R44") (pin "1") (pinfunction "1_1") (pintype "passive"))
      (node (ref "T7") (pin "P$1") (pinfunction "TP_P$1") (pintype "passive"))
    )
    (net (code "107") (name "/VPS-PWR") (class "Default")
      (node (ref "D4") (pin "C") (pinfunction "C_C") (pintype "passive"))
      (node (ref "J3") (pin "6") (pinfunction "6_6") (pintype "passive"))
      (node (ref "J4") (pin "6") (pinfunction "6_6") (pintype "passive"))
      (node (ref "L10") (pin "2") (pinfunction "2_2") (pintype "passive"))
    )
    (net (code "108") (name "/VPS-PWR-F") (class "Default")
      (node (ref "L10") (pin "1") (pinfunction "1_1") (pintype "passive"))
      (node (ref "Q5") (pin "4") (pinfunction "D_4") (pintype "passive"))
      (node (ref "R23") (pin "2") (pinfunction "2_2") (pintype "passive"))
    )
    (net (code "109") (name "/VPS-SENSE") (class "Default")
      (node (ref "C65") (pin "1") (pinfunction "1_1") (pintype "passive"))
      (node (ref "IC1") (pin "12") (pinfunction "AN18/C2IND/RPG8/PMA3/RG8_12") (pintype "bidirectional"))
      (node (ref "O7") (pin "P$1") (pinfunction "TP_P$1") (pintype "passive"))
      (node (ref "R48") (pin "2") (pinfunction "2_2") (pintype "passive"))
      (node (ref "R49") (pin "1") (pinfunction "1_1") (pintype "passive"))
      (node (ref "T3") (pin "P$1") (pinfunction "TP_P$1") (pintype "passive"))
    )
    (net (code "110") (name "/VSYNC") (class "Default")
      (node (ref "IC1") (pin "8") (pinfunction "RPC3/RC3_8") (pintype "bidirectional"))
      (node (ref "J1") (pin "7") (pinfunction "7_7") (pintype "passive"))
      (node (ref "J2") (pin "7") (pinfunction "7_7") (pintype "passive"))
      (node (ref "O4") (pin "P$1") (pinfunction "TP_P$1") (pintype "passive"))
      (node (ref "T19") (pin "P$1") (pinfunction "TP_P$1") (pintype "passive"))
    )
    (net (code "111") (name "/WAKE-SW") (class "Default")
      (node (ref "IC1") (pin "72") (pinfunction "RPD0/INT0/RD0_72") (pintype "bidirectional"))
      (node (ref "J13") (pin "5") (pinfunction "5_5") (pintype "passive"))
      (node (ref "J14") (pin "5") (pinfunction "5_5") (pintype "passive"))
      (node (ref "O38") (pin "P$1") (pinfunction "TP_P$1") (pintype "passive"))
      (node (ref "T42") (pin "P$1") (pinfunction "TP_P$1") (pintype "passive"))
    )
    (net (code "112") (name "/WE-SRAM") (class "Default")
      (node (ref "IC1") (pin "81") (pinfunction "RPD4/PMWR/RD4_81") (pintype "bidirectional"))
      (node (ref "IC2") (pin "11") (pinfunction "~{WE}_11") (pintype "input"))
      (node (ref "R4") (pin "1") (pinfunction "1_1") (pintype "passive"))
    )
    (net (code "113") (name "/XCLK1") (class "Default")
      (node (ref "IC1") (pin "7") (pinfunction "RPC2/RC2_7") (pintype "bidirectional"))
      (node (ref "J1") (pin "13") (pinfunction "13_13") (pintype "passive"))
      (node (ref "J2") (pin "13") (pinfunction "13_13") (pintype "passive"))
      (node (ref "O3") (pin "P$1") (pinfunction "TP_P$1") (pintype "passive"))
      (node (ref "T16") (pin "P$1") (pinfunction "TP_P$1") (pintype "passive"))
    )
    (net (code "114") (name "/Y2") (class "Default")
      (node (ref "IC1") (pin "68") (pinfunction "RPD8/RTCC/RD8_68") (pintype "bidirectional"))
      (node (ref "J1") (pin "19") (pinfunction "19_19") (pintype "passive"))
      (node (ref "J2") (pin "19") (pinfunction "19_19") (pintype "passive"))
    )
    (net (code "115") (name "/Y3") (class "Default")
      (node (ref "IC1") (pin "69") (pinfunction "RPD9/RD9_69") (pintype "bidirectional"))
      (node (ref "J1") (pin "21") (pinfunction "21_21") (pintype "passive"))
      (node (ref "J2") (pin "21") (pinfunction "21_21") (pintype "passive"))
    )
    (net (code "116") (name "/Y4") (class "Default")
      (node (ref "IC1") (pin "70") (pinfunction "RPD10/SCK1/PMCS2/RD10_70") (pintype "bidirectional"))
      (node (ref "J1") (pin "22") (pinfunction "22_22") (pintype "passive"))
      (node (ref "J2") (pin "22") (pinfunction "22_22") (pintype "passive"))
    )
    (net (code "117") (name "/Y5") (class "Default")
      (node (ref "IC1") (pin "71") (pinfunction "RPD11/PMCS1/RD11_71") (pintype "bidirectional"))
      (node (ref "J1") (pin "20") (pinfunction "20_20") (pintype "passive"))
      (node (ref "J2") (pin "20") (pinfunction "20_20") (pintype "passive"))
    )
    (net (code "118") (name "/Y6") (class "Default")
      (node (ref "IC1") (pin "79") (pinfunction "RPD12/PMD12/RD12_79") (pintype "bidirectional"))
      (node (ref "J1") (pin "18") (pinfunction "18_18") (pintype "passive"))
      (node (ref "J2") (pin "18") (pinfunction "18_18") (pintype "passive"))
    )
    (net (code "119") (name "/Y7") (class "Default")
      (node (ref "IC1") (pin "80") (pinfunction "PMD13/RD13_80") (pintype "bidirectional"))
      (node (ref "J1") (pin "16") (pinfunction "16_16") (pintype "passive"))
      (node (ref "J2") (pin "16") (pinfunction "16_16") (pintype "passive"))
    )
    (net (code "120") (name "/Y8") (class "Default")
      (node (ref "IC1") (pin "47") (pinfunction "RPD14/RD14_47") (pintype "bidirectional"))
      (node (ref "J1") (pin "14") (pinfunction "14_14") (pintype "passive"))
      (node (ref "J2") (pin "14") (pinfunction "14_14") (pintype "passive"))
    )
    (net (code "121") (name "/Y9") (class "Default")
      (node (ref "IC1") (pin "48") (pinfunction "RPD15/RD15_48") (pintype "bidirectional"))
      (node (ref "J1") (pin "12") (pinfunction "12_12") (pintype "passive"))
      (node (ref "J2") (pin "12") (pinfunction "12_12") (pintype "passive"))
    )
    (net (code "122") (name "/{slash}3.3V1PWRON") (class "Default")
      (node (ref "IC1") (pin "21") (pinfunction "AN4/C1INB/USBOEN/RB4_21") (pintype "bidirectional"))
      (node (ref "O44") (pin "P$1") (pinfunction "TP_P$1") (pintype "passive"))
      (node (ref "R24") (pin "2") (pinfunction "2_2") (pintype "passive"))
      (node (ref "T32") (pin "P$1") (pinfunction "TP_P$1") (pintype "passive"))
    )
    (net (code "123") (name "/{slash}3.3V2PWRON") (class "Default")
      (node (ref "IC1") (pin "96") (pinfunction "TRD1/RG12_96") (pintype "bidirectional"))
      (node (ref "O23") (pin "P$1") (pinfunction "TP_P$1") (pintype "passive"))
      (node (ref "R75") (pin "2") (pinfunction "2_2") (pintype "passive"))
      (node (ref "T33") (pin "P$1") (pinfunction "TP_P$1") (pintype "passive"))
    )
    (net (code "124") (name "/{slash}CAM-PWRON") (class "Default")
      (node (ref "IC1") (pin "95") (pinfunction "TRD2/RG14_95") (pintype "bidirectional"))
      (node (ref "O24") (pin "P$1") (pinfunction "TP_P$1") (pintype "passive"))
      (node (ref "R10") (pin "1") (pinfunction "1_1") (pintype "passive"))
      (node (ref "T30") (pin "P$1") (pinfunction "TP_P$1") (pintype "passive"))
    )
    (net (code "125") (name "/{slash}FMEM1-CS") (class "Default")
      (node (ref "IC1") (pin "11") (pinfunction "AN17/C1INC/RPG7/PMA4/RG7_11") (pintype "bidirectional"))
      (node (ref "IC9") (pin "1") (pinfunction "/S_1") (pintype "input"))
      (node (ref "O6") (pin "P$1") (pinfunction "TP_P$1") (pintype "passive"))
      (node (ref "R25") (pin "1") (pinfunction "1_1") (pintype "passive"))
      (node (ref "T27") (pin "P$1") (pinfunction "TP_P$1") (pintype "passive"))
    )
    (net (code "126") (name "/{slash}MCLR") (class "Default")
      (node (ref "IC1") (pin "13") (pinfunction "~{MCLR}_13") (pintype "input"))
      (node (ref "J17") (pin "1") (pinfunction "1_1") (pintype "passive"))
      (node (ref "R90") (pin "2") (pinfunction "2_2") (pintype "passive"))
    )
    (net (code "127") (name "/{slash}NCS") (class "Default")
      (node (ref "IC1") (pin "23") (pinfunction "PGEC3/AN2/C2INB/RPB2/CTED13/RB2_23") (pintype "bidirectional"))
      (node (ref "O14") (pin "P$1") (pinfunction "TP_P$1") (pintype "passive"))
    )
    (net (code "128") (name "/{slash}PRESENT") (class "Default")
      (node (ref "R131") (pin "2") (pinfunction "2_2") (pintype "passive"))
    )
    (net (code "129") (name "/{slash}VPS-PWRON") (class "Default")
      (node (ref "IC1") (pin "17") (pinfunction "TMS/CTED1/RA0_17") (pintype "bidirectional"))
      (node (ref "O9") (pin "P$1") (pinfunction "TP_P$1") (pintype "passive"))
      (node (ref "R107") (pin "2") (pinfunction "2_2") (pintype "passive"))
      (node (ref "T31") (pin "P$1") (pinfunction "TP_P$1") (pintype "passive"))
    )
    (net (code "130") (name "DGND") (class "Default")
      (node (ref "C1") (pin "2") (pinfunction "2_2") (pintype "passive"))
      (node (ref "C11") (pin "-") (pinfunction "-_-") (pintype "passive"))
      (node (ref "C12") (pin "-") (pinfunction "-_-") (pintype "passive"))
      (node (ref "C13") (pin "-") (pinfunction "-_-") (pintype "passive"))
      (node (ref "C14") (pin "-") (pinfunction "-_-") (pintype "passive"))
      (node (ref "C15") (pin "2") (pinfunction "2_2") (pintype "passive"))
      (node (ref "C16") (pin "-") (pinfunction "-_-") (pintype "passive"))
      (node (ref "C17") (pin "-") (pinfunction "-_-") (pintype "passive"))
      (node (ref "C18") (pin "2") (pinfunction "2_2") (pintype "passive"))
      (node (ref "C19") (pin "2") (pinfunction "2_2") (pintype "passive"))
      (node (ref "C2") (pin "2") (pinfunction "2_2") (pintype "passive"))
      (node (ref "C20") (pin "-") (pinfunction "-_-") (pintype "passive"))
      (node (ref "C22") (pin "2") (pinfunction "2_2") (pintype "passive"))
      (node (ref "C23") (pin "2") (pinfunction "2_2") (pintype "passive"))
      (node (ref "C24") (pin "1") (pinfunction "1_1") (pintype "passive"))
      (node (ref "C27") (pin "2") (pinfunction "2_2") (pintype "passive"))
      (node (ref "C28") (pin "2") (pinfunction "2_2") (pintype "passive"))
      (node (ref "C29") (pin "2") (pinfunction "2_2") (pintype "passive"))
      (node (ref "C30") (pin "2") (pinfunction "2_2") (pintype "passive"))
      (node (ref "C31") (pin "-") (pinfunction "-_-") (pintype "passive"))
      (node (ref "C32") (pin "2") (pinfunction "2_2") (pintype "passive"))
      (node (ref "C35") (pin "2") (pinfunction "2_2") (pintype "passive"))
      (node (ref "C36") (pin "2") (pinfunction "2_2") (pintype "passive"))
      (node (ref "C37") (pin "2") (pinfunction "2_2") (pintype "passive"))
      (node (ref "C38") (pin "2") (pinfunction "2_2") (pintype "passive"))
      (node (ref "C39") (pin "2") (pinfunction "2_2") (pintype "passive"))
      (node (ref "C40") (pin "2") (pinfunction "2_2") (pintype "passive"))
      (node (ref "C41") (pin "2") (pinfunction "2_2") (pintype "passive"))
      (node (ref "C46") (pin "2") (pinfunction "2_2") (pintype "passive"))
      (node (ref "C47") (pin "2") (pinfunction "2_2") (pintype "passive"))
      (node (ref "C48") (pin "2") (pinfunction "2_2") (pintype "passive"))
      (node (ref "C49") (pin "2") (pinfunction "2_2") (pintype "passive"))
      (node (ref "C5") (pin "2") (pinfunction "2_2") (pintype "passive"))
      (node (ref "C50") (pin "2") (pinfunction "2_2") (pintype "passive"))
      (node (ref "C51") (pin "2") (pinfunction "2_2") (pintype "passive"))
      (node (ref "C52") (pin "2") (pinfunction "2_2") (pintype "passive"))
      (node (ref "C53") (pin "2") (pinfunction "2_2") (pintype "passive"))
      (node (ref "C54") (pin "-") (pinfunction "-_-") (pintype "passive"))
      (node (ref "C55") (pin "2") (pinfunction "2_2") (pintype "passive"))
      (node (ref "C56") (pin "-") (pinfunction "-_-") (pintype "passive"))
      (node (ref "C57") (pin "2") (pinfunction "2_2") (pintype "passive"))
      (node (ref "C58") (pin "2") (pinfunction "2_2") (pintype "passive"))
      (node (ref "C59") (pin "2") (pinfunction "2_2") (pintype "passive"))
      (node (ref "C6") (pin "2") (pinfunction "2_2") (pintype "passive"))
      (node (ref "C60") (pin "2") (pinfunction "2_2") (pintype "passive"))
      (node (ref "C61") (pin "2") (pinfunction "2_2") (pintype "passive"))
      (node (ref "C62") (pin "2") (pinfunction "2_2") (pintype "passive"))
      (node (ref "C63") (pin "2") (pinfunction "2_2") (pintype "passive"))
      (node (ref "C64") (pin "2") (pinfunction "2_2") (pintype "passive"))
      (node (ref "C65") (pin "2") (pinfunction "2_2") (pintype "passive"))
      (node (ref "C66") (pin "2") (pinfunction "2_2") (pintype "passive"))
      (node (ref "C67") (pin "2") (pinfunction "2_2") (pintype "passive"))
      (node (ref "C7") (pin "1") (pinfunction "1_1") (pintype "passive"))
      (node (ref "C75") (pin "2") (pinfunction "2_2") (pintype "passive"))
      (node (ref "C76") (pin "2") (pinfunction "2_2") (pintype "passive"))
      (node (ref "C77") (pin "2") (pinfunction "2_2") (pintype "passive"))
      (node (ref "C78") (pin "2") (pinfunction "2_2") (pintype "passive"))
      (node (ref "C79") (pin "2") (pinfunction "2_2") (pintype "passive"))
      (node (ref "C8") (pin "1") (pinfunction "1_1") (pintype "passive"))
      (node (ref "C80") (pin "2") (pinfunction "2_2") (pintype "passive"))
      (node (ref "C81") (pin "-") (pinfunction "-_-") (pintype "passive"))
      (node (ref "C83") (pin "2") (pinfunction "2_2") (pintype "passive"))
      (node (ref "C84") (pin "2") (pinfunction "2_2") (pintype "passive"))
      (node (ref "C85") (pin "2") (pinfunction "2_2") (pintype "passive"))
      (node (ref "C86") (pin "-") (pinfunction "-_-") (pintype "passive"))
      (node (ref "C87") (pin "-") (pinfunction "-_-") (pintype "passive"))
      (node (ref "C88") (pin "2") (pinfunction "2_2") (pintype "passive"))
      (node (ref "D2") (pin "-") (pinfunction "A_-") (pintype "passive"))
      (node (ref "D5") (pin "K") (pinfunction "K_K") (pintype "passive"))
      (node (ref "D7") (pin "A") (pinfunction "A_A") (pintype "passive"))
      (node (ref "IC1") (pin "15") (pinfunction "VSS2_15") (pintype "input"))
      (node (ref "IC1") (pin "31") (pinfunction "AVSS_31") (pintype "input"))
      (node (ref "IC1") (pin "36") (pinfunction "VSS3_36") (pintype "input"))
      (node (ref "IC1") (pin "45") (pinfunction "VSS4_45") (pintype "input"))
      (node (ref "IC1") (pin "65") (pinfunction "VSS5_65") (pintype "input"))
      (node (ref "IC1") (pin "75") (pinfunction "VSS1_75") (pintype "input"))
      (node (ref "IC10") (pin "1") (pinfunction "GND_1") (pintype "input"))
      (node (ref "IC10") (pin "2") (pinfunction "GND1_2") (pintype "input"))
      (node (ref "IC11") (pin "1") (pinfunction "A0_1") (pintype "input"))
      (node (ref "IC11") (pin "3") (pinfunction "A2_3") (pintype "input"))
      (node (ref "IC11") (pin "4") (pinfunction "GND_4") (pintype "input"))
      (node (ref "IC12") (pin "5") (pinfunction "GND_5") (pintype "input"))
      (node (ref "IC13") (pin "3") (pinfunction "GND_3") (pintype "bidirectional"))
      (node (ref "IC14") (pin "1") (pinfunction "1_1") (pintype "input"))
      (node (ref "IC15") (pin "1") (pinfunction "1_1") (pintype "input"))
      (node (ref "IC16") (pin "4") (pinfunction "V-_4") (pintype "input"))
      (node (ref "IC2") (pin "14") (pinfunction "~{UB}_14") (pintype "input"))
      (node (ref "IC2") (pin "15") (pinfunction "~{LB}_15") (pintype "input"))
      (node (ref "IC2") (pin "26") (pinfunction "~{CS1}_26") (pintype "input"))
      (node (ref "IC2") (pin "27") (pinfunction "GND1_27") (pintype "bidirectional"))
      (node (ref "IC2") (pin "46") (pinfunction "GND2_46") (pintype "bidirectional"))
      (node (ref "IC2") (pin "47") (pinfunction "~{BYTE}_47") (pintype "input"))
      (node (ref "IC3") (pin "1") (pinfunction "~{OE}_1") (pintype "input"))
      (node (ref "IC3") (pin "10") (pinfunction "GND_10") (pintype "bidirectional"))
      (node (ref "IC4") (pin "1") (pinfunction "~{OE}_1") (pintype "input"))
      (node (ref "IC4") (pin "10") (pinfunction "GND_10") (pintype "bidirectional"))
      (node (ref "IC5") (pin "2") (pinfunction "GND_2") (pintype "input"))
      (node (ref "IC6") (pin "2") (pinfunction "GND_2") (pintype "input"))
      (node (ref "IC7") (pin "1") (pinfunction "A0_1") (pintype "input"))
      (node (ref "IC7") (pin "2") (pinfunction "A1_2") (pintype "input"))
      (node (ref "IC7") (pin "3") (pinfunction "A2_3") (pintype "input"))
      (node (ref "IC7") (pin "4") (pinfunction "GND_4") (pintype "input"))
      (node (ref "IC7") (pin "7") (pinfunction "WP_7") (pintype "input"))
      (node (ref "IC8") (pin "10") (pinfunction "SYNC_10") (pintype "bidirectional"))
      (node (ref "IC8") (pin "EP") (pinfunction "GND_EP") (pintype "bidirectional"))
      (node (ref "IC9") (pin "4") (pinfunction "GND_4") (pintype "input"))
      (node (ref "J1") (pin "15") (pinfunction "15_15") (pintype "passive"))
      (node (ref "J11") (pin "2") (pinfunction "2_2") (pintype "passive"))
      (node (ref "J12") (pin "4_GND") (pinfunction "GND_4_GND") (pintype "bidirectional"))
      (node (ref "J12") (pin "SH1") (pinfunction "GND_SH1_SH1") (pintype "bidirectional"))
      (node (ref "J12") (pin "SH2") (pinfunction "GND_SH2_SH2") (pintype "bidirectional"))
      (node (ref "J13") (pin "1") (pinfunction "1_1") (pintype "passive"))
      (node (ref "J14") (pin "1") (pinfunction "1_1") (pintype "passive"))
      (node (ref "J15") (pin "2") (pinfunction "2_2") (pintype "passive"))
      (node (ref "J16") (pin "2") (pinfunction "2_2") (pintype "passive"))
      (node (ref "J17") (pin "3") (pinfunction "3_3") (pintype "passive"))
      (node (ref "J18") (pin "2") (pinfunction "2_2") (pintype "passive"))
      (node (ref "J2") (pin "15") (pinfunction "15_15") (pintype "passive"))
      (node (ref "J5") (pin "1") (pinfunction "1_1") (pintype "bidirectional"))
      (node (ref "J6") (pin "1") (pinfunction "1_1") (pintype "bidirectional"))
      (node (ref "L12") (pin "1") (pinfunction "1_1") (pintype "passive"))
      (node (ref "PCB3") (pin "1") (pinfunction "P$1_1") (pintype "bidirectional"))
      (node (ref "Q10") (pin "4") (pinfunction "S_4") (pintype "passive"))
      (node (ref "Q11") (pin "4") (pinfunction "S_4") (pintype "passive"))
      (node (ref "Q12") (pin "4") (pinfunction "S_4") (pintype "passive"))
      (node (ref "Q13") (pin "4") (pinfunction "S_4") (pintype "passive"))
      (node (ref "Q14") (pin "1") (pinfunction "S_1") (pintype "passive"))
      (node (ref "Q3") (pin "1") (pinfunction "S_1") (pintype "passive"))
      (node (ref "R1") (pin "1") (pinfunction "1_1") (pintype "passive"))
      (node (ref "R112") (pin "2") (pinfunction "2_2") (pintype "passive"))
      (node (ref "R118") (pin "2") (pinfunction "2_2") (pintype "passive"))
      (node (ref "R17") (pin "2") (pinfunction "2_2") (pintype "passive"))
      (node (ref "R19") (pin "2") (pinfunction "2_2") (pintype "passive"))
      (node (ref "R2") (pin "1") (pinfunction "1_1") (pintype "passive"))
      (node (ref "R21") (pin "2") (pinfunction "2_2") (pintype "passive"))
      (node (ref "R31") (pin "2") (pinfunction "2_2") (pintype "passive"))
      (node (ref "R40") (pin "1") (pinfunction "1_1") (pintype "passive"))
      (node (ref "R41") (pin "2") (pinfunction "2_2") (pintype "passive"))
      (node (ref "R43") (pin "1") (pinfunction "1_1") (pintype "passive"))
      (node (ref "R44") (pin "2") (pinfunction "2_2") (pintype "passive"))
      (node (ref "R46") (pin "1") (pinfunction "1_1") (pintype "passive"))
      (node (ref "R48") (pin "1") (pinfunction "1_1") (pintype "passive"))
      (node (ref "R5") (pin "1") (pinfunction "1_1") (pintype "passive"))
      (node (ref "R51") (pin "1") (pinfunction "1_1") (pintype "passive"))
      (node (ref "R52") (pin "2") (pinfunction "2_2") (pintype "passive"))
      (node (ref "R53") (pin "2") (pinfunction "2_2") (pintype "passive"))
      (node (ref "R54") (pin "2") (pinfunction "2_2") (pintype "passive"))
      (node (ref "R57") (pin "1") (pinfunction "1_1") (pintype "passive"))
      (node (ref "R58") (pin "2") (pinfunction "2_2") (pintype "passive"))
      (node (ref "R59") (pin "2") (pinfunction "2_2") (pintype "passive"))
      (node (ref "R6") (pin "2") (pinfunction "2_2") (pintype "passive"))
      (node (ref "R60") (pin "2") (pinfunction "2_2") (pintype "passive"))
      (node (ref "R64") (pin "2") (pinfunction "2_2") (pintype "passive"))
      (node (ref "R67") (pin "2") (pinfunction "2_2") (pintype "passive"))
      (node (ref "R7") (pin "2") (pinfunction "2_2") (pintype "passive"))
      (node (ref "R70") (pin "2") (pinfunction "2_2") (pintype "passive"))
      (node (ref "R71") (pin "2") (pinfunction "2_2") (pintype "passive"))
      (node (ref "R76") (pin "2") (pinfunction "2_2") (pintype "passive"))
      (node (ref "R80") (pin "2") (pinfunction "2_2") (pintype "passive"))
      (node (ref "R83") (pin "2") (pinfunction "2_2") (pintype "passive"))
      (node (ref "R86") (pin "2") (pinfunction "2_2") (pintype "passive"))
      (node (ref "R88") (pin "2") (pinfunction "2_2") (pintype "passive"))
      (node (ref "R96") (pin "2") (pinfunction "2_2") (pintype "passive"))
      (node (ref "R99") (pin "2") (pinfunction "2_2") (pintype "passive"))
    )
    (net (code "131") (name "Net-(C24-Pad2)") (class "Default")
      (node (ref "C24") (pin "2") (pinfunction "2_2") (pintype "passive"))
      (node (ref "R77") (pin "2") (pinfunction "2_2") (pintype "passive"))
    )
    (net (code "132") (name "Net-(C32-Pad1)") (class "Default")
      (node (ref "C32") (pin "1") (pinfunction "1_1") (pintype "passive"))
      (node (ref "R68") (pin "2") (pinfunction "2_2") (pintype "passive"))
      (node (ref "R69") (pin "1") (pinfunction "1_1") (pintype "passive"))
    )
    (net (code "133") (name "Net-(C37-Pad1)") (class "Default")
      (node (ref "C37") (pin "1") (pinfunction "1_1") (pintype "passive"))
      (node (ref "R78") (pin "2") (pinfunction "2_2") (pintype "passive"))
      (node (ref "R79") (pin "1") (pinfunction "1_1") (pintype "passive"))
    )
    (net (code "134") (name "Net-(C38-Pad1)") (class "Default")
      (node (ref "C38") (pin "1") (pinfunction "1_1") (pintype "passive"))
      (node (ref "R84") (pin "2") (pinfunction "2_2") (pintype "passive"))
      (node (ref "R85") (pin "1") (pinfunction "1_1") (pintype "passive"))
    )
    (net (code "135") (name "Net-(C39-Pad1)") (class "Default")
      (node (ref "C39") (pin "1") (pinfunction "1_1") (pintype "passive"))
      (node (ref "IC14") (pin "4") (pinfunction "4_4") (pintype "input"))
      (node (ref "R30") (pin "1") (pinfunction "1_1") (pintype "passive"))
    )
    (net (code "136") (name "Net-(C40-Pad1)") (class "Default")
      (node (ref "C40") (pin "1") (pinfunction "1_1") (pintype "passive"))
      (node (ref "R90") (pin "1") (pinfunction "1_1") (pintype "passive"))
      (node (ref "R91") (pin "1") (pinfunction "1_1") (pintype "passive"))
    )
    (net (code "137") (name "Net-(C46-Pad1)") (class "Default")
      (node (ref "C46") (pin "1") (pinfunction "1_1") (pintype "passive"))
      (node (ref "R62") (pin "2") (pinfunction "2_2") (pintype "passive"))
      (node (ref "R63") (pin "1") (pinfunction "1_1") (pintype "passive"))
    )
    (net (code "138") (name "Net-(C71-Pad+)") (class "Default")
      (node (ref "C71") (pin "+") (pinfunction "+_+") (pintype "passive"))
      (node (ref "C72") (pin "1") (pinfunction "1_1") (pintype "passive"))
      (node (ref "J9") (pin "1") (pinfunction "1_1") (pintype "passive"))
      (node (ref "R124") (pin "2") (pinfunction "2_2") (pintype "passive"))
    )
    (net (code "139") (name "Net-(C71-Pad-)") (class "Default")
      (node (ref "C71") (pin "-") (pinfunction "-_-") (pintype "passive"))
      (node (ref "C72") (pin "2") (pinfunction "2_2") (pintype "passive"))
      (node (ref "R110") (pin "2") (pinfunction "2_2") (pintype "passive"))
      (node (ref "R111") (pin "1") (pinfunction "1_1") (pintype "passive"))
      (node (ref "R114") (pin "2") (pinfunction "2_2") (pintype "passive"))
      (node (ref "R115") (pin "1") (pinfunction "1_1") (pintype "passive"))
    )
    (net (code "140") (name "Net-(C73-Pad+)") (class "Default")
      (node (ref "C73") (pin "+") (pinfunction "+_+") (pintype "passive"))
      (node (ref "C74") (pin "1") (pinfunction "1_1") (pintype "passive"))
      (node (ref "J10") (pin "1") (pinfunction "1_1") (pintype "passive"))
      (node (ref "R125") (pin "2") (pinfunction "2_2") (pintype "passive"))
    )
    (net (code "141") (name "Net-(C73-Pad-)") (class "Default")
      (node (ref "C73") (pin "-") (pinfunction "-_-") (pintype "passive"))
      (node (ref "C74") (pin "2") (pinfunction "2_2") (pintype "passive"))
      (node (ref "R116") (pin "2") (pinfunction "2_2") (pintype "passive"))
      (node (ref "R117") (pin "1") (pinfunction "1_1") (pintype "passive"))
      (node (ref "R122") (pin "2") (pinfunction "2_2") (pintype "passive"))
      (node (ref "R123") (pin "1") (pinfunction "1_1") (pintype "passive"))
    )
    (net (code "142") (name "Net-(D2-C)") (class "Default")
      (node (ref "C26") (pin "1") (pinfunction "1_1") (pintype "passive"))
      (node (ref "C30") (pin "1") (pinfunction "1_1") (pintype "passive"))
      (node (ref "C31") (pin "+") (pinfunction "+_+") (pintype "passive"))
      (node (ref "D2") (pin "+") (pinfunction "C_+") (pintype "passive"))
      (node (ref "IC8") (pin "1") (pinfunction "BD_1") (pintype "bidirectional"))
      (node (ref "L9") (pin "2") (pinfunction "2_2") (pintype "passive"))
      (node (ref "R129") (pin "2") (pinfunction "2_2") (pintype "passive"))
      (node (ref "R20") (pin "1") (pinfunction "1_1") (pintype "passive"))
    )
    (net (code "143") (name "Net-(D3-PadA)") (class "Default")
      (node (ref "D3") (pin "A") (pinfunction "A_A") (pintype "passive"))
      (node (ref "D4") (pin "A") (pinfunction "A_A") (pintype "passive"))
      (node (ref "J3") (pin "2") (pinfunction "2_2") (pintype "passive"))
      (node (ref "J3") (pin "7") (pinfunction "7_7") (pintype "passive"))
      (node (ref "J3") (pin "8") (pinfunction "8_8") (pintype "passive"))
      (node (ref "J4") (pin "2") (pinfunction "2_2") (pintype "passive"))
      (node (ref "J4") (pin "7") (pinfunction "7_7") (pintype "passive"))
      (node (ref "J4") (pin "8") (pinfunction "8_8") (pintype "passive"))
      (node (ref "L12") (pin "2") (pinfunction "2_2") (pintype "passive"))
    )
    (net (code "144") (name "Net-(D5-PadA)") (class "Default")
      (node (ref "D5") (pin "A") (pinfunction "A_A") (pintype "passive"))
      (node (ref "R29") (pin "2") (pinfunction "2_2") (pintype "passive"))
    )
    (net (code "145") (name "Net-(IC1-AVDD)") (class "Default")
      (node (ref "C55") (pin "1") (pinfunction "1_1") (pintype "passive"))
      (node (ref "C56") (pin "+") (pinfunction "+_+") (pintype "passive"))
      (node (ref "C88") (pin "1") (pinfunction "1_1") (pintype "passive"))
      (node (ref "IC1") (pin "30") (pinfunction "AVDD_30") (pintype "input"))
      (node (ref "R92") (pin "2") (pinfunction "2_2") (pintype "passive"))
    )
    (net (code "146") (name "Net-(IC1-CLKI{slash}RC12{slash}OSC1)") (class "Default")
      (node (ref "C60") (pin "1") (pinfunction "1_1") (pintype "passive"))
      (node (ref "IC1") (pin "63") (pinfunction "CLKI/RC12/OSC1_63") (pintype "bidirectional"))
      (node (ref "X1") (pin "3") (pinfunction "2_3") (pintype "passive"))
    )
    (net (code "147") (name "Net-(IC1-CLKO{slash}RC15{slash}OSC2)") (class "Default")
      (node (ref "C61") (pin "1") (pinfunction "1_1") (pintype "passive"))
      (node (ref "IC1") (pin "64") (pinfunction "CLKO/RC15/OSC2_64") (pintype "bidirectional"))
      (node (ref "X1") (pin "1") (pinfunction "1_1") (pintype "passive"))
    )
    (net (code "148") (name "Net-(IC1-VCAP)") (class "Default")
      (node (ref "C53") (pin "1") (pinfunction "1_1") (pintype "passive"))
      (node (ref "C54") (pin "+") (pinfunction "+_+") (pintype "passive"))
      (node (ref "IC1") (pin "85") (pinfunction "VCAP_85") (pintype "input"))
    )
    (net (code "149") (name "Net-(IC5-OUT)") (class "Default")
      (node (ref "C19") (pin "1") (pinfunction "1_1") (pintype "passive"))
      (node (ref "C20") (pin "+") (pinfunction "+_+") (pintype "passive"))
      (node (ref "IC5") (pin "5") (pinfunction "OUT_5") (pintype "output"))
      (node (ref "R126") (pin "2") (pinfunction "2_2") (pintype "passive"))
    )
    (net (code "150") (name "Net-(IC6-HTH)") (class "Default")
      (node (ref "IC6") (pin "1") (pinfunction "HTH_1") (pintype "input"))
      (node (ref "R46") (pin "2") (pinfunction "2_2") (pintype "passive"))
      (node (ref "R47") (pin "1") (pinfunction "1_1") (pintype "passive"))
    )
    (net (code "151") (name "Net-(IC6-LTH)") (class "Default")
      (node (ref "IC6") (pin "3") (pinfunction "LTH_3") (pintype "input"))
      (node (ref "R33") (pin "1") (pinfunction "1_1") (pintype "passive"))
      (node (ref "R47") (pin "2") (pinfunction "2_2") (pintype "passive"))
    )
    (net (code "152") (name "Net-(IC6-VDD)") (class "Default")
      (node (ref "C35") (pin "1") (pinfunction "1_1") (pintype "passive"))
      (node (ref "IC6") (pin "5") (pinfunction "VDD_5") (pintype "input"))
      (node (ref "R28") (pin "1") (pinfunction "1_1") (pintype "passive"))
    )
    (net (code "153") (name "Net-(IC8-BOOST)") (class "Default")
      (node (ref "C25") (pin "2") (pinfunction "2_2") (pintype "passive"))
      (node (ref "IC8") (pin "2") (pinfunction "BOOST_2") (pintype "bidirectional"))
    )
    (net (code "154") (name "Net-(IC8-EN)") (class "Default")
      (node (ref "IC8") (pin "5") (pinfunction "EN_5") (pintype "bidirectional"))
      (node (ref "JP1") (pin "2") (pinfunction "2_2") (pintype "bidirectional"))
      (node (ref "R22") (pin "2") (pinfunction "2_2") (pintype "passive"))
    )
    (net (code "155") (name "Net-(IC8-FB)") (class "Default")
      (node (ref "C26") (pin "2") (pinfunction "2_2") (pintype "passive"))
      (node (ref "IC8") (pin "6") (pinfunction "FB_6") (pintype "bidirectional"))
      (node (ref "R19") (pin "1") (pinfunction "1_1") (pintype "passive"))
      (node (ref "R20") (pin "2") (pinfunction "2_2") (pintype "passive"))
    )
    (net (code "156") (name "Net-(IC8-RT)") (class "Default")
      (node (ref "IC8") (pin "8") (pinfunction "RT_8") (pintype "bidirectional"))
      (node (ref "R17") (pin "1") (pinfunction "1_1") (pintype "passive"))
    )
    (net (code "157") (name "Net-(IC8-SS)") (class "Default")
      (node (ref "IC8") (pin "7") (pinfunction "SS_7") (pintype "bidirectional"))
      (node (ref "R77") (pin "1") (pinfunction "1_1") (pintype "passive"))
    )
    (net (code "158") (name "Net-(IC8-SW)") (class "Default")
      (node (ref "C25") (pin "1") (pinfunction "1_1") (pintype "passive"))
      (node (ref "D7") (pin "K") (pinfunction "K_K") (pintype "passive"))
      (node (ref "IC8") (pin "3") (pinfunction "SW_3") (pintype "bidirectional"))
      (node (ref "L9") (pin "1") (pinfunction "1_1") (pintype "passive"))
    )
    (net (code "159") (name "Net-(IC10-OUT)") (class "Default")
      (node (ref "IC10") (pin "3") (pinfunction "OUT_3") (pintype "output"))
      (node (ref "R102") (pin "1") (pinfunction "1_1") (pintype "passive"))
    )
    (net (code "160") (name "Net-(IC10-VIN+)") (class "Default")
      (node (ref "C29") (pin "1") (pinfunction "1_1") (pintype "passive"))
      (node (ref "F1") (pin "1") (pinfunction "1_1") (pintype "passive"))
      (node (ref "IC10") (pin "5") (pinfunction "VIN+_5") (pintype "input"))
      (node (ref "R39") (pin "2") (pinfunction "2_2") (pintype "passive"))
    )
    (net (code "161") (name "Net-(IC11-WP)") (class "Default")
      (node (ref "IC11") (pin "7") (pinfunction "WP_7") (pintype "input"))
      (node (ref "R18") (pin "2") (pinfunction "2_2") (pintype "passive"))
      (node (ref "TP1") (pin "P$1") (pinfunction "TP_P$1") (pintype "passive"))
    )
    (net (code "162") (name "Net-(IC13-VIN)") (class "Default")
      (node (ref "C58") (pin "1") (pinfunction "1_1") (pintype "passive"))
      (node (ref "C59") (pin "1") (pinfunction "1_1") (pintype "passive"))
      (node (ref "IC13") (pin "1") (pinfunction "VIN_1") (pintype "bidirectional"))
      (node (ref "R93") (pin "2") (pinfunction "2_2") (pintype "passive"))
    )
    (net (code "163") (name "Net-(IC16A-+IN)") (class "Default")
      (node (ref "C62") (pin "1") (pinfunction "1_1") (pintype "passive"))
      (node (ref "IC16") (pin "3") (pinfunction "+IN_3") (pintype "input"))
      (node (ref "R95") (pin "2") (pinfunction "2_2") (pintype "passive"))
      (node (ref "R96") (pin "1") (pinfunction "1_1") (pintype "passive"))
    )
    (net (code "164") (name "Net-(IC16A--IN)") (class "Default")
      (node (ref "IC16") (pin "1") (pinfunction "OUT_1") (pintype "output"))
      (node (ref "IC16") (pin "2") (pinfunction "-IN_2") (pintype "input"))
      (node (ref "R101") (pin "2") (pinfunction "2_2") (pintype "passive"))
    )
    (net (code "165") (name "Net-(IC16B-+IN)") (class "Default")
      (node (ref "C63") (pin "1") (pinfunction "1_1") (pintype "passive"))
      (node (ref "IC16") (pin "5") (pinfunction "+IN_5") (pintype "input"))
      (node (ref "R98") (pin "2") (pinfunction "2_2") (pintype "passive"))
      (node (ref "R99") (pin "1") (pinfunction "1_1") (pintype "passive"))
    )
    (net (code "166") (name "Net-(IC16B--IN)") (class "Default")
      (node (ref "IC16") (pin "6") (pinfunction "-IN_6") (pintype "input"))
      (node (ref "IC16") (pin "7") (pinfunction "OUT_7") (pintype "output"))
      (node (ref "R100") (pin "2") (pinfunction "2_2") (pintype "passive"))
    )
    (net (code "167") (name "Net-(IC16C-V+)") (class "Default")
      (node (ref "C67") (pin "1") (pinfunction "1_1") (pintype "passive"))
      (node (ref "IC16") (pin "8") (pinfunction "V+_8") (pintype "input"))
      (node (ref "R103") (pin "1") (pinfunction "1_1") (pintype "passive"))
    )
    (net (code "168") (name "Net-(J5-Pad4)") (class "Default")
      (node (ref "J5") (pin "4") (pinfunction "4_4") (pintype "bidirectional"))
      (node (ref "R62") (pin "1") (pinfunction "1_1") (pintype "passive"))
    )
    (net (code "169") (name "Net-(J6-Pad4)") (class "Default")
      (node (ref "J6") (pin "4") (pinfunction "4_4") (pintype "bidirectional"))
      (node (ref "R78") (pin "1") (pinfunction "1_1") (pintype "passive"))
    )
    (net (code "170") (name "Net-(J7-Pad2)") (class "Default")
      (node (ref "J7") (pin "2") (pinfunction "2_2") (pintype "passive"))
      (node (ref "R68") (pin "1") (pinfunction "1_1") (pintype "passive"))
    )
    (net (code "171") (name "Net-(J8-Pad2)") (class "Default")
      (node (ref "J8") (pin "2") (pinfunction "2_2") (pintype "passive"))
      (node (ref "R84") (pin "1") (pinfunction "1_1") (pintype "passive"))
    )
    (net (code "172") (name "Net-(J9-Pad2)") (class "Default")
      (node (ref "J9") (pin "2") (pinfunction "2_2") (pintype "passive"))
      (node (ref "R110") (pin "1") (pinfunction "1_1") (pintype "passive"))
      (node (ref "R114") (pin "1") (pinfunction "1_1") (pintype "passive"))
    )
    (net (code "173") (name "Net-(J10-Pad2)") (class "Default")
      (node (ref "J10") (pin "2") (pinfunction "2_2") (pintype "passive"))
      (node (ref "R116") (pin "1") (pinfunction "1_1") (pintype "passive"))
      (node (ref "R122") (pin "1") (pinfunction "1_1") (pintype "passive"))
    )
    (net (code "174") (name "Net-(J12-+5V)") (class "Default")
      (node (ref "C85") (pin "1") (pinfunction "1_1") (pintype "passive"))
      (node (ref "D6") (pin "A") (pinfunction "A_A") (pintype "passive"))
      (node (ref "IC15") (pin "4") (pinfunction "4_4") (pintype "input"))
      (node (ref "J12") (pin "1_+5V") (pinfunction "+5V_1_+5V") (pintype "bidirectional"))
      (node (ref "R128") (pin "1") (pinfunction "1_1") (pintype "passive"))
    )
    (net (code "175") (name "Net-(JP1-Pad1)") (class "Default")
      (node (ref "JP1") (pin "1") (pinfunction "1_1") (pintype "bidirectional"))
      (node (ref "R21") (pin "1") (pinfunction "1_1") (pintype "passive"))
    )
    (net (code "176") (name "Net-(L7-Pad1)") (class "Default")
      (node (ref "L7") (pin "1") (pinfunction "1_1") (pintype "passive"))
      (node (ref "R108") (pin "1") (pinfunction "1_1") (pintype "passive"))
    )
    (net (code "177") (name "Net-(L8-Pad1)") (class "Default")
      (node (ref "L8") (pin "1") (pinfunction "1_1") (pintype "passive"))
      (node (ref "R109") (pin "1") (pinfunction "1_1") (pintype "passive"))
    )
    (net (code "178") (name "Net-(L13-Pad2)") (class "Default")
      (node (ref "L13") (pin "2") (pinfunction "2_2") (pintype "passive"))
      (node (ref "R92") (pin "1") (pinfunction "1_1") (pintype "passive"))
    )
    (net (code "179") (name "Net-(Q1A-G)") (class "Default")
      (node (ref "C21") (pin "2") (pinfunction "2_2") (pintype "passive"))
      (node (ref "Q1") (pin "2") (pinfunction "G_2") (pintype "passive"))
      (node (ref "R10") (pin "2") (pinfunction "2_2") (pintype "passive"))
      (node (ref "R9") (pin "1") (pinfunction "1_1") (pintype "passive"))
    )
    (net (code "180") (name "Net-(Q1A-S)") (class "Default")
      (node (ref "Q1") (pin "1") (pinfunction "S_1") (pintype "passive"))
      (node (ref "R8") (pin "1") (pinfunction "1_1") (pintype "passive"))
    )
    (net (code "181") (name "Net-(Q1B-G)") (class "Default")
      (node (ref "C70") (pin "2") (pinfunction "2_2") (pintype "passive"))
      (node (ref "Q1") (pin "5") (pinfunction "G_5") (pintype "passive"))
      (node (ref "R75") (pin "1") (pinfunction "1_1") (pintype "passive"))
      (node (ref "R82") (pin "2") (pinfunction "2_2") (pintype "passive"))
    )
    (net (code "182") (name "Net-(Q1B-S)") (class "Default")
      (node (ref "Q1") (pin "4") (pinfunction "S_4") (pintype "passive"))
      (node (ref "R106") (pin "1") (pinfunction "1_1") (pintype "passive"))
    )
    (net (code "183") (name "Net-(Q2A-G)") (class "Default")
      (node (ref "C68") (pin "2") (pinfunction "2_2") (pintype "passive"))
      (node (ref "Q2") (pin "2") (pinfunction "G_2") (pintype "passive"))
      (node (ref "R107") (pin "1") (pinfunction "1_1") (pintype "passive"))
      (node (ref "R87") (pin "2") (pinfunction "2_2") (pintype "passive"))
    )
    (net (code "184") (name "Net-(Q2A-S)") (class "Default")
      (node (ref "Q2") (pin "1") (pinfunction "S_1") (pintype "passive"))
      (node (ref "R104") (pin "1") (pinfunction "1_1") (pintype "passive"))
    )
    (net (code "185") (name "Net-(Q2B-G)") (class "Default")
      (node (ref "C69") (pin "2") (pinfunction "2_2") (pintype "passive"))
      (node (ref "Q2") (pin "5") (pinfunction "G_5") (pintype "passive"))
      (node (ref "R24") (pin "1") (pinfunction "1_1") (pintype "passive"))
      (node (ref "R65") (pin "2") (pinfunction "2_2") (pintype "passive"))
    )
    (net (code "186") (name "Net-(Q2B-S)") (class "Default")
      (node (ref "Q2") (pin "4") (pinfunction "S_4") (pintype "passive"))
      (node (ref "R105") (pin "1") (pinfunction "1_1") (pintype "passive"))
    )
    (net (code "187") (name "Net-(Q3A-D)") (class "Default")
      (node (ref "Q3") (pin "6") (pinfunction "D_6") (pintype "passive"))
      (node (ref "R111") (pin "2") (pinfunction "2_2") (pintype "passive"))
      (node (ref "R115") (pin "2") (pinfunction "2_2") (pintype "passive"))
    )
    (net (code "188") (name "Net-(Q3A-G)") (class "Default")
      (node (ref "Q3") (pin "2") (pinfunction "G_2") (pintype "passive"))
      (node (ref "R112") (pin "1") (pinfunction "1_1") (pintype "passive"))
      (node (ref "R113") (pin "1") (pinfunction "1_1") (pintype "passive"))
    )
    (net (code "189") (name "Net-(Q4A-D)") (class "Default")
      (node (ref "C33") (pin "2") (pinfunction "2_2") (pintype "passive"))
      (node (ref "Q4") (pin "6") (pinfunction "D_6") (pintype "passive"))
      (node (ref "Q5") (pin "1") (pinfunction "G_1") (pintype "passive"))
      (node (ref "R42") (pin "2") (pinfunction "2_2") (pintype "passive"))
    )
    (net (code "190") (name "Net-(Q4A-S)") (class "Default")
      (node (ref "Q4") (pin "1") (pinfunction "S_1") (pintype "passive"))
      (node (ref "R40") (pin "2") (pinfunction "2_2") (pintype "passive"))
    )
    (net (code "191") (name "Net-(Q4B-D)") (class "Default")
      (node (ref "C34") (pin "2") (pinfunction "2_2") (pintype "passive"))
      (node (ref "Q4") (pin "3") (pinfunction "D_3") (pintype "passive"))
      (node (ref "Q5") (pin "3") (pinfunction "G_3") (pintype "passive"))
      (node (ref "R45") (pin "2") (pinfunction "2_2") (pintype "passive"))
    )
    (net (code "192") (name "Net-(Q4B-S)") (class "Default")
      (node (ref "Q4") (pin "4") (pinfunction "S_4") (pintype "passive"))
      (node (ref "R43") (pin "2") (pinfunction "2_2") (pintype "passive"))
    )
    (net (code "193") (name "Net-(Q5A-D)") (class "Default")
      (node (ref "F1") (pin "2") (pinfunction "2_2") (pintype "passive"))
      (node (ref "Q5") (pin "6") (pinfunction "D_6") (pintype "passive"))
      (node (ref "R35") (pin "1") (pinfunction "1_1") (pintype "passive"))
      (node (ref "R37") (pin "1") (pinfunction "1_1") (pintype "passive"))
      (node (ref "R97") (pin "1") (pinfunction "1_1") (pintype "passive"))
    )
    (net (code "194") (name "Net-(Q6A-G)") (class "Default")
      (node (ref "C42") (pin "2") (pinfunction "2_2") (pintype "passive"))
      (node (ref "Q6") (pin "1") (pinfunction "G_1") (pintype "passive"))
      (node (ref "Q7") (pin "6") (pinfunction "D_6") (pintype "passive"))
      (node (ref "R50") (pin "2") (pinfunction "2_2") (pintype "passive"))
    )
    (net (code "195") (name "Net-(Q6B-G)") (class "Default")
      (node (ref "C43") (pin "2") (pinfunction "2_2") (pintype "passive"))
      (node (ref "Q6") (pin "3") (pinfunction "G_3") (pintype "passive"))
      (node (ref "Q7") (pin "3") (pinfunction "D_3") (pintype "passive"))
      (node (ref "R55") (pin "2") (pinfunction "2_2") (pintype "passive"))
    )
    (net (code "196") (name "Net-(Q7A-S)") (class "Default")
      (node (ref "Q7") (pin "1") (pinfunction "S_1") (pintype "passive"))
      (node (ref "R51") (pin "2") (pinfunction "2_2") (pintype "passive"))
    )
    (net (code "197") (name "Net-(Q7B-S)") (class "Default")
      (node (ref "Q7") (pin "4") (pinfunction "S_4") (pintype "passive"))
      (node (ref "R53") (pin "1") (pinfunction "1_1") (pintype "passive"))
    )
    (net (code "198") (name "Net-(Q8A-G)") (class "Default")
      (node (ref "C44") (pin "2") (pinfunction "2_2") (pintype "passive"))
      (node (ref "Q8") (pin "1") (pinfunction "G_1") (pintype "passive"))
      (node (ref "Q9") (pin "6") (pinfunction "D_6") (pintype "passive"))
      (node (ref "R56") (pin "2") (pinfunction "2_2") (pintype "passive"))
    )
    (net (code "199") (name "Net-(Q8B-G)") (class "Default")
      (node (ref "C45") (pin "2") (pinfunction "2_2") (pintype "passive"))
      (node (ref "Q8") (pin "3") (pinfunction "G_3") (pintype "passive"))
      (node (ref "Q9") (pin "3") (pinfunction "D_3") (pintype "passive"))
      (node (ref "R61") (pin "2") (pinfunction "2_2") (pintype "passive"))
    )
    (net (code "200") (name "Net-(Q9A-S)") (class "Default")
      (node (ref "Q9") (pin "1") (pinfunction "S_1") (pintype "passive"))
      (node (ref "R57") (pin "2") (pinfunction "2_2") (pintype "passive"))
    )
    (net (code "201") (name "Net-(Q9B-S)") (class "Default")
      (node (ref "Q9") (pin "4") (pinfunction "S_4") (pintype "passive"))
      (node (ref "R59") (pin "1") (pinfunction "1_1") (pintype "passive"))
    )
    (net (code "202") (name "Net-(Q10A-D)") (class "Default")
      (node (ref "Q10") (pin "6") (pinfunction "D_6") (pintype "passive"))
      (node (ref "R79") (pin "2") (pinfunction "2_2") (pintype "passive"))
    )
    (net (code "203") (name "Net-(Q10A-S)") (class "Default")
      (node (ref "Q10") (pin "1") (pinfunction "S_1") (pintype "passive"))
      (node (ref "Q10") (pin "5") (pinfunction "G_5") (pintype "passive"))
      (node (ref "R80") (pin "1") (pinfunction "1_1") (pintype "passive"))
    )
    (net (code "204") (name "Net-(Q11A-D)") (class "Default")
      (node (ref "Q11") (pin "6") (pinfunction "D_6") (pintype "passive"))
      (node (ref "R63") (pin "2") (pinfunction "2_2") (pintype "passive"))
    )
    (net (code "205") (name "Net-(Q11A-S)") (class "Default")
      (node (ref "Q11") (pin "1") (pinfunction "S_1") (pintype "passive"))
      (node (ref "Q11") (pin "5") (pinfunction "G_5") (pintype "passive"))
      (node (ref "R64") (pin "1") (pinfunction "1_1") (pintype "passive"))
    )
    (net (code "206") (name "Net-(Q12A-D)") (class "Default")
      (node (ref "Q12") (pin "6") (pinfunction "D_6") (pintype "passive"))
      (node (ref "R85") (pin "2") (pinfunction "2_2") (pintype "passive"))
    )
    (net (code "207") (name "Net-(Q12A-S)") (class "Default")
      (node (ref "Q12") (pin "1") (pinfunction "S_1") (pintype "passive"))
      (node (ref "Q12") (pin "5") (pinfunction "G_5") (pintype "passive"))
      (node (ref "R86") (pin "1") (pinfunction "1_1") (pintype "passive"))
    )
    (net (code "208") (name "Net-(Q13A-D)") (class "Default")
      (node (ref "Q13") (pin "6") (pinfunction "D_6") (pintype "passive"))
      (node (ref "R69") (pin "2") (pinfunction "2_2") (pintype "passive"))
    )
    (net (code "209") (name "Net-(Q13A-S)") (class "Default")
      (node (ref "Q13") (pin "1") (pinfunction "S_1") (pintype "passive"))
      (node (ref "Q13") (pin "5") (pinfunction "G_5") (pintype "passive"))
      (node (ref "R70") (pin "1") (pinfunction "1_1") (pintype "passive"))
    )
    (net (code "210") (name "Net-(Q14A-D)") (class "Default")
      (node (ref "Q14") (pin "6") (pinfunction "D_6") (pintype "passive"))
      (node (ref "R117") (pin "2") (pinfunction "2_2") (pintype "passive"))
      (node (ref "R123") (pin "2") (pinfunction "2_2") (pintype "passive"))
    )
    (net (code "211") (name "Net-(Q14A-G)") (class "Default")
      (node (ref "Q14") (pin "2") (pinfunction "G_2") (pintype "passive"))
      (node (ref "R118") (pin "1") (pinfunction "1_1") (pintype "passive"))
      (node (ref "R119") (pin "1") (pinfunction "1_1") (pintype "passive"))
    )
    (net (code "212") (name "Net-(R23-Pad1)") (class "Default")
      (node (ref "R23") (pin "1") (pinfunction "1_1") (pintype "passive"))
      (node (ref "R49") (pin "2") (pinfunction "2_2") (pintype "passive"))
    )
    (net (code "213") (name "Net-(R35-Pad2)") (class "Default")
      (node (ref "R35") (pin "2") (pinfunction "2_2") (pintype "passive"))
      (node (ref "R36") (pin "1") (pinfunction "1_1") (pintype "passive"))
      (node (ref "R37") (pin "2") (pinfunction "2_2") (pintype "passive"))
      (node (ref "R38") (pin "1") (pinfunction "1_1") (pintype "passive"))
    )
    (net (code "214") (name "Net-(R94-Pad2)") (class "Default")
      (node (ref "R94") (pin "2") (pinfunction "2_2") (pintype "passive"))
      (node (ref "R95") (pin "1") (pinfunction "1_1") (pintype "passive"))
    )
    (net (code "215") (name "Net-(R97-Pad2)") (class "Default")
      (node (ref "R97") (pin "2") (pinfunction "2_2") (pintype "passive"))
      (node (ref "R98") (pin "1") (pinfunction "1_1") (pintype "passive"))
    )
    (net (code "216") (name "VBAT") (class "Default")
      (node (ref "C22") (pin "1") (pinfunction "1_1") (pintype "passive"))
      (node (ref "C23") (pin "1") (pinfunction "1_1") (pintype "passive"))
      (node (ref "C42") (pin "1") (pinfunction "1_1") (pintype "passive"))
      (node (ref "C43") (pin "1") (pinfunction "1_1") (pintype "passive"))
      (node (ref "C44") (pin "1") (pinfunction "1_1") (pintype "passive"))
      (node (ref "C45") (pin "1") (pinfunction "1_1") (pintype "passive"))
      (node (ref "C83") (pin "1") (pinfunction "1_1") (pintype "passive"))
      (node (ref "C84") (pin "1") (pinfunction "1_1") (pintype "passive"))
      (node (ref "IC10") (pin "4") (pinfunction "VIN-_4") (pintype "input"))
      (node (ref "IC8") (pin "4") (pinfunction "VIN_4") (pintype "bidirectional"))
      (node (ref "J5") (pin "5") (pinfunction "5_5") (pintype "bidirectional"))
      (node (ref "J6") (pin "5") (pinfunction "5_5") (pintype "bidirectional"))
      (node (ref "J7") (pin "1") (pinfunction "1_1") (pintype "passive"))
      (node (ref "J8") (pin "1") (pinfunction "1_1") (pintype "passive"))
      (node (ref "JP1") (pin "3") (pinfunction "3_3") (pintype "bidirectional"))
      (node (ref "Q6") (pin "2") (pinfunction "S_2") (pintype "passive"))
      (node (ref "Q6") (pin "5") (pinfunction "S_5") (pintype "passive"))
      (node (ref "Q8") (pin "2") (pinfunction "S_2") (pintype "passive"))
      (node (ref "Q8") (pin "5") (pinfunction "S_5") (pintype "passive"))
      (node (ref "R124") (pin "1") (pinfunction "1_1") (pintype "passive"))
      (node (ref "R125") (pin "1") (pinfunction "1_1") (pintype "passive"))
      (node (ref "R22") (pin "1") (pinfunction "1_1") (pintype "passive"))
      (node (ref "R33") (pin "2") (pinfunction "2_2") (pintype "passive"))
      (node (ref "R39") (pin "1") (pinfunction "1_1") (pintype "passive"))
      (node (ref "R50") (pin "1") (pinfunction "1_1") (pintype "passive"))
      (node (ref "R55") (pin "1") (pinfunction "1_1") (pintype "passive"))
      (node (ref "R56") (pin "1") (pinfunction "1_1") (pintype "passive"))
      (node (ref "R61") (pin "1") (pinfunction "1_1") (pintype "passive"))
    )
    (net (code "217") (name "unconnected-(IC2-D8-Pad30)") (class "Default")
      (node (ref "IC2") (pin "30") (pinfunction "D8_30") (pintype "tri_state"))
    )
    (net (code "218") (name "unconnected-(IC2-D9-Pad32)") (class "Default")
      (node (ref "IC2") (pin "32") (pinfunction "D9_32") (pintype "tri_state"))
    )
    (net (code "219") (name "unconnected-(IC2-D10-Pad34)") (class "Default")
      (node (ref "IC2") (pin "34") (pinfunction "D10_34") (pintype "tri_state"))
    )
    (net (code "220") (name "unconnected-(IC2-D11-Pad36)") (class "Default")
      (node (ref "IC2") (pin "36") (pinfunction "D11_36") (pintype "tri_state"))
    )
    (net (code "221") (name "unconnected-(IC2-D12-Pad39)") (class "Default")
      (node (ref "IC2") (pin "39") (pinfunction "D12_39") (pintype "tri_state"))
    )
    (net (code "222") (name "unconnected-(IC2-D13-Pad41)") (class "Default")
      (node (ref "IC2") (pin "41") (pinfunction "D13_41") (pintype "tri_state"))
    )
    (net (code "223") (name "unconnected-(IC2-D14-Pad43)") (class "Default")
      (node (ref "IC2") (pin "43") (pinfunction "D14_43") (pintype "tri_state"))
    )
    (net (code "224") (name "unconnected-(IC2-NC-Pad10)") (class "Default")
      (node (ref "IC2") (pin "10") (pinfunction "NC_10") (pintype "no_connect"))
    )
    (net (code "225") (name "unconnected-(IC2-NC1-Pad13)") (class "Default")
      (node (ref "IC2") (pin "13") (pinfunction "NC1_13") (pintype "no_connect"))
    )
    (net (code "226") (name "unconnected-(IC8-PG-Pad9)") (class "Default")
      (node (ref "IC8") (pin "9") (pinfunction "PG_9") (pintype "bidirectional"))
    )
    (net (code "227") (name "unconnected-(J1-Pad1)") (class "Default")
      (node (ref "J1") (pin "1") (pinfunction "1_1") (pintype "passive"))
    )
    (net (code "228") (name "unconnected-(J1-Pad23)") (class "Default")
      (node (ref "J1") (pin "23") (pinfunction "23_23") (pintype "passive"))
    )
    (net (code "229") (name "unconnected-(J1-Pad24)") (class "Default")
      (node (ref "J1") (pin "24") (pinfunction "24_24") (pintype "passive"))
    )
    (net (code "230") (name "unconnected-(J2-Pad1)") (class "Default")
      (node (ref "J2") (pin "1") (pinfunction "1_1") (pintype "passive"))
    )
    (net (code "231") (name "unconnected-(J2-Pad23)") (class "Default")
      (node (ref "J2") (pin "23") (pinfunction "23_23") (pintype "passive"))
    )
    (net (code "232") (name "unconnected-(J2-Pad24)") (class "Default")
      (node (ref "J2") (pin "24") (pinfunction "24_24") (pintype "passive"))
    )
    (net (code "233") (name "unconnected-(J5-Pad6)") (class "Default")
      (node (ref "J5") (pin "6") (pinfunction "6_6") (pintype "bidirectional"))
    )
    (net (code "234") (name "unconnected-(J6-Pad6)") (class "Default")
      (node (ref "J6") (pin "6") (pinfunction "6_6") (pintype "bidirectional"))
    )
    (net (code "235") (name "unconnected-(J14-Pad8)") (class "Default")
      (node (ref "J14") (pin "8") (pinfunction "8_8") (pintype "passive"))
    )
    (net (code "236") (name "unconnected-(Q3B-D-Pad3)") (class "Default")
      (node (ref "Q3") (pin "3") (pinfunction "D_3") (pintype "passive"))
    )
    (net (code "237") (name "unconnected-(Q3B-G-Pad5)") (class "Default")
      (node (ref "Q3") (pin "5") (pinfunction "G_5") (pintype "passive"))
    )
    (net (code "238") (name "unconnected-(Q3B-S-Pad4)") (class "Default")
      (node (ref "Q3") (pin "4") (pinfunction "S_4") (pintype "passive"))
    )
    (net (code "239") (name "unconnected-(Q14B-D-Pad3)") (class "Default")
      (node (ref "Q14") (pin "3") (pinfunction "D_3") (pintype "passive"))
    )
    (net (code "240") (name "unconnected-(Q14B-G-Pad5)") (class "Default")
      (node (ref "Q14") (pin "5") (pinfunction "G_5") (pintype "passive"))
    )
    (net (code "241") (name "unconnected-(Q14B-S-Pad4)") (class "Default")
      (node (ref "Q14") (pin "4") (pinfunction "S_4") (pintype "passive"))
    )
  )
)
